# PX4FMUv2_4_3.net
KiCad netlist of a schematic drawn in EAGLE
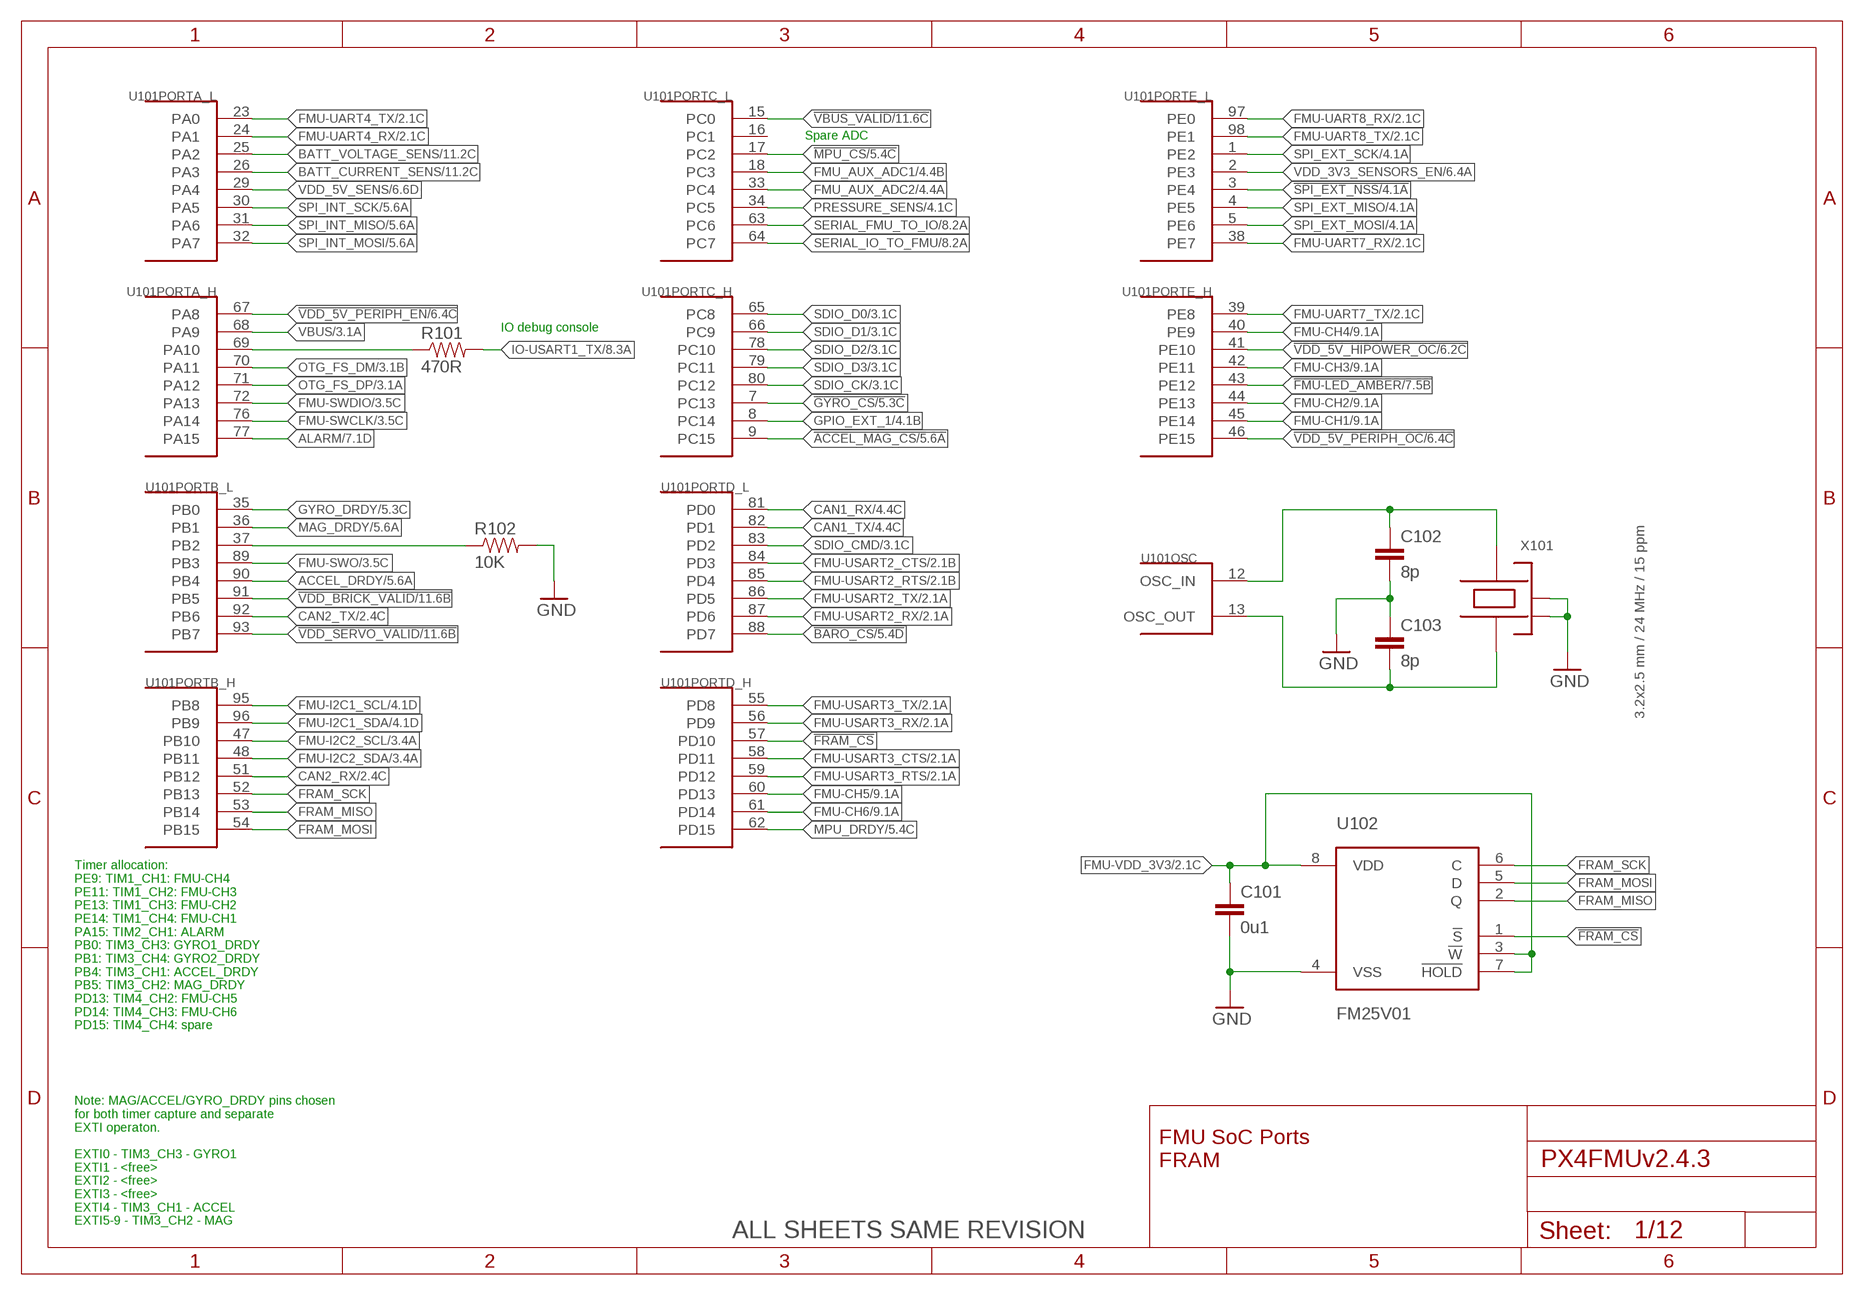
[diagram p0: schematic, sheet 1]
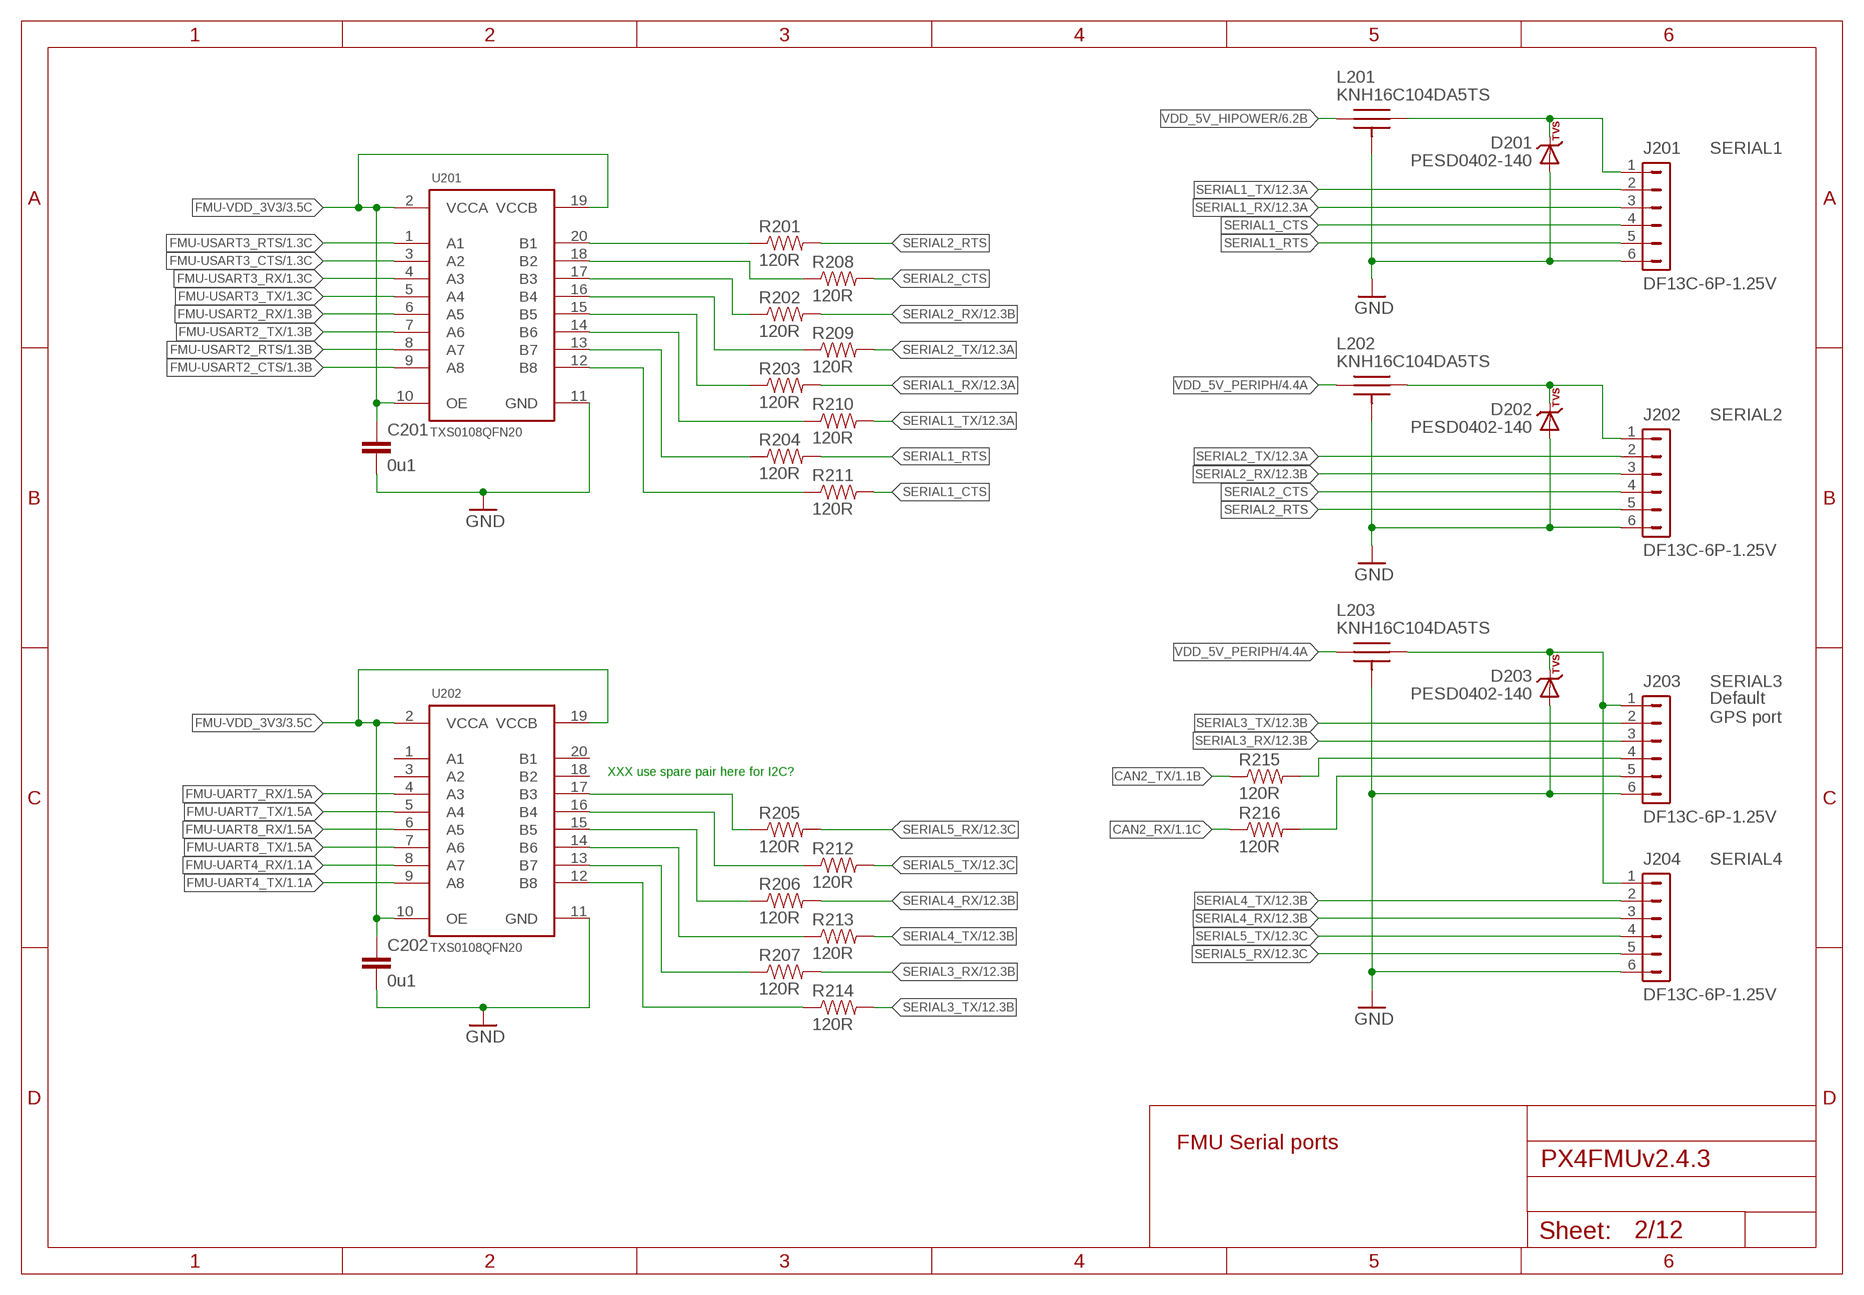
[diagram p1: schematic, sheet 2]
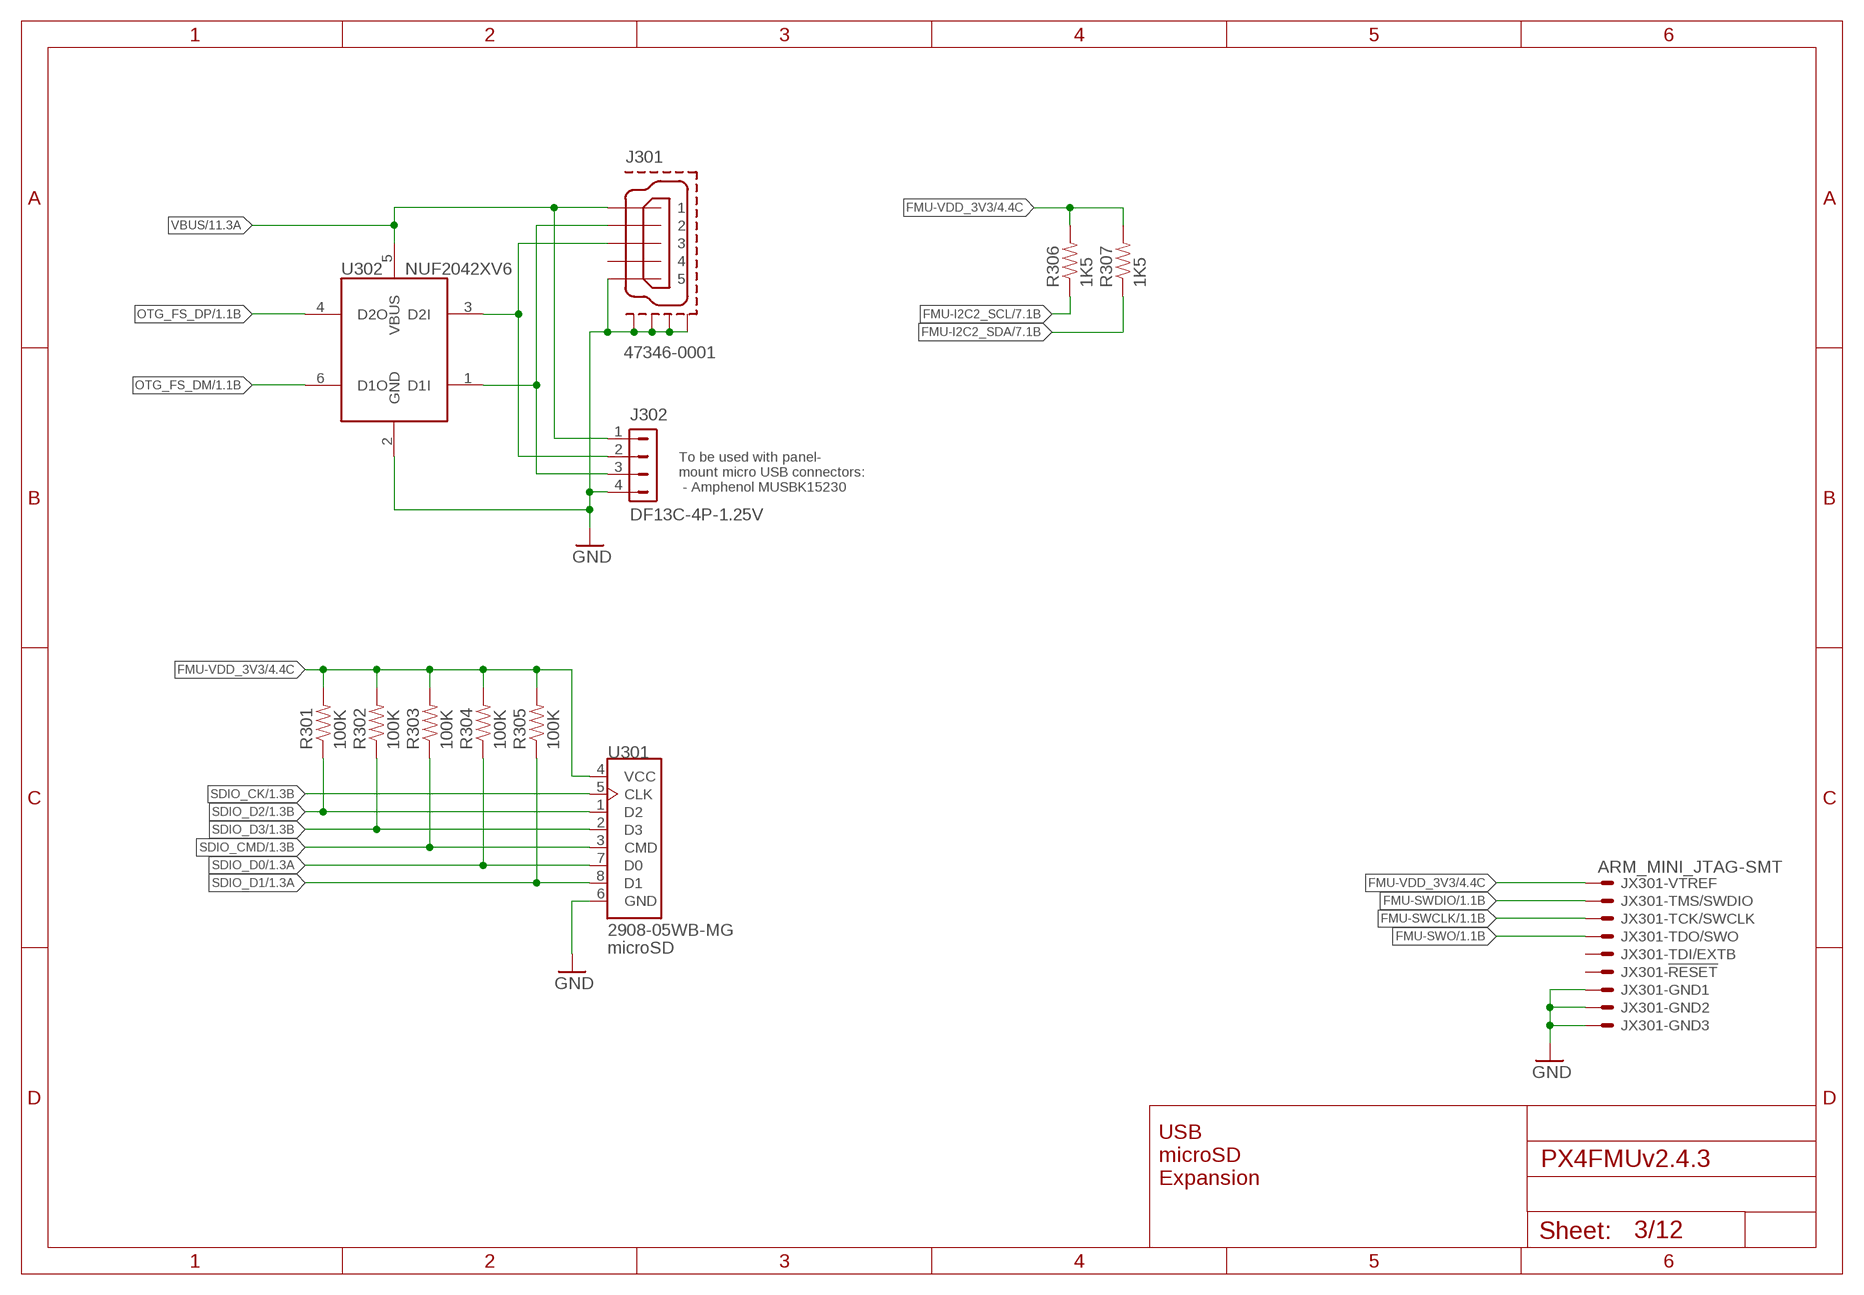
[diagram p2: schematic, sheet 3]
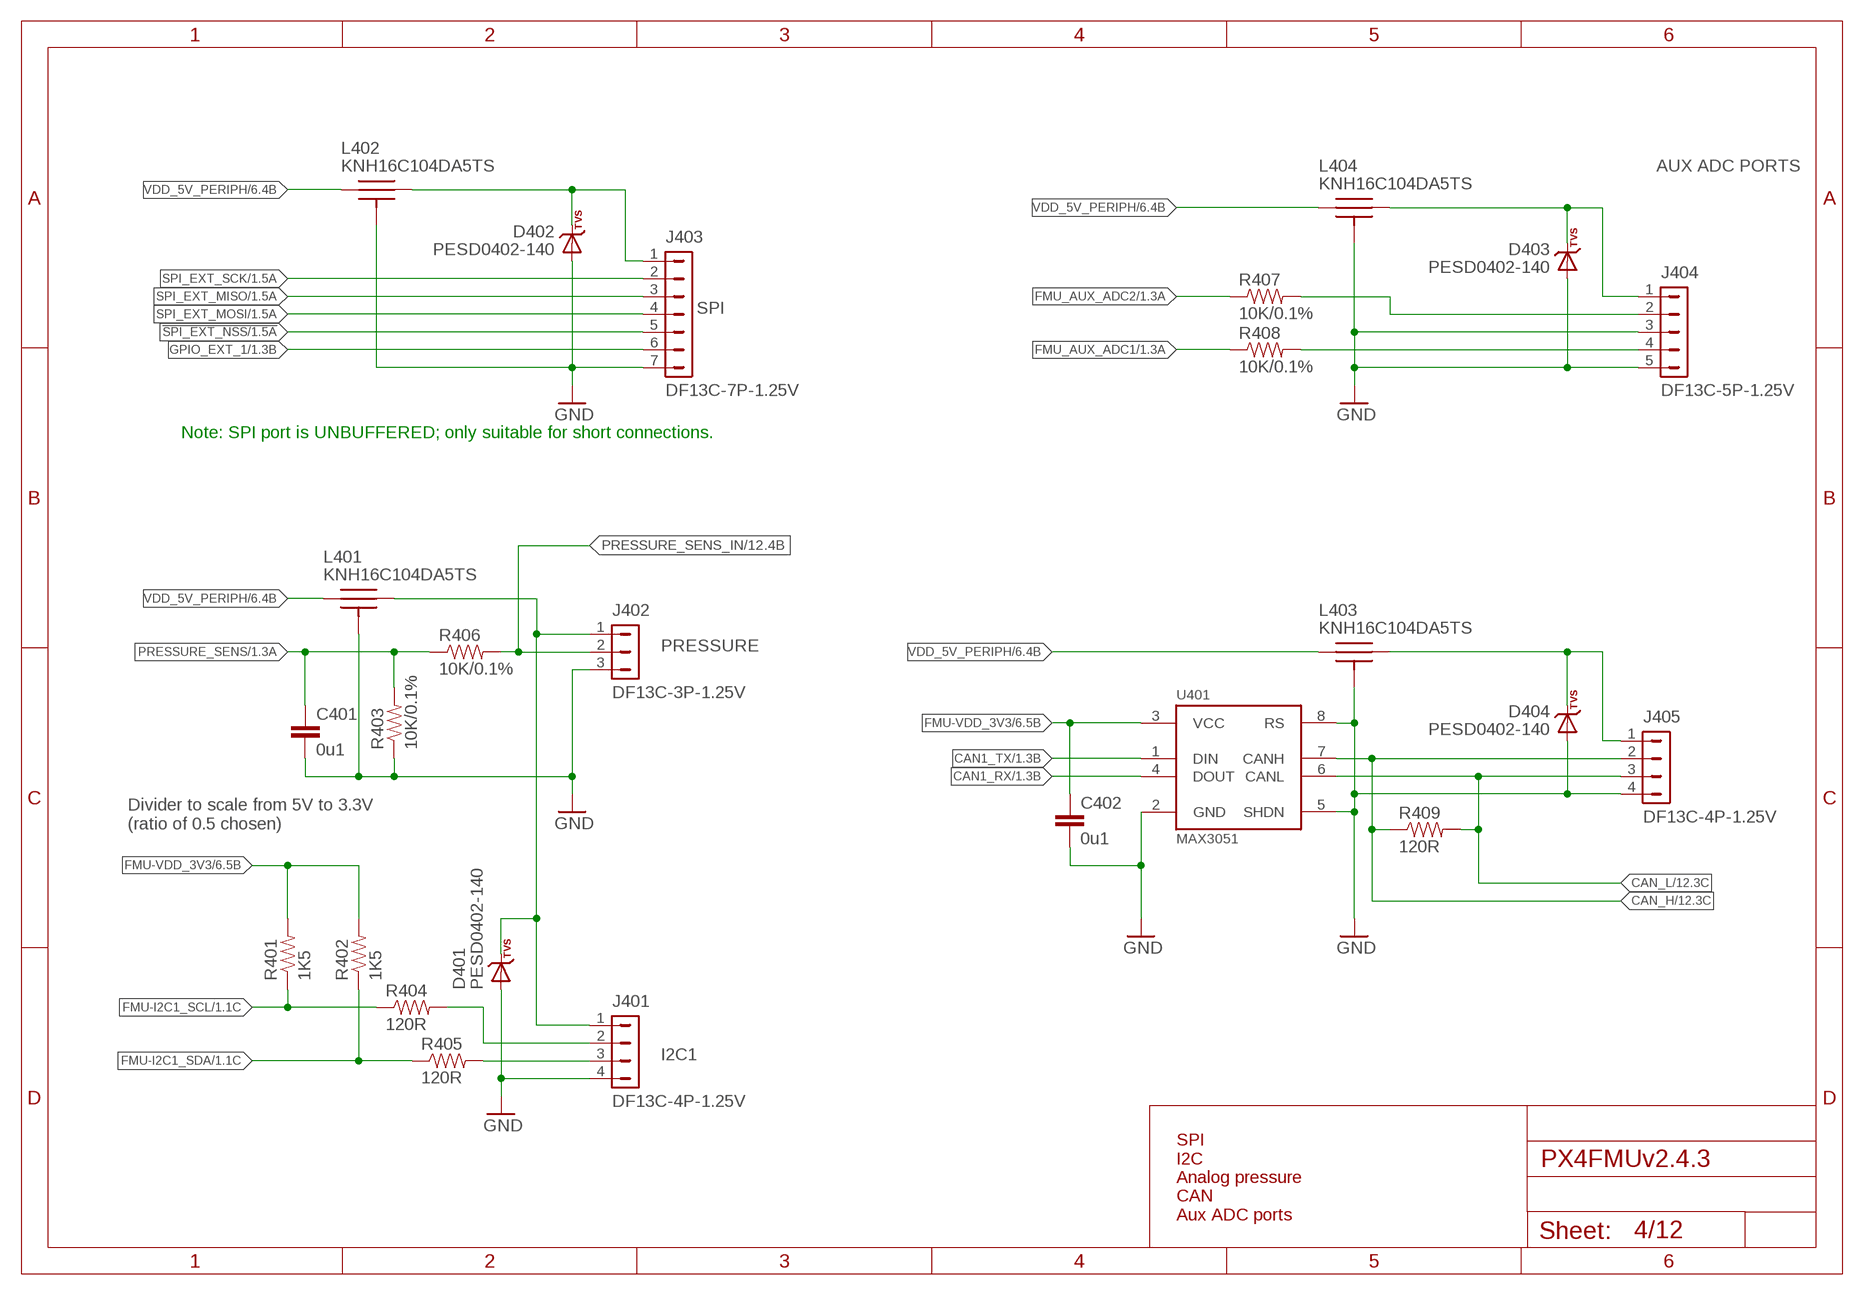
[diagram p3: schematic, sheet 4]
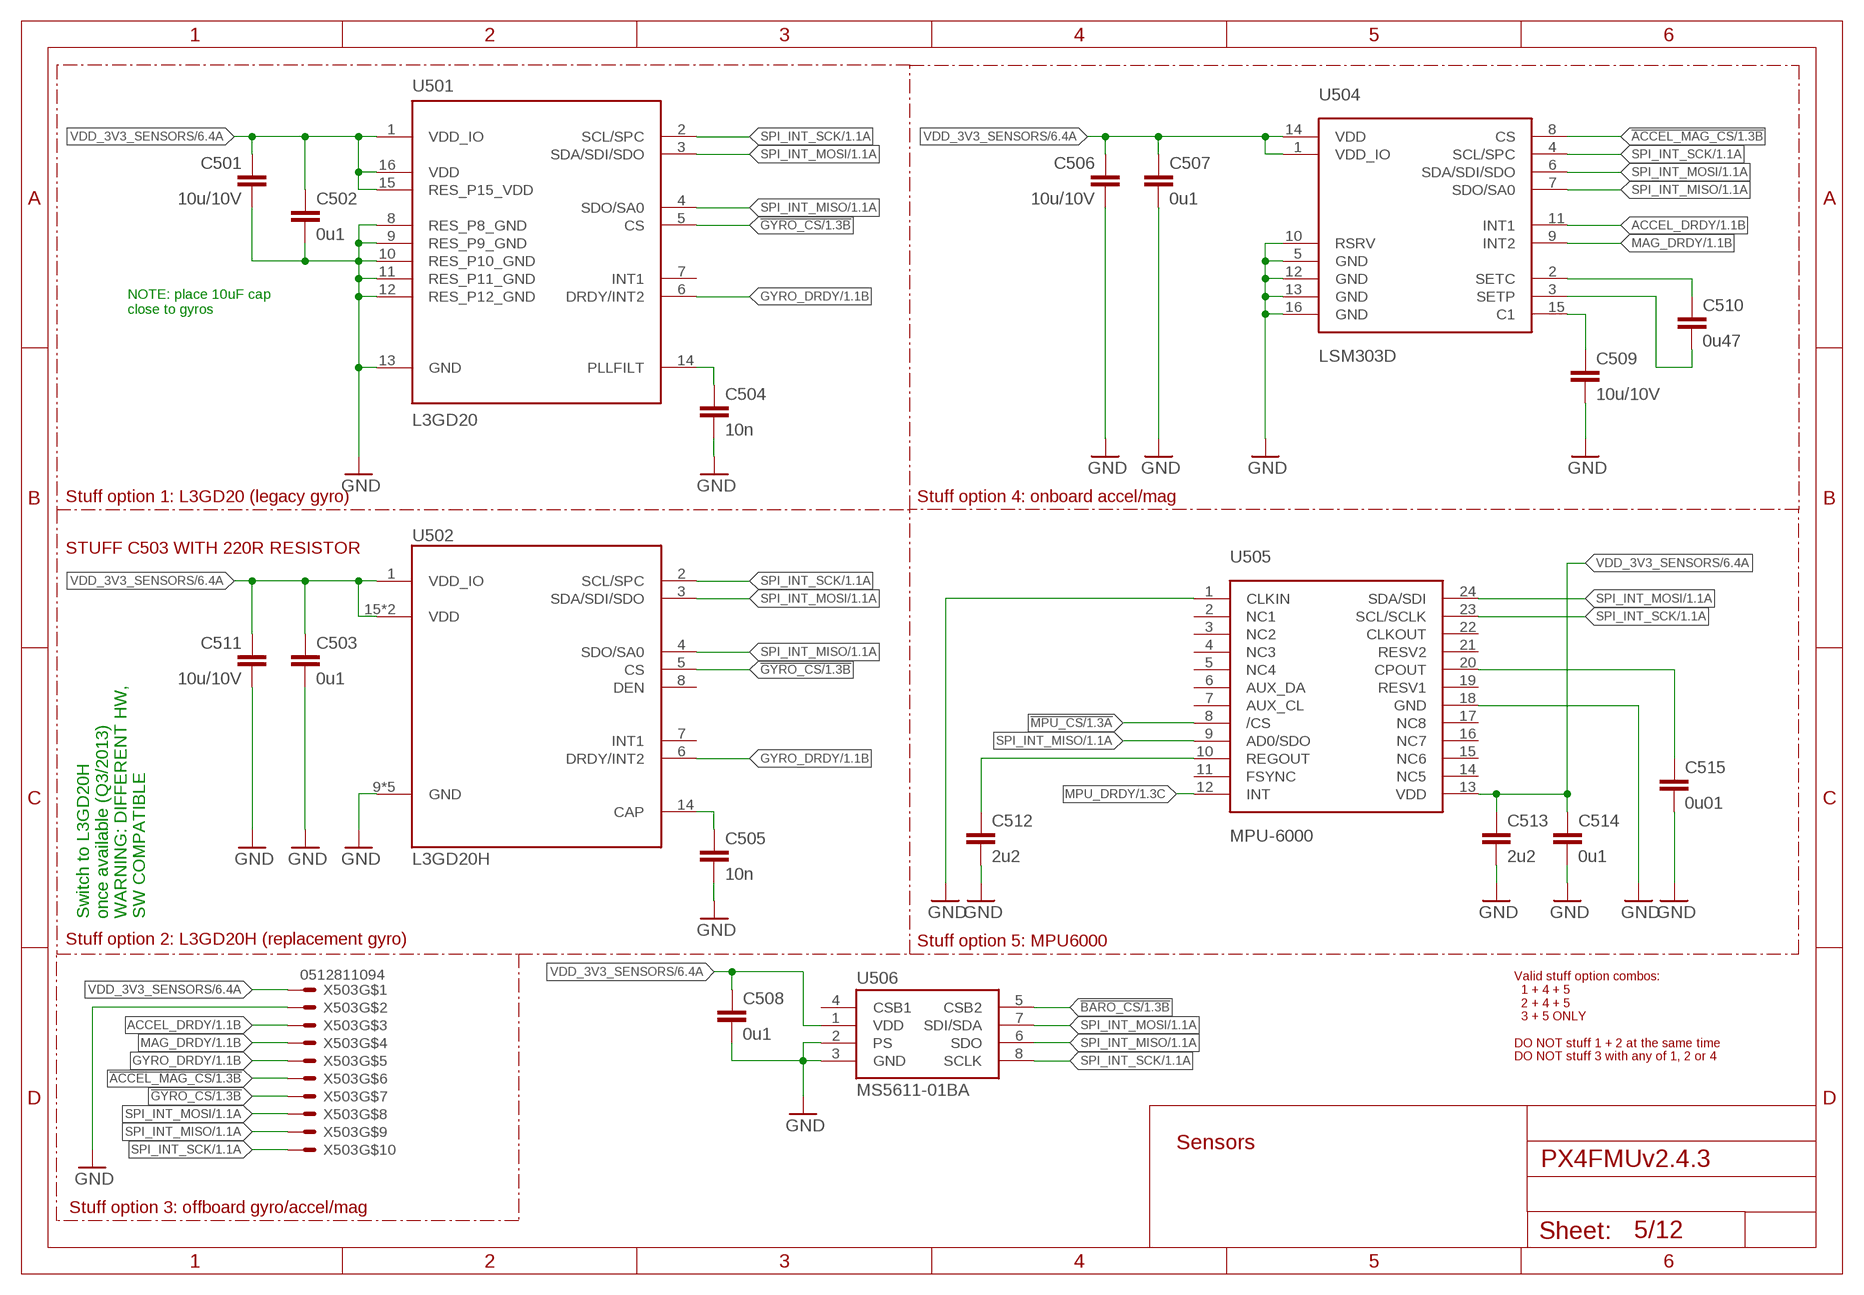
[diagram p4: schematic, sheet 5]
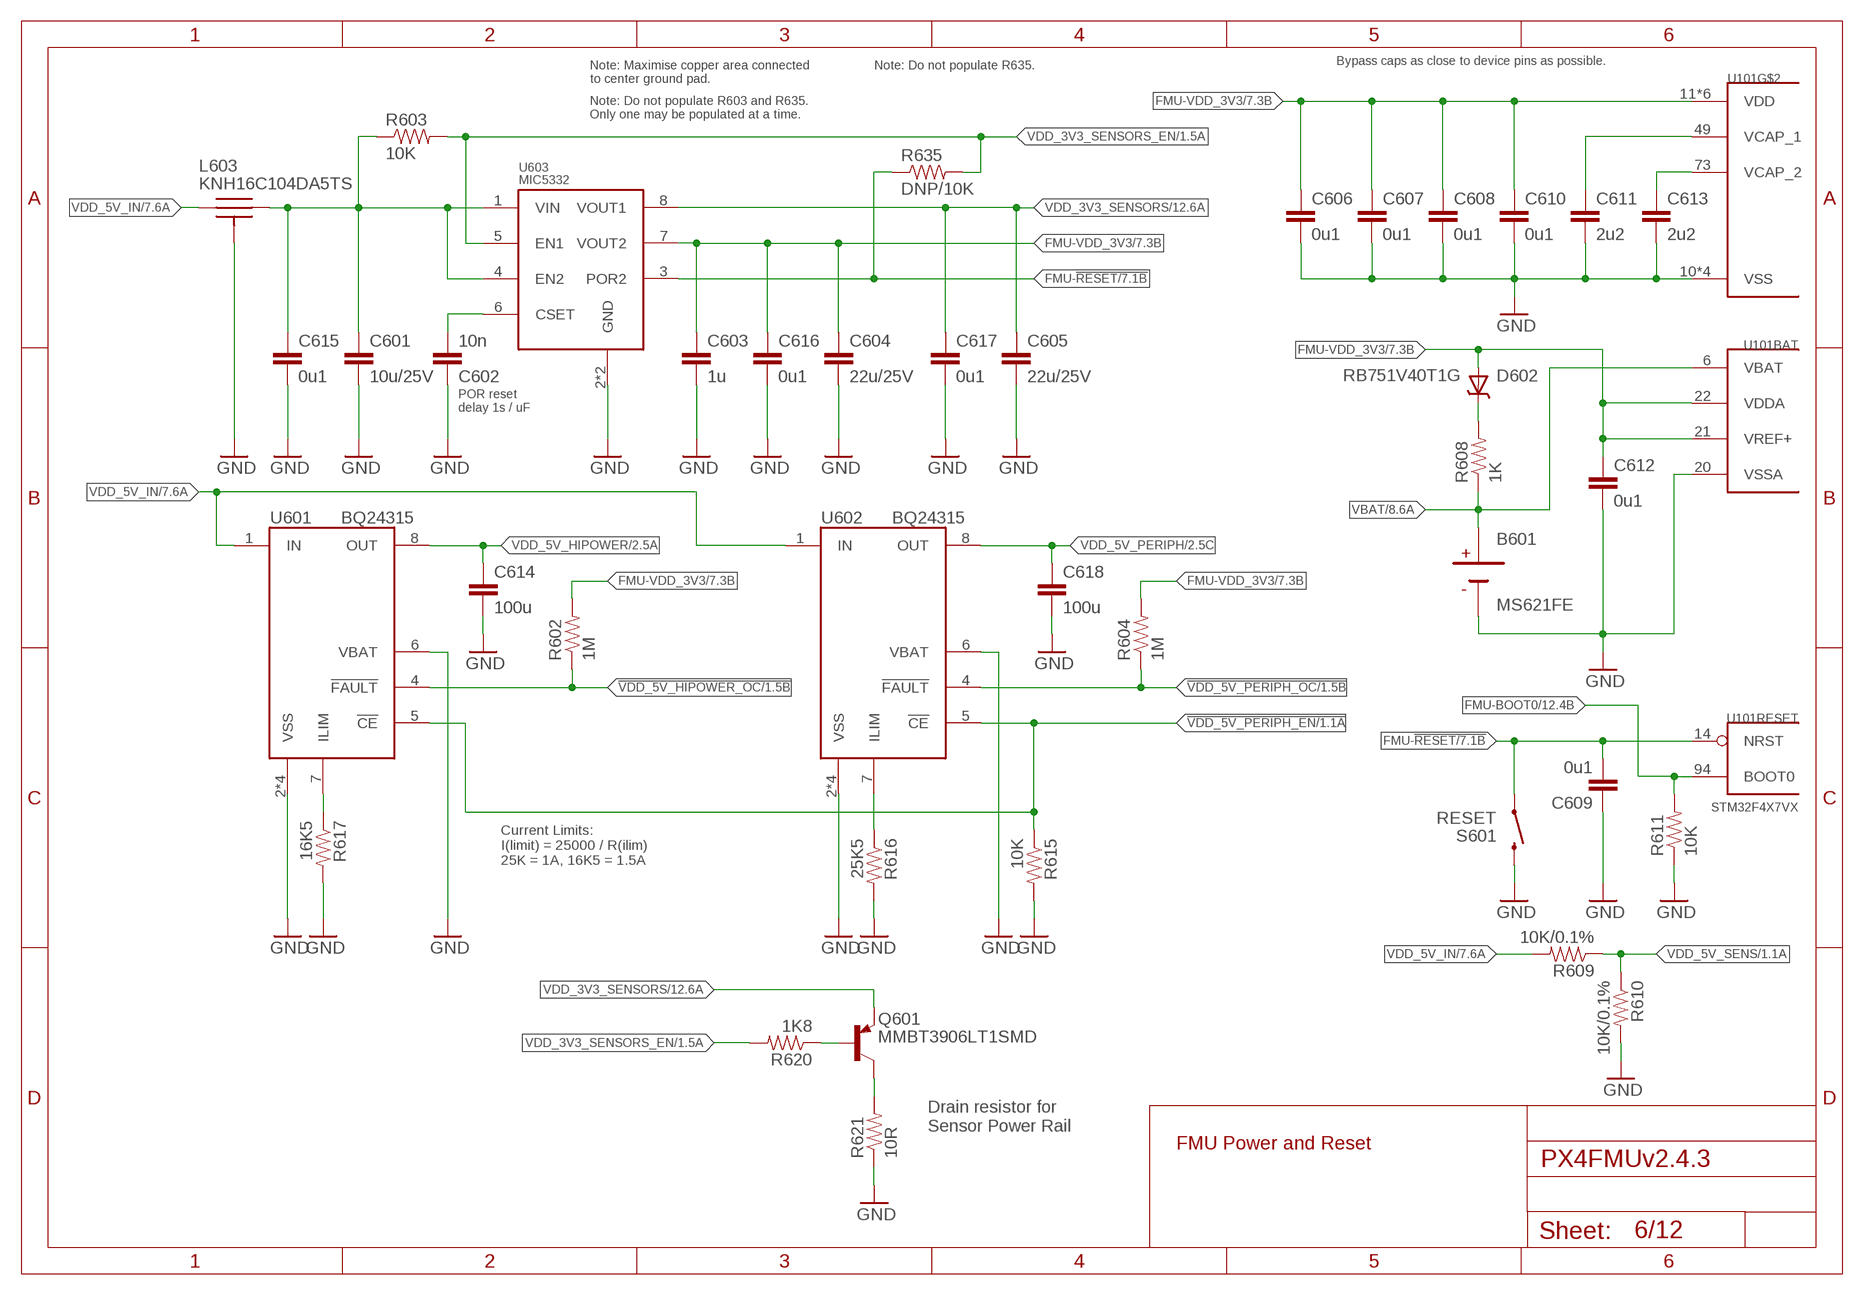
[diagram p5: schematic, sheet 6]
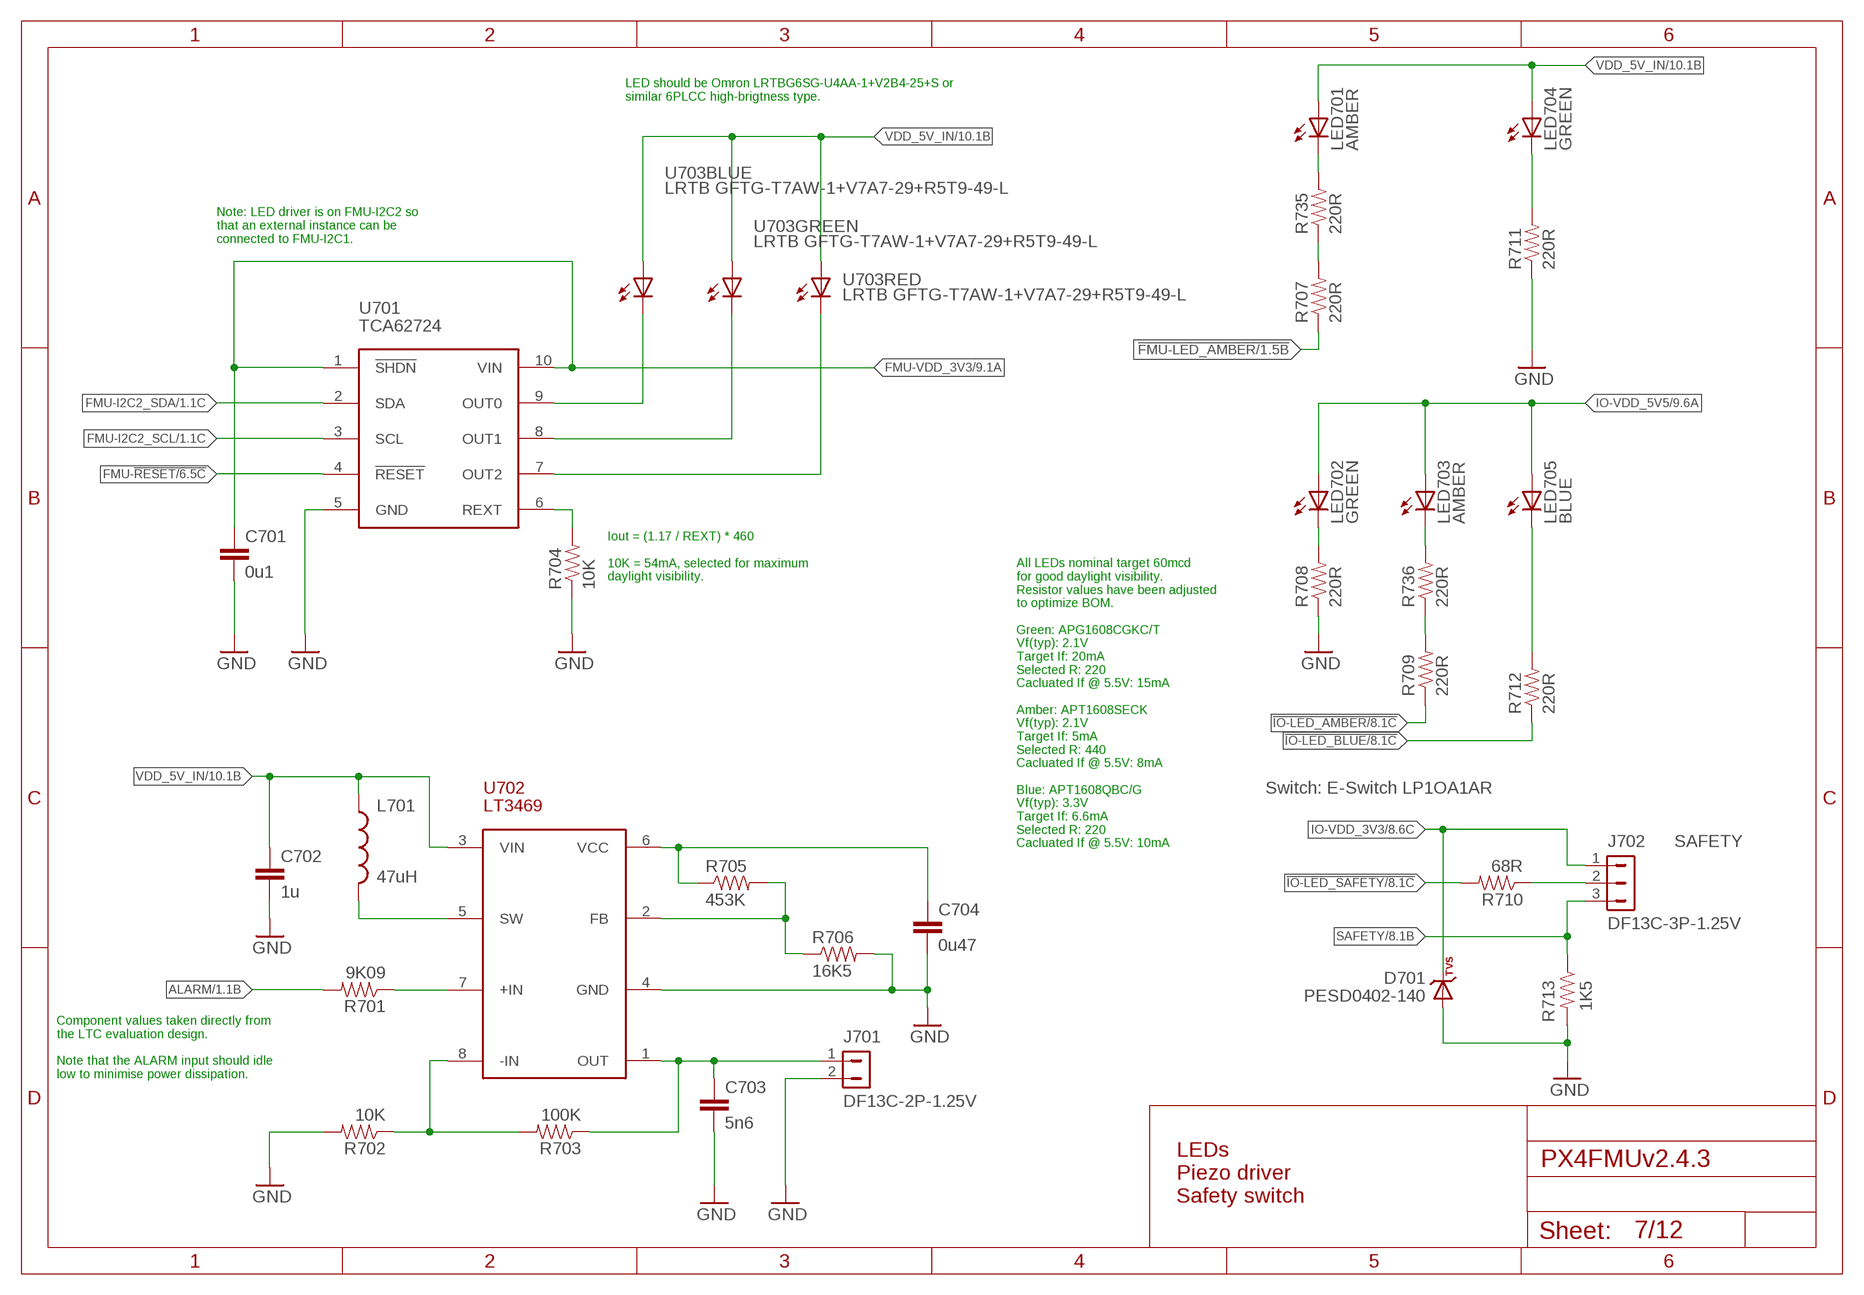
[diagram p6: schematic, sheet 7]
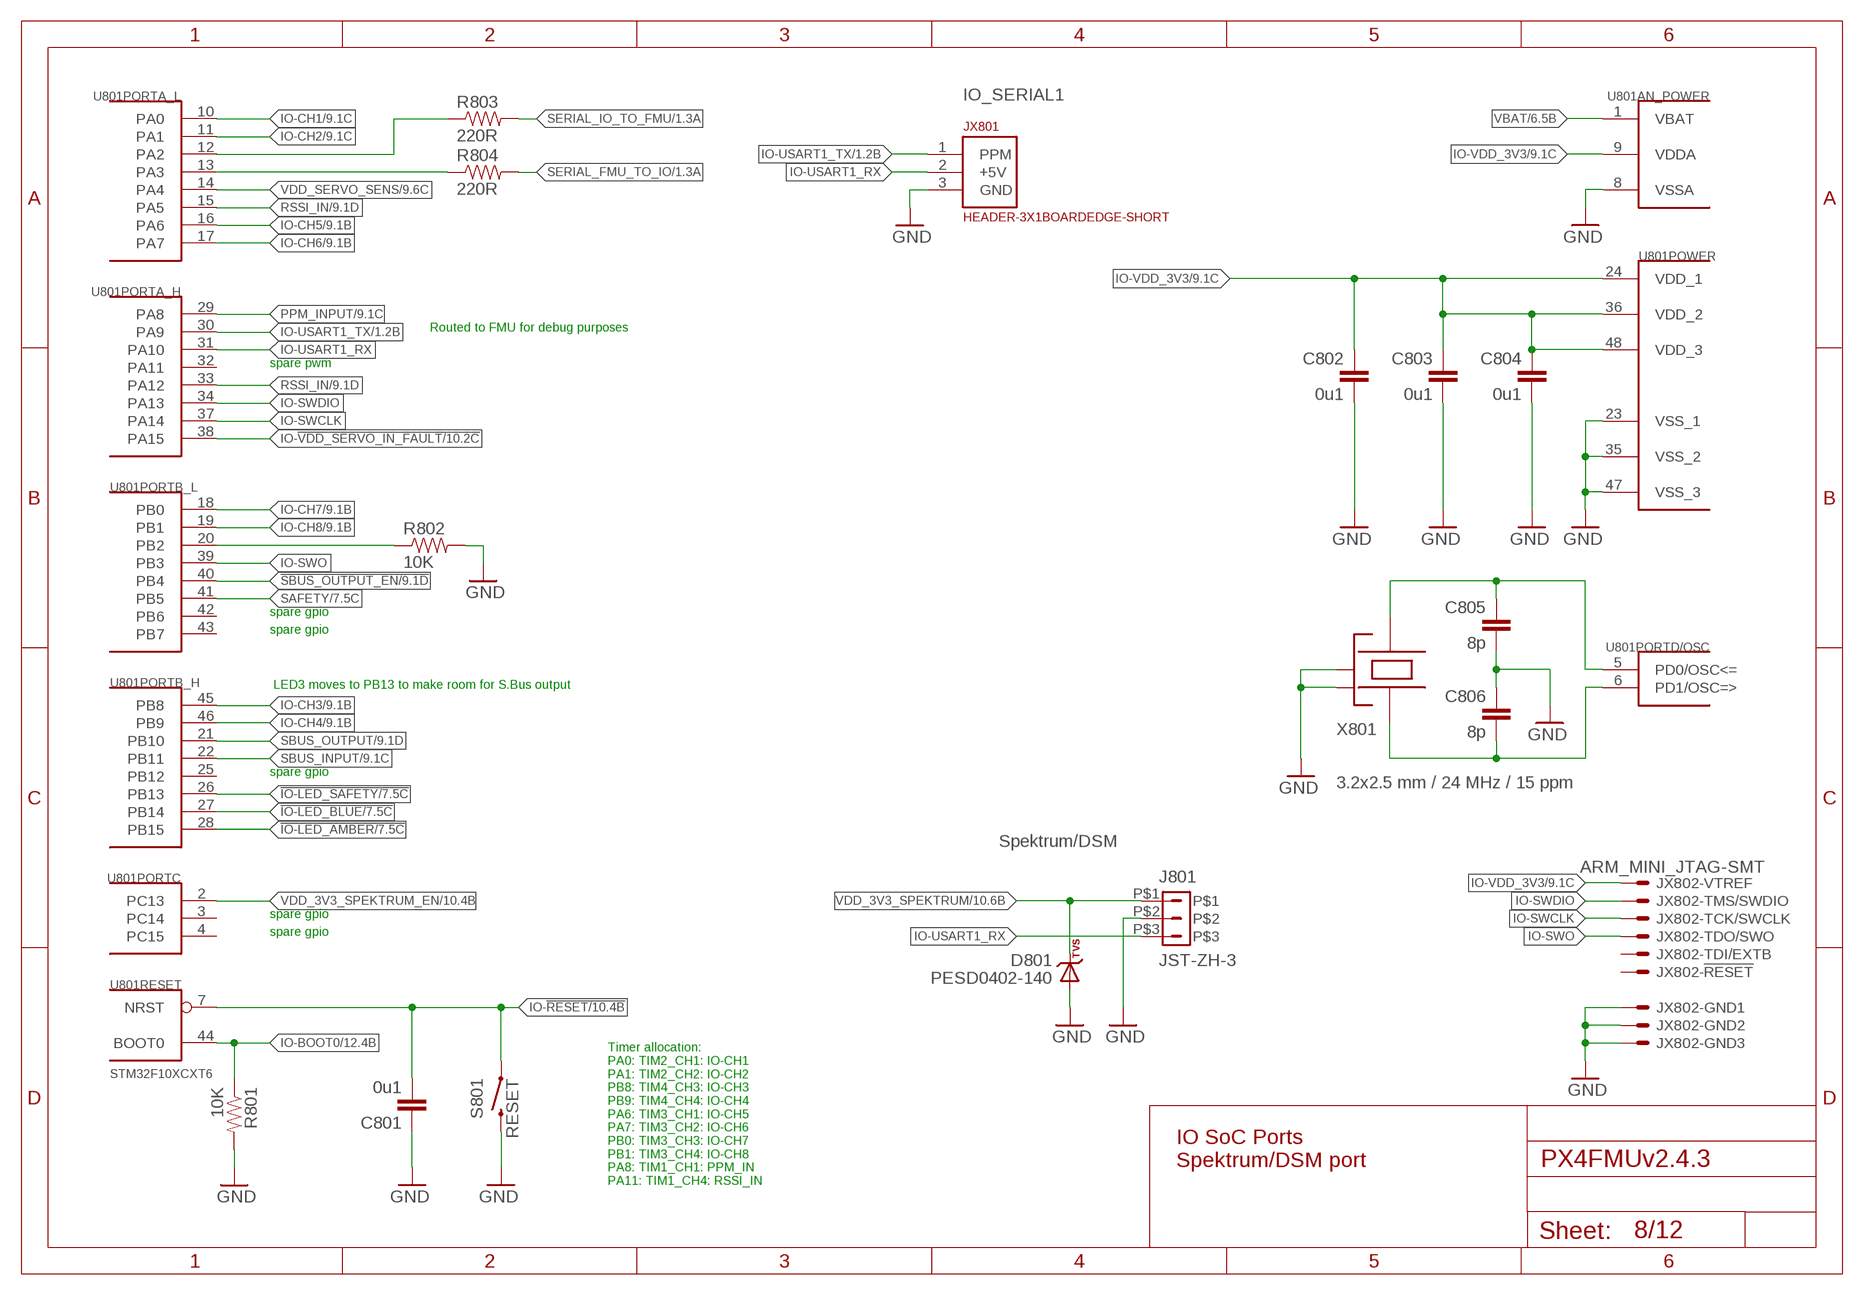
[diagram p7: schematic, sheet 8]
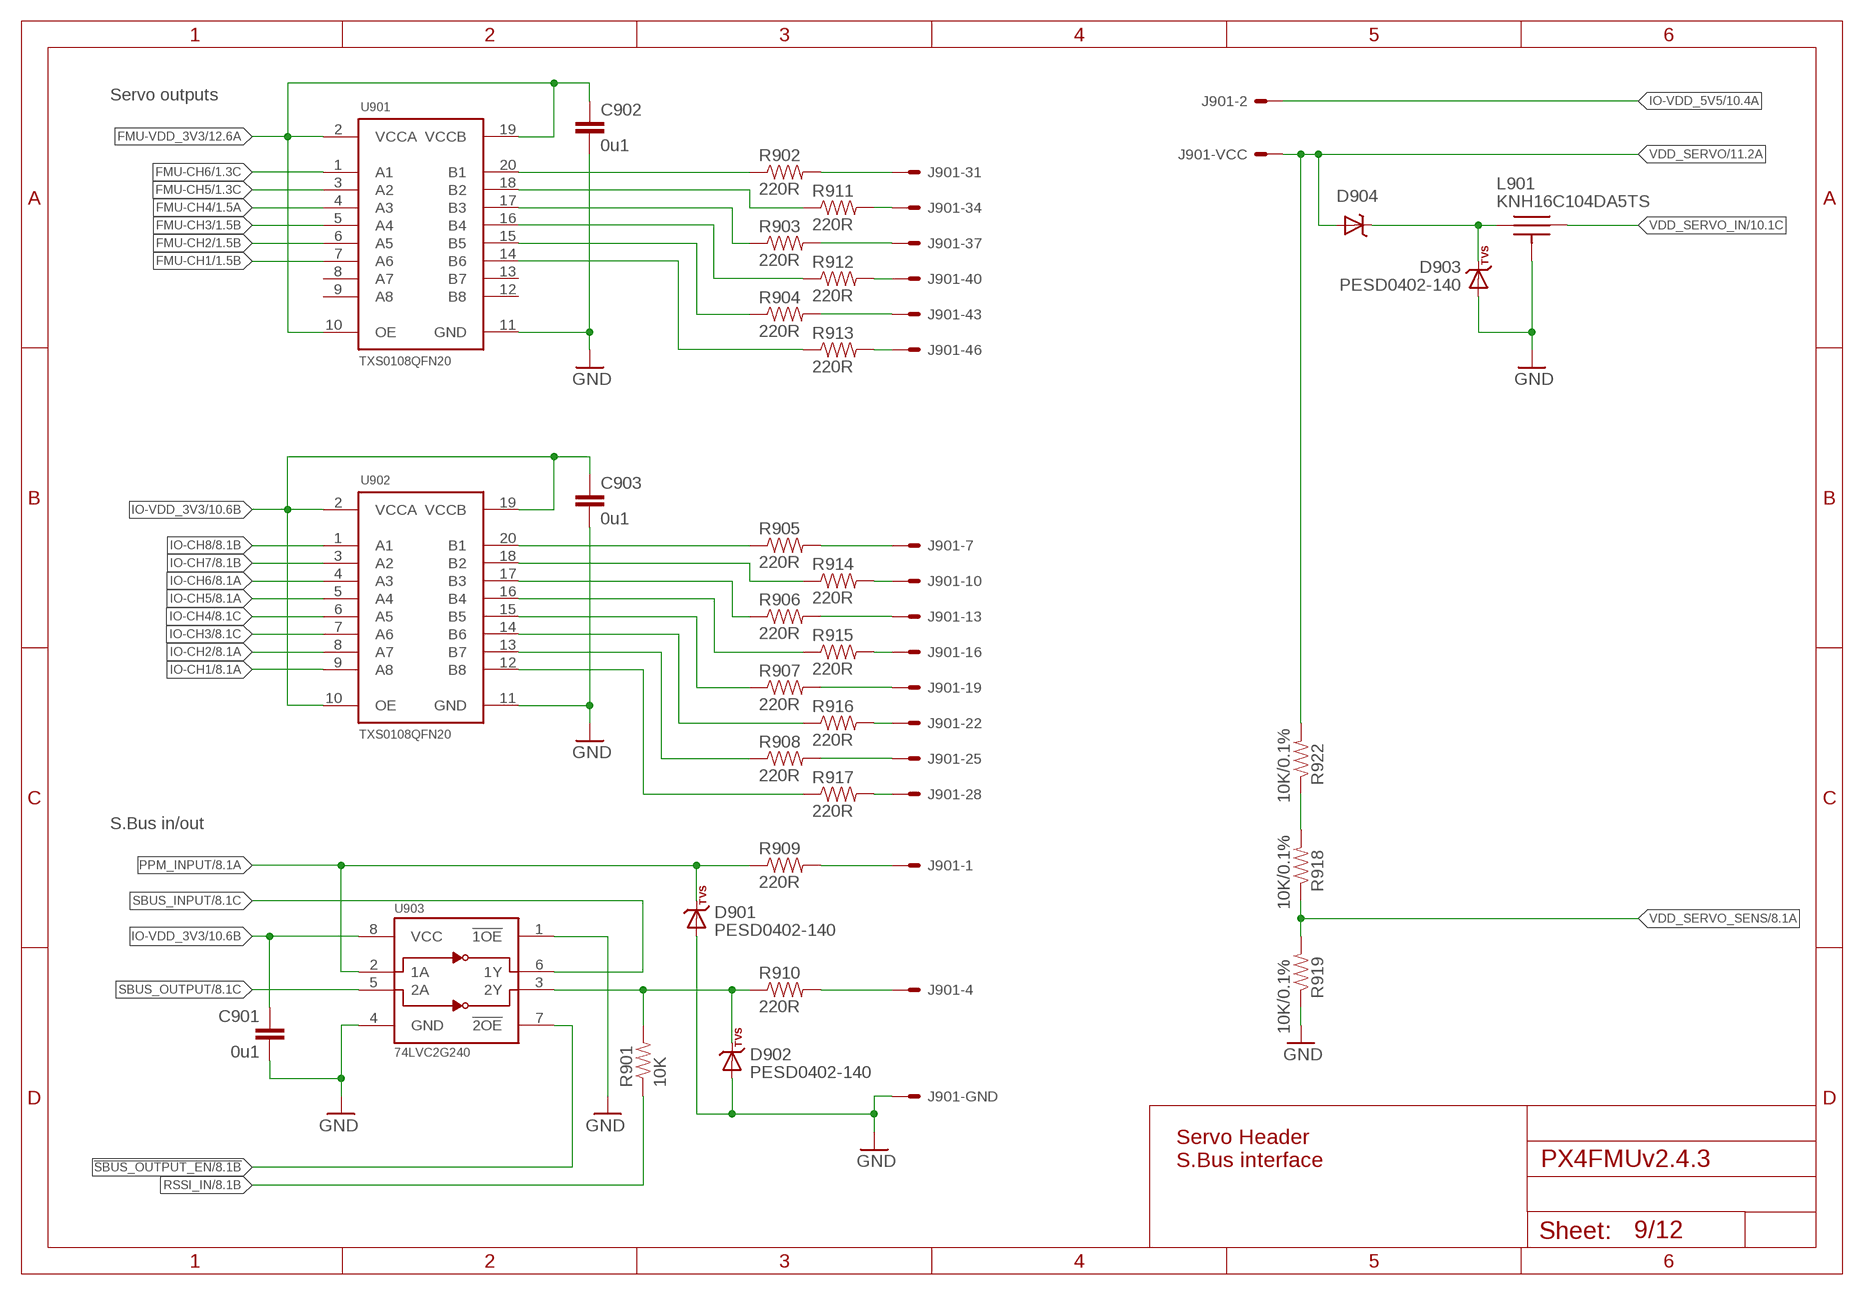
[diagram p8: schematic, sheet 9]
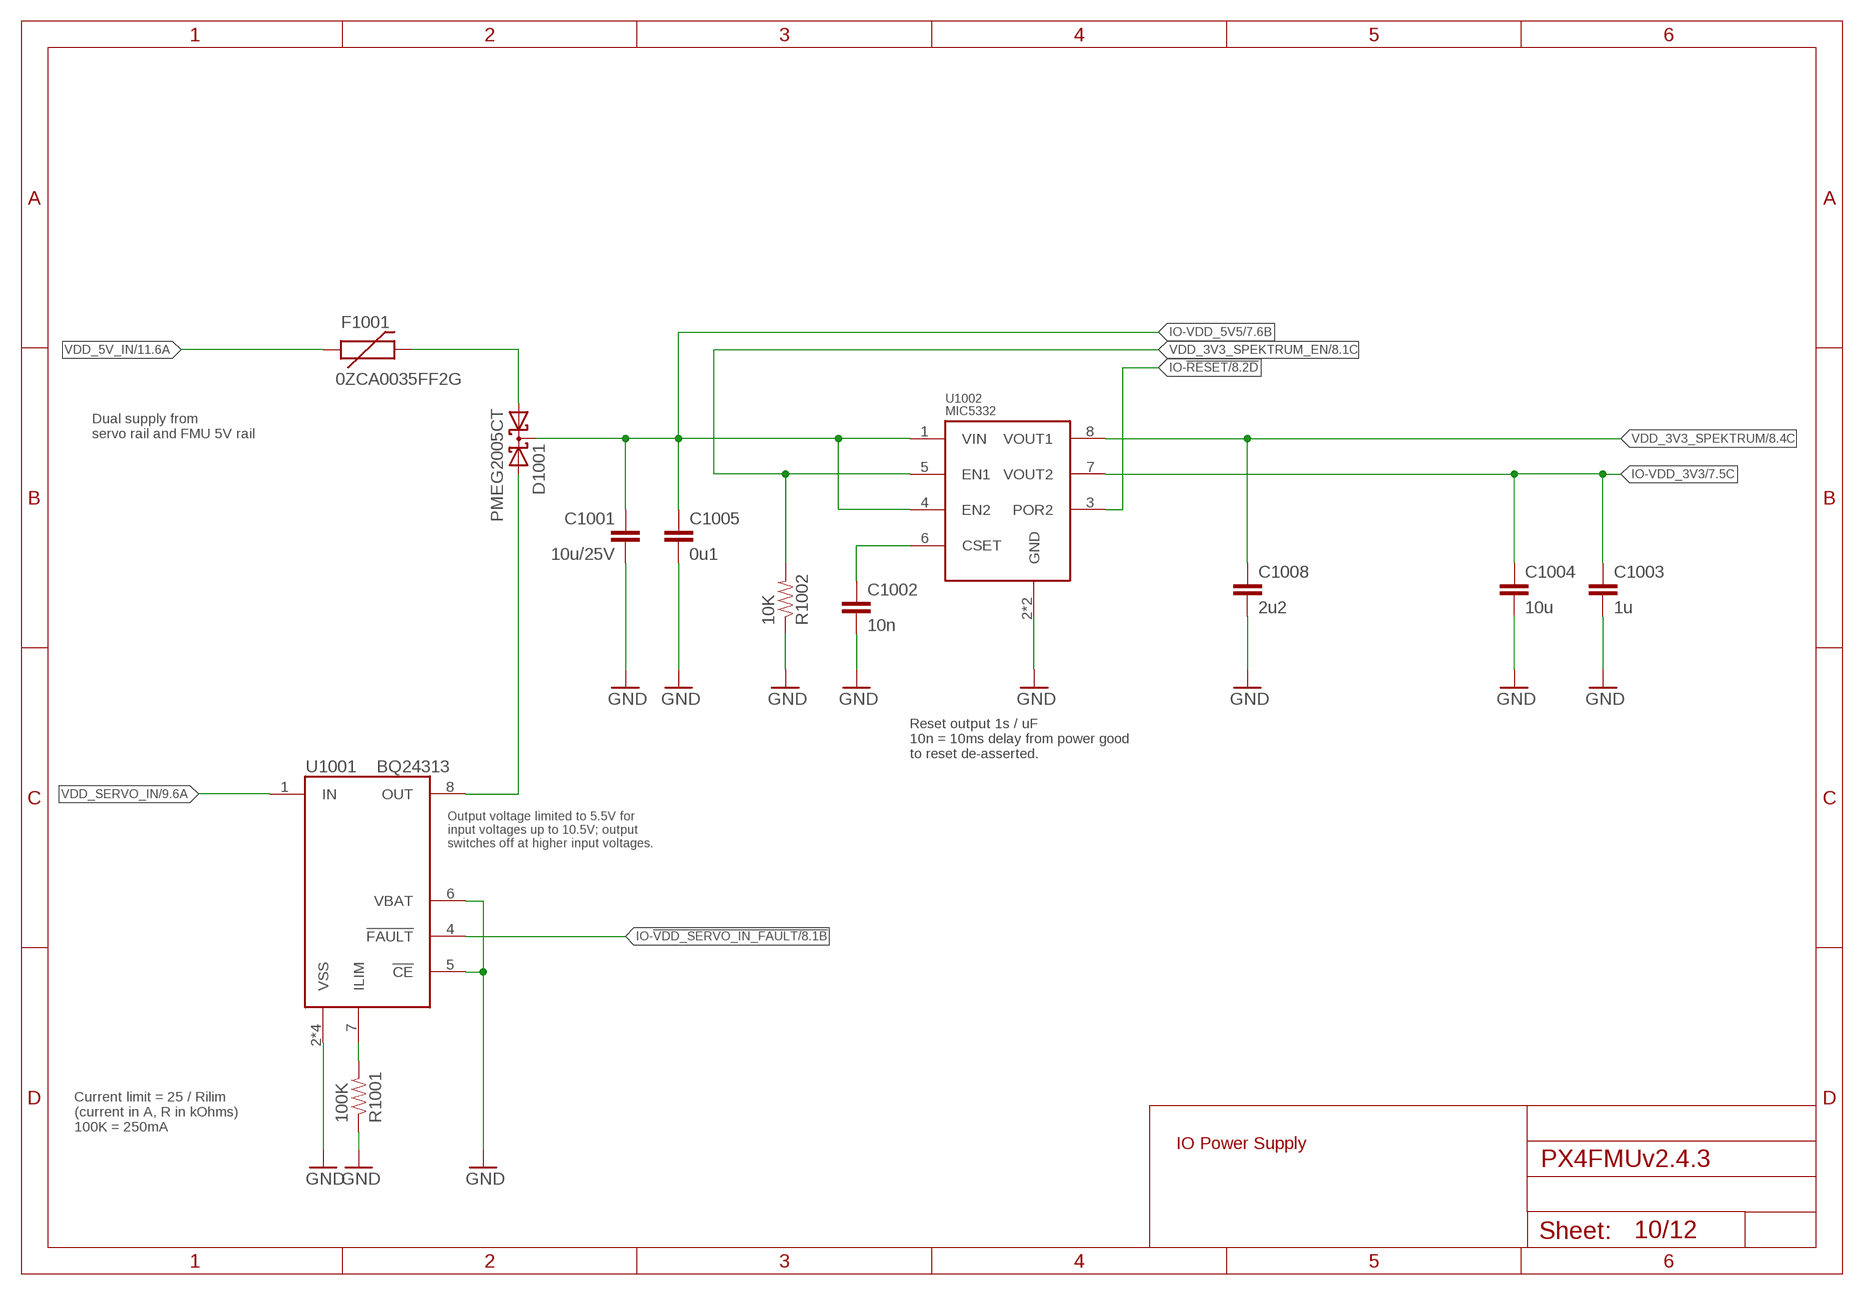
[diagram p9: schematic, sheet 10]
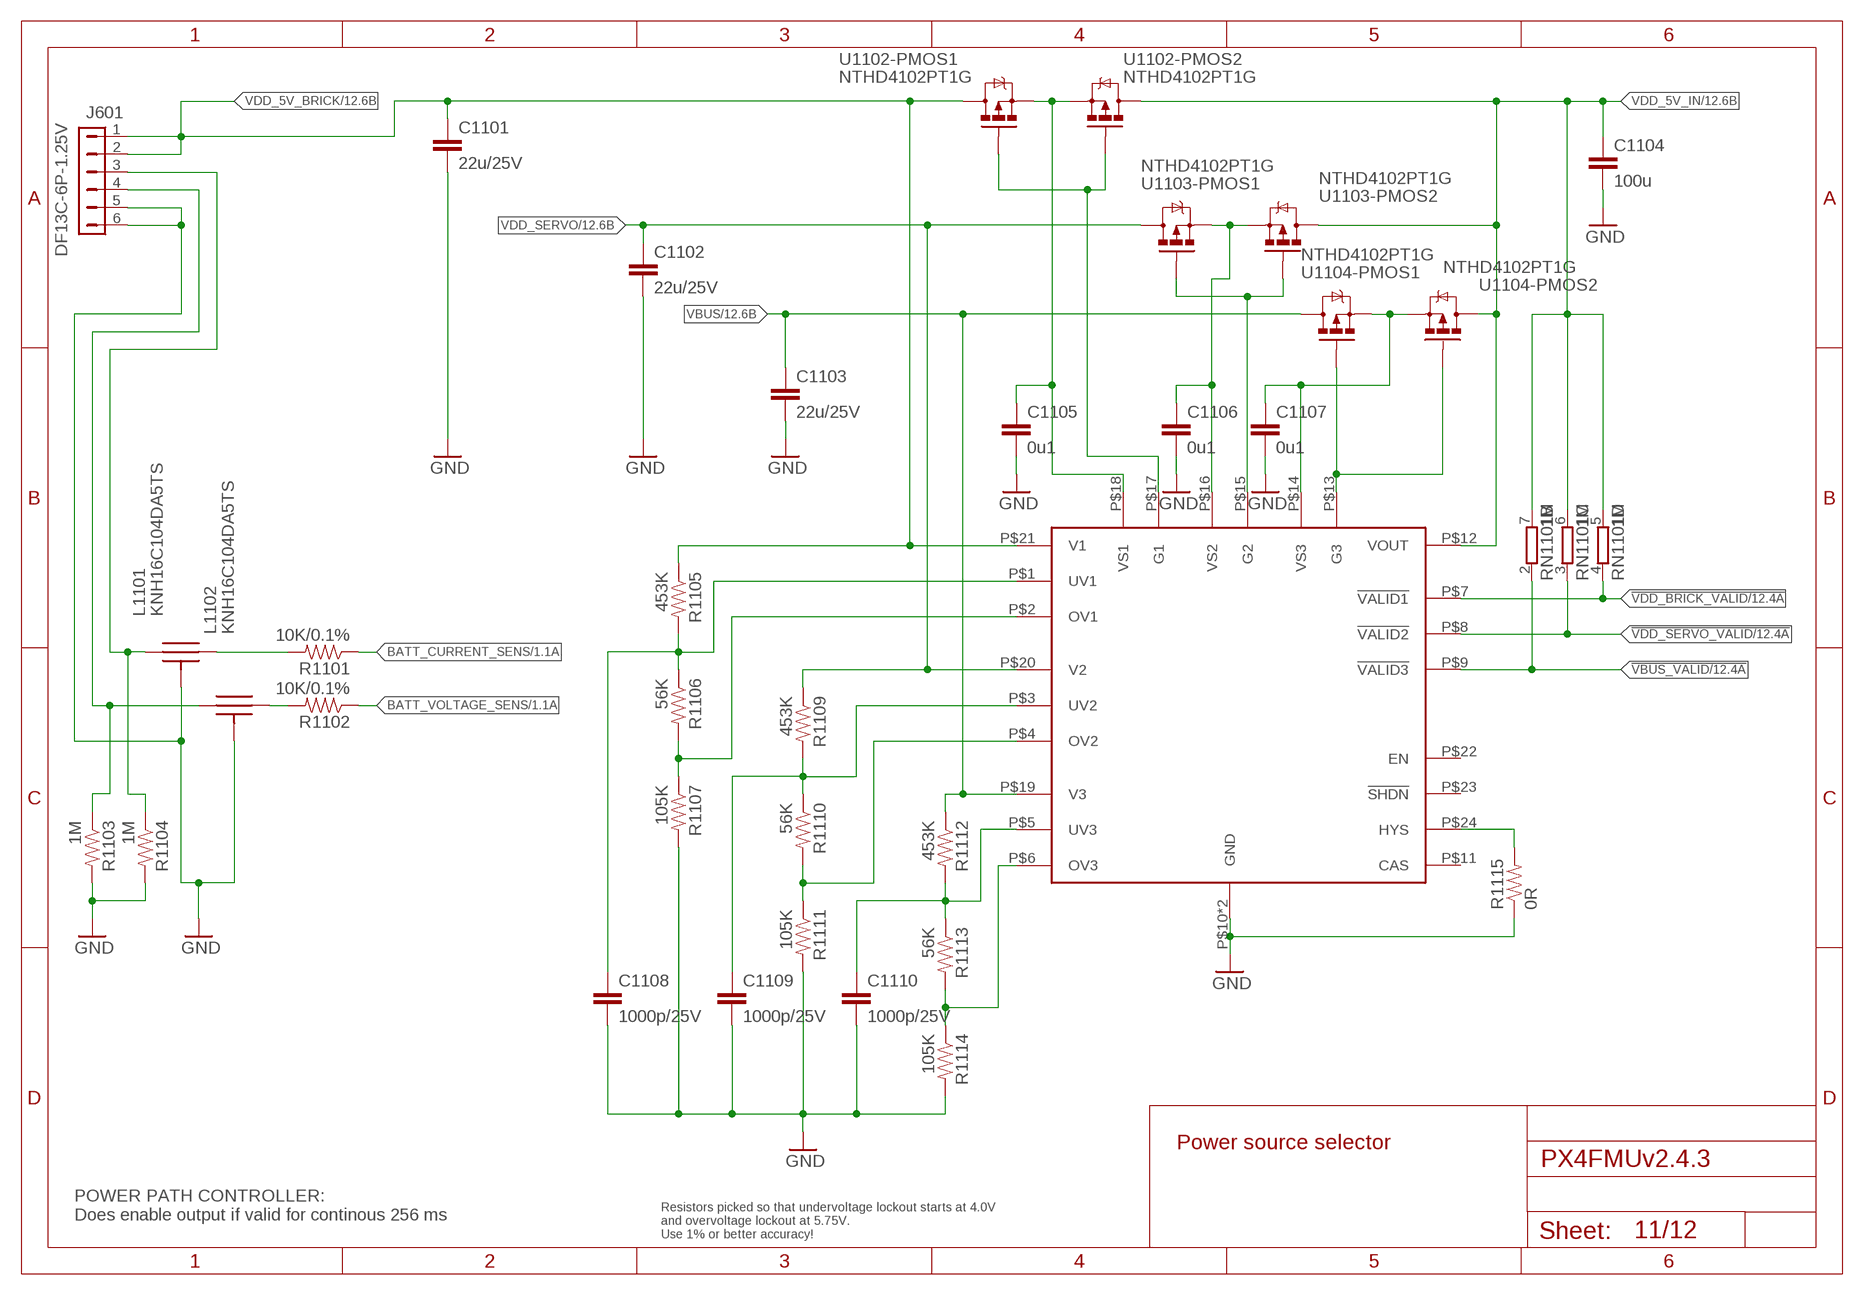
[diagram p10: schematic, sheet 11]
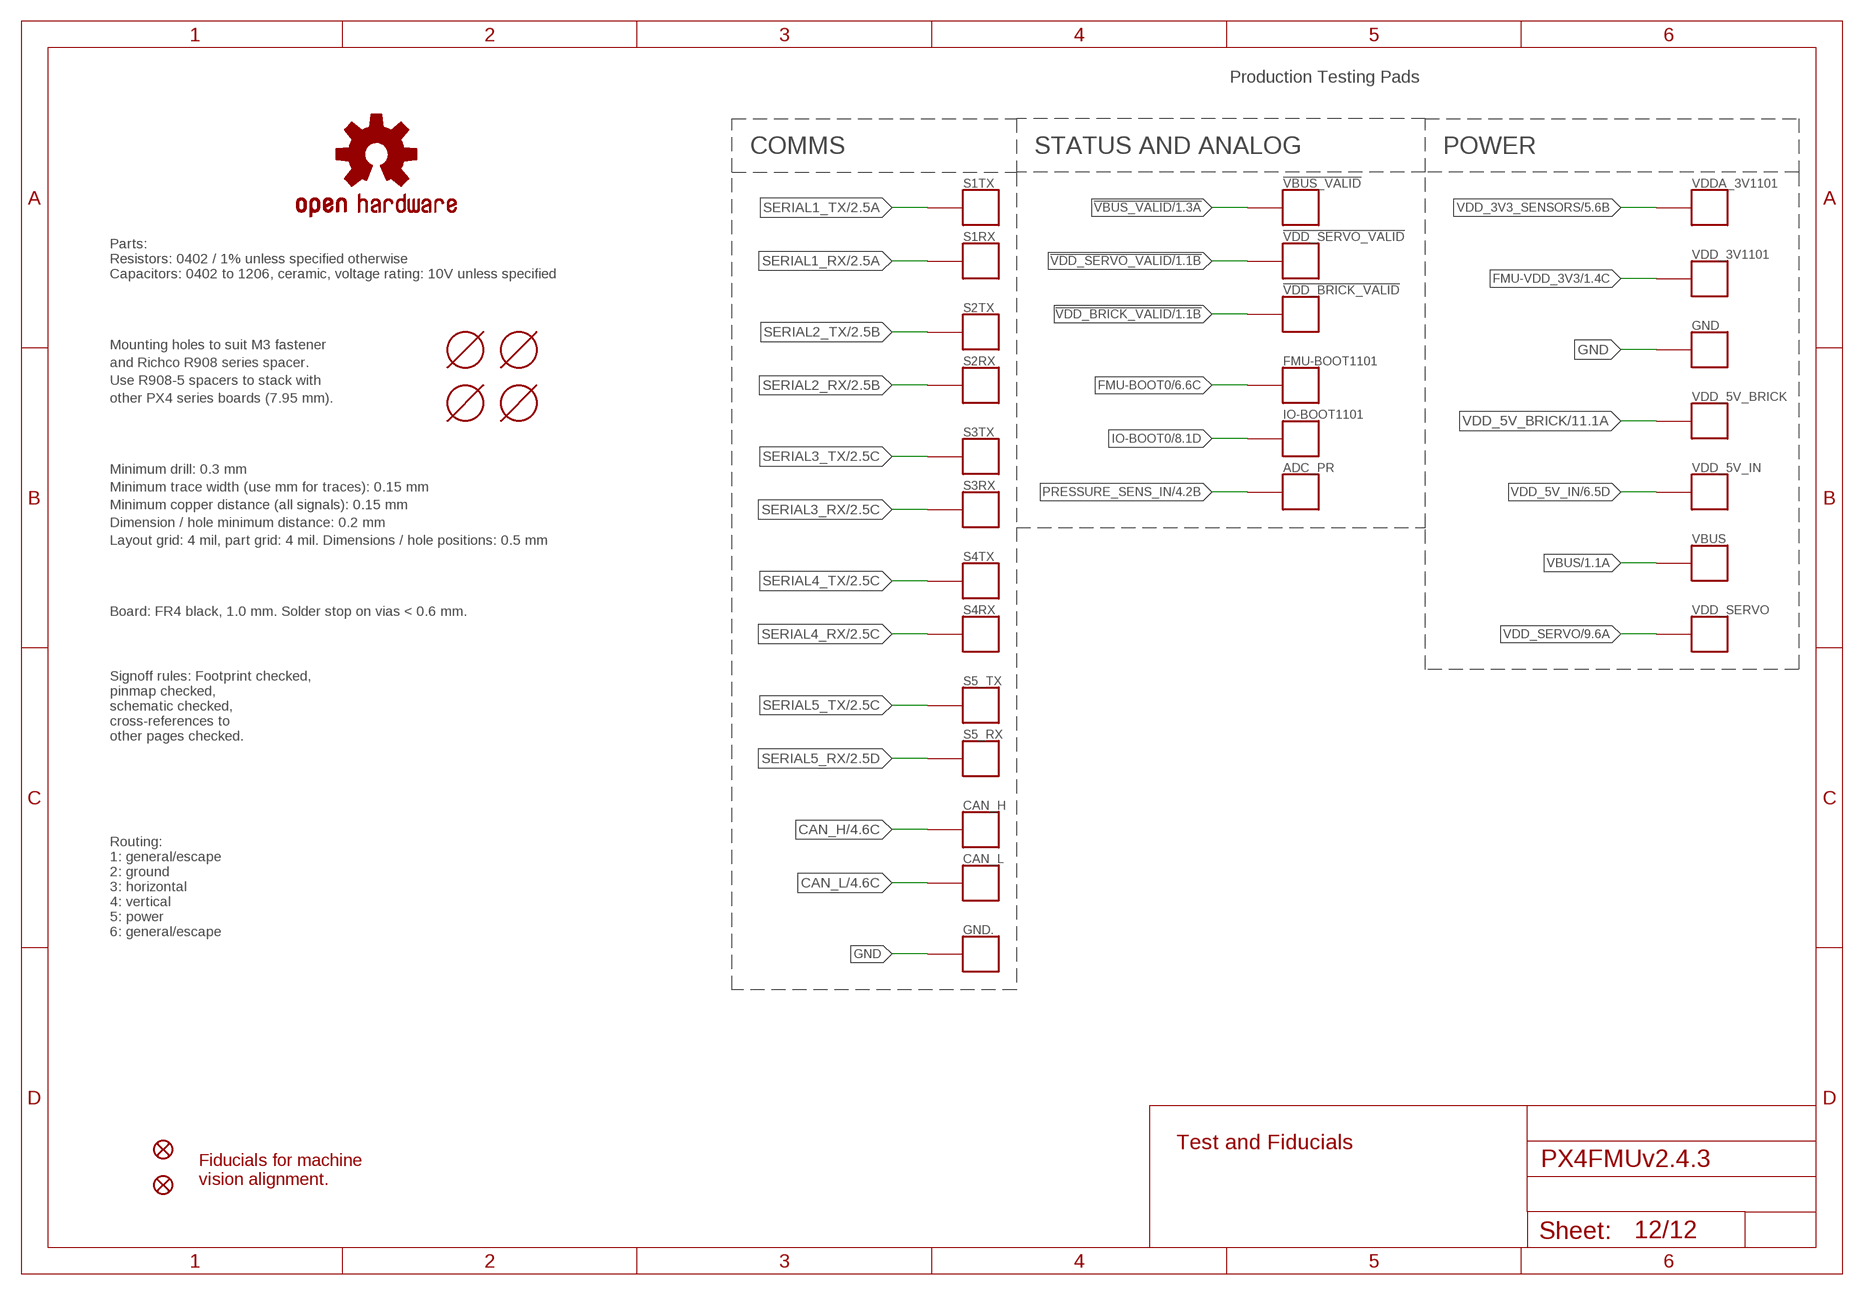
[diagram p11: schematic, sheet 12]

(export (version "E")
  (design (tool "Eeschema 10.0.6"))
  (components
    (comp (ref "C101")
      (value "0u1")
      (footprint "eagle-import:0402-CAP")
      (fields (field (name "PARTNO") "CC0402ZRY5V7BB104"))
      (libsource (lib "eagle-import") (part "CAP0402"))
    )
    (comp (ref "C102")
      (value "8p")
      (footprint "eagle-import:0402-CAP")
      (fields (field (name "PARTNO") "C1005C0G1H080C"))
      (libsource (lib "eagle-import") (part "CAP0402"))
    )
    (comp (ref "C103")
      (value "8p")
      (footprint "eagle-import:0402-CAP")
      (fields (field (name "PARTNO") "C1005C0G1H080C"))
      (libsource (lib "eagle-import") (part "CAP0402"))
    )
    (comp (ref "R101")
      (value "470R")
      (footprint "eagle-import:0402-RES")
      (fields (field (name "PARTNO") "RC0402FR-07470RL"))
      (libsource (lib "eagle-import") (part "RESISTOR0402-RES"))
    )
    (comp (ref "R102")
      (value "10K")
      (footprint "eagle-import:0402-RES")
      (fields (field (name "PARTNO") "RC0402FR-0710KL"))
      (libsource (lib "eagle-import") (part "RESISTOR0402-RES"))
    )
    (comp (ref "U101")
      (value "STM32F4X7VX")
      (footprint "eagle-import:TQFP100")
      (fields (field (name "PARTNO") "STM32F427VI"))
      (libsource (lib "eagle-import") (part "STM32F4X7VX"))
    )
    (comp (ref "U102")
      (value "FM25V01")
      (footprint "eagle-import:SO08")
      (fields (field (name "PARTNO") "FM25V01-G"))
      (libsource (lib "eagle-import") (part "FM25V01"))
    )
    (comp (ref "X101")
      (value "3.2x2.5 mm / 24 MHz / 15 ppm")
      (footprint "eagle-import:OSCILLATOR-3.2X2.5")
      (fields (field (name "PARTNO") "NX3225SA-24.000000MHZ"))
      (libsource (lib "eagle-import") (part "OSCILLATOR-3.2X2.5"))
    )
    (comp (ref "C1001")
      (value "10u/25V")
      (footprint "eagle-import:0805-CAP")
      (fields (field (name "PARTNO") "CL21A106KAYNNNE"))
      (libsource (lib "eagle-import") (part "CAP0805"))
    )
    (comp (ref "C1002")
      (value "10n")
      (footprint "eagle-import:0402-CAP")
      (fields (field (name "PARTNO") "CC0402KRX7R7BB103"))
      (libsource (lib "eagle-import") (part "CAP0402"))
    )
    (comp (ref "C1003")
      (value "1u")
      (footprint "eagle-import:0603-CAP")
      (fields (field (name "PARTNO") "CC0603ZRY5V7BB105"))
      (libsource (lib "eagle-import") (part "CAP0603"))
    )
    (comp (ref "C1004")
      (value "10u")
      (footprint "eagle-import:0603-CAP")
      (fields (field (name "PARTNO") "C1608X5R1A106K080AC"))
      (libsource (lib "eagle-import") (part "CAP0603"))
    )
    (comp (ref "C1005")
      (value "0u1")
      (footprint "eagle-import:0402-CAP")
      (fields (field (name "PARTNO") "CC0402ZRY5V7BB104"))
      (libsource (lib "eagle-import") (part "CAP0402"))
    )
    (comp (ref "C1008")
      (value "2u2")
      (footprint "eagle-import:0402-CAP")
      (fields (field (name "PARTNO") "C1005X6S1C225K050BC"))
      (libsource (lib "eagle-import") (part "CAP0402"))
    )
    (comp (ref "D1001")
      (value "PMEG2005CT")
      (footprint "eagle-import:SOT23-3")
      (libsource (lib "eagle-import") (part "PMEG2005CT"))
    )
    (comp (ref "F1001")
      (value "0ZCA0035FF2G")
      (footprint "eagle-import:PTC-1206")
      (libsource (lib "eagle-import") (part "PTCSMD"))
    )
    (comp (ref "R1001")
      (value "100K")
      (footprint "eagle-import:0402-RES")
      (fields (field (name "PARTNO") "RC0402FR-07100KL"))
      (libsource (lib "eagle-import") (part "RESISTOR0402-RES"))
    )
    (comp (ref "R1002")
      (value "10K")
      (footprint "eagle-import:0402-RES")
      (fields (field (name "PARTNO") "RC0402FR-0710KL"))
      (libsource (lib "eagle-import") (part "RESISTOR0402-RES"))
    )
    (comp (ref "U1001")
      (value "BQ24313")
      (footprint "eagle-import:QFN8-DSG")
      (fields (field (name "PARTNO") "BQ24313DSGT"))
      (libsource (lib "eagle-import") (part "BQ24313"))
    )
    (comp (ref "U1002")
      (value "MIC5332")
      (footprint "eagle-import:MLF-8-EPAD")
      (fields (field (name "PARTNO") "MIC5332-SSYMT"))
      (libsource (lib "eagle-import") (part "MIC5332"))
    )
    (comp (ref "C501")
      (value "10u/10V")
      (footprint "eagle-import:0805-CAP")
      (fields (field (name "PARTNO") "CC0805ZKY5V6BB106"))
      (libsource (lib "eagle-import") (part "CAP0805"))
    )
    (comp (ref "C502")
      (value "0u1")
      (footprint "eagle-import:0402-CAP")
      (fields (field (name "PARTNO") "CC0402ZRY5V7BB104"))
      (libsource (lib "eagle-import") (part "CAP0402"))
    )
    (comp (ref "C503")
      (value "0u1")
      (footprint "eagle-import:0402-CAP")
      (fields (field (name "PARTNO") "CC0402ZRY5V7BB104"))
      (libsource (lib "eagle-import") (part "CAP0402"))
    )
    (comp (ref "C504")
      (value "10n")
      (footprint "eagle-import:0402-CAP")
      (fields (field (name "PARTNO") "CC0402KRX7R7BB103"))
      (libsource (lib "eagle-import") (part "CAP0402"))
    )
    (comp (ref "C505")
      (value "10n")
      (footprint "eagle-import:0402-CAP")
      (fields (field (name "PARTNO") "CC0402KRX7R7BB103"))
      (libsource (lib "eagle-import") (part "CAP0402"))
    )
    (comp (ref "C506")
      (value "10u/10V")
      (footprint "eagle-import:0805-CAP")
      (fields (field (name "PARTNO") "CC0805ZKY5V6BB106"))
      (libsource (lib "eagle-import") (part "CAP0805"))
    )
    (comp (ref "C507")
      (value "0u1")
      (footprint "eagle-import:0402-CAP")
      (fields (field (name "PARTNO") "CC0402ZRY5V7BB104"))
      (libsource (lib "eagle-import") (part "CAP0402"))
    )
    (comp (ref "C508")
      (value "0u1")
      (footprint "eagle-import:0402-CAP")
      (fields (field (name "PARTNO") "CC0402ZRY5V7BB104"))
      (libsource (lib "eagle-import") (part "CAP0402"))
    )
    (comp (ref "C509")
      (value "10u/10V")
      (footprint "eagle-import:0805-CAP")
      (fields (field (name "PARTNO") "CC0805ZKY5V6BB106"))
      (libsource (lib "eagle-import") (part "CAP0805"))
    )
    (comp (ref "C510")
      (value "0u47")
      (footprint "eagle-import:0402-CAP")
      (fields (field (name "PARTNO") "C1005X5R1C474K050BC"))
      (libsource (lib "eagle-import") (part "CAP0402"))
    )
    (comp (ref "C511")
      (value "10u/10V")
      (footprint "eagle-import:0805-CAP")
      (fields (field (name "PARTNO") "CC0805ZKY5V6BB106"))
      (libsource (lib "eagle-import") (part "CAP0805"))
    )
    (comp (ref "C512")
      (value "2u2")
      (footprint "eagle-import:0603-CAP")
      (fields (field (name "PARTNO") "C1608X6S1C225K080AC"))
      (libsource (lib "eagle-import") (part "CAP0603"))
    )
    (comp (ref "C513")
      (value "2u2")
      (footprint "eagle-import:0603-CAP")
      (fields (field (name "PARTNO") "C1608X6S1C225K080AC"))
      (libsource (lib "eagle-import") (part "CAP0603"))
    )
    (comp (ref "C514")
      (value "0u1")
      (footprint "eagle-import:0402-CAP")
      (fields (field (name "PARTNO") "CC0402ZRY5V7BB104"))
      (libsource (lib "eagle-import") (part "CAP0402"))
    )
    (comp (ref "C515")
      (value "0u01")
      (footprint "eagle-import:0603-CAP")
      (fields (field (name "PARTNO") "06033C103JAT2A"))
      (libsource (lib "eagle-import") (part "CAP0603"))
    )
    (comp (ref "U501")
      (value "L3GD20")
      (footprint "eagle-import:L3G4200DH-MAN")
      (libsource (lib "eagle-import") (part "L3G4200DH-LL"))
    )
    (comp (ref "U502")
      (value "L3GD20H")
      (footprint "eagle-import:LGA-16L")
      (libsource (lib "eagle-import") (part "L3GD20H"))
    )
    (comp (ref "U504")
      (value "LSM303D")
      (footprint "eagle-import:LGA-16L")
      (libsource (lib "eagle-import") (part "LSM303D"))
    )
    (comp (ref "U505")
      (value "MPU-6000")
      (footprint "eagle-import:QFN-24")
      (libsource (lib "eagle-import") (part "MPU-6000"))
    )
    (comp (ref "U506")
      (value "MS5611-01BA")
      (footprint "eagle-import:MS5611-01BA")
      (libsource (lib "eagle-import") (part "MS5611-01BA"))
    )
    (comp (ref "X503")
      (value "0512811094")
      (footprint "eagle-import:51281-1094")
      (fields (field (name "PARTNO") "0781191109"))
      (libsource (lib "eagle-import") (part "CONN_FPC_10RA"))
    )
    (comp (ref "!VBUS_VALID")
      (value "PAD.04")
      (footprint "eagle-import:PAD.04X.04")
      (libsource (lib "eagle-import") (part "PAD.04"))
    )
    (comp (ref "!VDD_BRICK_VALID")
      (value "PAD.04")
      (footprint "eagle-import:PAD.04X.04")
      (libsource (lib "eagle-import") (part "PAD.04"))
    )
    (comp (ref "!VDD_SERVO_VALID")
      (value "PAD.04")
      (footprint "eagle-import:PAD.04X.04")
      (libsource (lib "eagle-import") (part "PAD.04"))
    )
    (comp (ref "ADC_PR")
      (value "PAD.04")
      (footprint "eagle-import:PAD.04X.04")
      (libsource (lib "eagle-import") (part "PAD.04"))
    )
    (comp (ref "CAN_H")
      (value "PAD.04")
      (footprint "eagle-import:PAD.04X.04")
      (libsource (lib "eagle-import") (part "PAD.04"))
    )
    (comp (ref "CAN_L")
      (value "PAD.04")
      (footprint "eagle-import:PAD.04X.04")
      (libsource (lib "eagle-import") (part "PAD.04"))
    )
    (comp (ref "FMU-BOOT1101")
      (value "PAD.04")
      (footprint "eagle-import:PAD.04X.04")
      (libsource (lib "eagle-import") (part "PAD.04"))
    )
    (comp (ref "GND")
      (value "PAD.04")
      (footprint "eagle-import:PAD.04X.04")
      (libsource (lib "eagle-import") (part "PAD.04"))
    )
    (comp (ref "GND.")
      (value "PAD.04")
      (footprint "eagle-import:PAD.04X.04")
      (libsource (lib "eagle-import") (part "PAD.04"))
    )
    (comp (ref "IO-BOOT1101")
      (value "PAD.04")
      (footprint "eagle-import:PAD.04X.04")
      (libsource (lib "eagle-import") (part "PAD.04"))
    )
    (comp (ref "JP1")
      (value "FIDUCIAL1.5X3")
      (footprint "eagle-import:FIDUCIAL-1.5X3")
      (libsource (lib "eagle-import") (part "FIDUCIAL1.5X3"))
    )
    (comp (ref "JP2")
      (value "FIDUCIAL1.5X3")
      (footprint "eagle-import:FIDUCIAL-1.5X3")
      (libsource (lib "eagle-import") (part "FIDUCIAL1.5X3"))
    )
    (comp (ref "M3_MOUNT1101")
      (value "MOUNT-HOLE3.1MM")
      (footprint "eagle-import:MOUNT-HOLE3.1")
      (libsource (lib "eagle-import") (part "MOUNT-HOLE3.1MM"))
    )
    (comp (ref "M3_MOUNT1102")
      (value "MOUNT-HOLE3.1MM")
      (footprint "eagle-import:MOUNT-HOLE3.1")
      (libsource (lib "eagle-import") (part "MOUNT-HOLE3.1MM"))
    )
    (comp (ref "M3_MOUNT1103")
      (value "MOUNT-HOLE3.1MM")
      (footprint "eagle-import:MOUNT-HOLE3.1")
      (libsource (lib "eagle-import") (part "MOUNT-HOLE3.1MM"))
    )
    (comp (ref "M3_MOUNT1104")
      (value "MOUNT-HOLE3.1MM")
      (footprint "eagle-import:MOUNT-HOLE3.1")
      (libsource (lib "eagle-import") (part "MOUNT-HOLE3.1MM"))
    )
    (comp (ref "OSHW_LOGO")
      (value "OSHW-LOGOS")
      (footprint "eagle-import:OSHW-LOGO-S")
      (libsource (lib "eagle-import") (part "OSHW-LOGOS"))
    )
    (comp (ref "S1RX")
      (value "PAD.04")
      (footprint "eagle-import:PAD.04X.04")
      (libsource (lib "eagle-import") (part "PAD.04"))
    )
    (comp (ref "S1TX")
      (value "PAD.04")
      (footprint "eagle-import:PAD.04X.04")
      (libsource (lib "eagle-import") (part "PAD.04"))
    )
    (comp (ref "S2RX")
      (value "PAD.04")
      (footprint "eagle-import:PAD.04X.04")
      (libsource (lib "eagle-import") (part "PAD.04"))
    )
    (comp (ref "S2TX")
      (value "PAD.04")
      (footprint "eagle-import:PAD.04X.04")
      (libsource (lib "eagle-import") (part "PAD.04"))
    )
    (comp (ref "S3RX")
      (value "PAD.04")
      (footprint "eagle-import:PAD.04X.04")
      (libsource (lib "eagle-import") (part "PAD.04"))
    )
    (comp (ref "S3TX")
      (value "PAD.04")
      (footprint "eagle-import:PAD.04X.04")
      (libsource (lib "eagle-import") (part "PAD.04"))
    )
    (comp (ref "S4RX")
      (value "PAD.04")
      (footprint "eagle-import:PAD.04X.04")
      (libsource (lib "eagle-import") (part "PAD.04"))
    )
    (comp (ref "S4TX")
      (value "PAD.04")
      (footprint "eagle-import:PAD.04X.04")
      (libsource (lib "eagle-import") (part "PAD.04"))
    )
    (comp (ref "S5_RX")
      (value "PAD.04")
      (footprint "eagle-import:PAD.04X.04")
      (libsource (lib "eagle-import") (part "PAD.04"))
    )
    (comp (ref "S5_TX")
      (value "PAD.04")
      (footprint "eagle-import:PAD.04X.04")
      (libsource (lib "eagle-import") (part "PAD.04"))
    )
    (comp (ref "VBUS")
      (value "PAD.04")
      (footprint "eagle-import:PAD.04X.04")
      (libsource (lib "eagle-import") (part "PAD.04"))
    )
    (comp (ref "VDDA_3V1101")
      (value "PAD.04")
      (footprint "eagle-import:PAD.04X.04")
      (libsource (lib "eagle-import") (part "PAD.04"))
    )
    (comp (ref "VDD_3V1101")
      (value "PAD.04")
      (footprint "eagle-import:PAD.04X.04")
      (libsource (lib "eagle-import") (part "PAD.04"))
    )
    (comp (ref "VDD_5V_BRICK")
      (value "PAD.04")
      (footprint "eagle-import:PAD.04X.04")
      (libsource (lib "eagle-import") (part "PAD.04"))
    )
    (comp (ref "VDD_5V_IN")
      (value "PAD.04")
      (footprint "eagle-import:PAD.04X.04")
      (libsource (lib "eagle-import") (part "PAD.04"))
    )
    (comp (ref "VDD_SERVO")
      (value "PAD.04")
      (footprint "eagle-import:PAD.04X.04")
      (libsource (lib "eagle-import") (part "PAD.04"))
    )
    (comp (ref "C901")
      (value "0u1")
      (footprint "eagle-import:0402-CAP")
      (fields (field (name "PARTNO") "CC0402ZRY5V7BB104"))
      (libsource (lib "eagle-import") (part "CAP0402"))
    )
    (comp (ref "C902")
      (value "0u1")
      (footprint "eagle-import:0402-CAP")
      (fields (field (name "PARTNO") "CC0402ZRY5V7BB104"))
      (libsource (lib "eagle-import") (part "CAP0402"))
    )
    (comp (ref "C903")
      (value "0u1")
      (footprint "eagle-import:0402-CAP")
      (fields (field (name "PARTNO") "CC0402ZRY5V7BB104"))
      (libsource (lib "eagle-import") (part "CAP0402"))
    )
    (comp (ref "D901")
      (value "PESD0402-140")
      (footprint "eagle-import:0402-TVS")
      (libsource (lib "eagle-import") (part "DIODE-TVS"))
    )
    (comp (ref "D902")
      (value "PESD0402-140")
      (footprint "eagle-import:0402-TVS")
      (libsource (lib "eagle-import") (part "DIODE-TVS"))
    )
    (comp (ref "D903")
      (value "PESD0402-140")
      (footprint "eagle-import:0402-TVS")
      (libsource (lib "eagle-import") (part "DIODE-TVS"))
    )
    (comp (ref "D904")
      (value "MSS1P4-M3")
      (footprint "eagle-import:MICROSMP")
      (fields (field (name "PARTNO") "MSS1P4-M3/89A"))
      (libsource (lib "eagle-import") (part "DIODE-SCHOTTKY_MSMP"))
    )
    (comp (ref "J901")
      (value "HEADER-3X163X16RA")
      (footprint "eagle-import:3X16RA")
      (fields (field (name "BOM") "EXCLUDE"))
      (libsource (lib "eagle-import") (part "HEADER-3X163X16RA"))
    )
    (comp (ref "L901")
      (value "KNH16C104DA5TS")
      (footprint "eagle-import:KYOCERA-KNH16-DA")
      (libsource (lib "eagle-import") (part "KNH16C104DA5TS"))
    )
    (comp (ref "R901")
      (value "10K")
      (footprint "eagle-import:0402-RES")
      (fields (field (name "PARTNO") "RC0402FR-0710KL"))
      (libsource (lib "eagle-import") (part "RESISTOR0402-RES"))
    )
    (comp (ref "R902")
      (value "220R")
      (footprint "eagle-import:0402-RES")
      (fields (field (name "PARTNO") "RC0402FR-07220RL"))
      (libsource (lib "eagle-import") (part "RESISTOR0402-RES"))
    )
    (comp (ref "R903")
      (value "220R")
      (footprint "eagle-import:0402-RES")
      (fields (field (name "PARTNO") "RC0402FR-07220RL"))
      (libsource (lib "eagle-import") (part "RESISTOR0402-RES"))
    )
    (comp (ref "R904")
      (value "220R")
      (footprint "eagle-import:0402-RES")
      (fields (field (name "PARTNO") "RC0402FR-07220RL"))
      (libsource (lib "eagle-import") (part "RESISTOR0402-RES"))
    )
    (comp (ref "R905")
      (value "220R")
      (footprint "eagle-import:0402-RES")
      (fields (field (name "PARTNO") "RC0402FR-07220RL"))
      (libsource (lib "eagle-import") (part "RESISTOR0402-RES"))
    )
    (comp (ref "R906")
      (value "220R")
      (footprint "eagle-import:0402-RES")
      (fields (field (name "PARTNO") "RC0402FR-07220RL"))
      (libsource (lib "eagle-import") (part "RESISTOR0402-RES"))
    )
    (comp (ref "R907")
      (value "220R")
      (footprint "eagle-import:0402-RES")
      (fields (field (name "PARTNO") "RC0402FR-07220RL"))
      (libsource (lib "eagle-import") (part "RESISTOR0402-RES"))
    )
    (comp (ref "R908")
      (value "220R")
      (footprint "eagle-import:0402-RES")
      (fields (field (name "PARTNO") "RC0402FR-07220RL"))
      (libsource (lib "eagle-import") (part "RESISTOR0402-RES"))
    )
    (comp (ref "R909")
      (value "220R")
      (footprint "eagle-import:0402-RES")
      (fields (field (name "PARTNO") "RC0402FR-07220RL"))
      (libsource (lib "eagle-import") (part "RESISTOR0402-RES"))
    )
    (comp (ref "R910")
      (value "220R")
      (footprint "eagle-import:0402-RES")
      (fields (field (name "PARTNO") "RC0402FR-07220RL"))
      (libsource (lib "eagle-import") (part "RESISTOR0402-RES"))
    )
    (comp (ref "R911")
      (value "220R")
      (footprint "eagle-import:0402-RES")
      (fields (field (name "PARTNO") "RC0402FR-07220RL"))
      (libsource (lib "eagle-import") (part "RESISTOR0402-RES"))
    )
    (comp (ref "R912")
      (value "220R")
      (footprint "eagle-import:0402-RES")
      (fields (field (name "PARTNO") "RC0402FR-07220RL"))
      (libsource (lib "eagle-import") (part "RESISTOR0402-RES"))
    )
    (comp (ref "R913")
      (value "220R")
      (footprint "eagle-import:0402-RES")
      (fields (field (name "PARTNO") "RC0402FR-07220RL"))
      (libsource (lib "eagle-import") (part "RESISTOR0402-RES"))
    )
    (comp (ref "R914")
      (value "220R")
      (footprint "eagle-import:0402-RES")
      (fields (field (name "PARTNO") "RC0402FR-07220RL"))
      (libsource (lib "eagle-import") (part "RESISTOR0402-RES"))
    )
    (comp (ref "R915")
      (value "220R")
      (footprint "eagle-import:0402-RES")
      (fields (field (name "PARTNO") "RC0402FR-07220RL"))
      (libsource (lib "eagle-import") (part "RESISTOR0402-RES"))
    )
    (comp (ref "R916")
      (value "220R")
      (footprint "eagle-import:0402-RES")
      (fields (field (name "PARTNO") "RC0402FR-07220RL"))
      (libsource (lib "eagle-import") (part "RESISTOR0402-RES"))
    )
    (comp (ref "R917")
      (value "220R")
      (footprint "eagle-import:0402-RES")
      (fields (field (name "PARTNO") "RC0402FR-07220RL"))
      (libsource (lib "eagle-import") (part "RESISTOR0402-RES"))
    )
    (comp (ref "R918")
      (value "10K/0.1%")
      (footprint "eagle-import:0402-RES")
      (fields (field (name "PARTNO") "ERA-2AEB103X"))
      (libsource (lib "eagle-import") (part "RESISTOR0402-RES"))
    )
    (comp (ref "R919")
      (value "10K/0.1%")
      (footprint "eagle-import:0402-RES")
      (fields (field (name "PARTNO") "ERA-2AEB103X"))
      (libsource (lib "eagle-import") (part "RESISTOR0402-RES"))
    )
    (comp (ref "R922")
      (value "10K/0.1%")
      (footprint "eagle-import:0402-RES")
      (fields (field (name "PARTNO") "ERA-2AEB103X"))
      (libsource (lib "eagle-import") (part "RESISTOR0402-RES"))
    )
    (comp (ref "U901")
      (value "TXS0108QFN20")
      (footprint "eagle-import:QFN20-RGY")
      (fields (field (name "PARTNO") "TXS0108ERGYR"))
      (libsource (lib "eagle-import") (part "TXS0108QFN20"))
    )
    (comp (ref "U902")
      (value "TXS0108QFN20")
      (footprint "eagle-import:QFN20-RGY")
      (fields (field (name "PARTNO") "TXS0108ERGYR"))
      (libsource (lib "eagle-import") (part "TXS0108QFN20"))
    )
    (comp (ref "U903")
      (value "74LVC2G240")
      (footprint "eagle-import:TSSOP8_SOT505-2")
      (fields (field (name "PARTNO") "74LVC2G240DP,125"))
      (libsource (lib "eagle-import") (part "74LVC2G240-TSSOP-8"))
    )
    (comp (ref "C1101")
      (value "22u/25V")
      (footprint "eagle-import:0805-CAP")
      (fields (field (name "PARTNO") "CL21A226MAQNNNE"))
      (libsource (lib "eagle-import") (part "CAP0805"))
    )
    (comp (ref "C1102")
      (value "22u/25V")
      (footprint "eagle-import:0805-CAP")
      (fields (field (name "PARTNO") "CL21A226MAQNNNE"))
      (libsource (lib "eagle-import") (part "CAP0805"))
    )
    (comp (ref "C1103")
      (value "22u/25V")
      (footprint "eagle-import:0805-CAP")
      (fields (field (name "PARTNO") "CL21A226MAQNNNE"))
      (libsource (lib "eagle-import") (part "CAP0805"))
    )
    (comp (ref "C1104")
      (value "100u")
      (footprint "eagle-import:1206-CAP")
      (fields (field (name "PARTNO") "C3216X5R1A107M160AC"))
      (libsource (lib "eagle-import") (part "CAP1206"))
    )
    (comp (ref "C1105")
      (value "0u1")
      (footprint "eagle-import:0402-CAP")
      (fields (field (name "PARTNO") "C1005X7R1E104K050BB"))
      (libsource (lib "eagle-import") (part "CAP0402"))
    )
    (comp (ref "C1106")
      (value "0u1")
      (footprint "eagle-import:0402-CAP")
      (fields (field (name "PARTNO") "C1005X7R1E104K050BB"))
      (libsource (lib "eagle-import") (part "CAP0402"))
    )
    (comp (ref "C1107")
      (value "0u1")
      (footprint "eagle-import:0402-CAP")
      (fields (field (name "PARTNO") "C1005X7R1E104K050BB"))
      (libsource (lib "eagle-import") (part "CAP0402"))
    )
    (comp (ref "C1108")
      (value "1000p/25V")
      (footprint "eagle-import:0402-CAP")
      (fields (field (name "PARTNO") "GRM1555C1E102JA01D"))
      (libsource (lib "eagle-import") (part "CAP0402"))
    )
    (comp (ref "C1109")
      (value "1000p/25V")
      (footprint "eagle-import:0402-CAP")
      (fields (field (name "PARTNO") "GRM1555C1E102JA01D"))
      (libsource (lib "eagle-import") (part "CAP0402"))
    )
    (comp (ref "C1110")
      (value "1000p/25V")
      (footprint "eagle-import:0402-CAP")
      (fields (field (name "PARTNO") "GRM1555C1E102JA01D"))
      (libsource (lib "eagle-import") (part "CAP0402"))
    )
    (comp (ref "J601")
      (value "DF13C-6P-1.25V")
      (footprint "eagle-import:DF13C-6P-1.25V")
      (fields (field (name "PARTNO") "DF13C-6P-1.25V(20)"))
      (libsource (lib "eagle-import") (part "DF13-6P-1.25V"))
    )
    (comp (ref "L1101")
      (value "KNH16C104DA5TS")
      (footprint "eagle-import:KYOCERA-KNH16-DA")
      (libsource (lib "eagle-import") (part "KNH16C104DA5TS"))
    )
    (comp (ref "L1102")
      (value "KNH16C104DA5TS")
      (footprint "eagle-import:KYOCERA-KNH16-DA")
      (libsource (lib "eagle-import") (part "KNH16C104DA5TS"))
    )
    (comp (ref "R1101")
      (value "10K/0.1%")
      (footprint "eagle-import:0402-RES")
      (fields (field (name "PARTNO") "ERA-2AEB103X"))
      (libsource (lib "eagle-import") (part "RESISTOR0402-RES"))
    )
    (comp (ref "R1102")
      (value "10K/0.1%")
      (footprint "eagle-import:0402-RES")
      (fields (field (name "PARTNO") "ERA-2AEB103X"))
      (libsource (lib "eagle-import") (part "RESISTOR0402-RES"))
    )
    (comp (ref "R1103")
      (value "1M")
      (footprint "eagle-import:0402-RES")
      (fields (field (name "PARTNO") "RC0402FR-071ML"))
      (libsource (lib "eagle-import") (part "RESISTOR0402-RES"))
    )
    (comp (ref "R1104")
      (value "1M")
      (footprint "eagle-import:0402-RES")
      (fields (field (name "PARTNO") "RC0402FR-071ML"))
      (libsource (lib "eagle-import") (part "RESISTOR0402-RES"))
    )
    (comp (ref "R1105")
      (value "453K")
      (footprint "eagle-import:0402-RES")
      (fields (field (name "PARTNO") "RMCF0402FT453K"))
      (libsource (lib "eagle-import") (part "RESISTOR0402-RES"))
    )
    (comp (ref "R1106")
      (value "56K")
      (footprint "eagle-import:0402-RES")
      (fields (field (name "PARTNO") "ERA-2AEB563X"))
      (libsource (lib "eagle-import") (part "RESISTOR0402-RES"))
    )
    (comp (ref "R1107")
      (value "105K")
      (footprint "eagle-import:0402-RES")
      (fields (field (name "PARTNO") "ERJ-2RKF1053X"))
      (libsource (lib "eagle-import") (part "RESISTOR0402-RES"))
    )
    (comp (ref "R1109")
      (value "453K")
      (footprint "eagle-import:0402-RES")
      (fields (field (name "PARTNO") "RMCF0402FT453K"))
      (libsource (lib "eagle-import") (part "RESISTOR0402-RES"))
    )
    (comp (ref "R1110")
      (value "56K")
      (footprint "eagle-import:0402-RES")
      (fields (field (name "PARTNO") "ERA-2AEB563X"))
      (libsource (lib "eagle-import") (part "RESISTOR0402-RES"))
    )
    (comp (ref "R1111")
      (value "105K")
      (footprint "eagle-import:0402-RES")
      (fields (field (name "PARTNO") "ERJ-2RKF1053X"))
      (libsource (lib "eagle-import") (part "RESISTOR0402-RES"))
    )
    (comp (ref "R1112")
      (value "453K")
      (footprint "eagle-import:0402-RES")
      (fields (field (name "PARTNO") "RMCF0402FT453K"))
      (libsource (lib "eagle-import") (part "RESISTOR0402-RES"))
    )
    (comp (ref "R1113")
      (value "56K")
      (footprint "eagle-import:0402-RES")
      (fields (field (name "PARTNO") "ERA-2AEB563X"))
      (libsource (lib "eagle-import") (part "RESISTOR0402-RES"))
    )
    (comp (ref "R1114")
      (value "105K")
      (footprint "eagle-import:0402-RES")
      (fields (field (name "PARTNO") "ERJ-2RKF1053X"))
      (libsource (lib "eagle-import") (part "RESISTOR0402-RES"))
    )
    (comp (ref "R1115")
      (value "0R")
      (footprint "eagle-import:0402-RES")
      (fields (field (name "PARTNO") "ERJ-2GE0R00X"))
      (libsource (lib "eagle-import") (part "RESISTOR0402-RES"))
    )
    (comp (ref "RN1101")
      (value "1M")
      (footprint "eagle-import:EXB28V")
      (fields (field (name "PARTNO") "EXB-28V105JX"))
      (libsource (lib "eagle-import") (part "4R-NEXB28V"))
    )
    (comp (ref "U1101")
      (value "LTC4417")
      (footprint "eagle-import:MO-220")
      (fields (field (name "PARTNO") "LTC4417IUF#PBF"))
      (libsource (lib "eagle-import") (part "LTC4117"))
    )
    (comp (ref "U1102")
      (value "NTHD4102PT1G")
      (footprint "eagle-import:1206-8")
      (fields (field (name "PARTNO") "NTHD4102PT1G"))
      (libsource (lib "eagle-import") (part "MOSFET-DUAL-PCHANNEL-CHIPFET"))
    )
    (comp (ref "U1103")
      (value "NTHD4102PT1G")
      (footprint "eagle-import:1206-8")
      (fields (field (name "PARTNO") "NTHD4102PT1G"))
      (libsource (lib "eagle-import") (part "MOSFET-DUAL-PCHANNEL-CHIPFET"))
    )
    (comp (ref "U1104")
      (value "NTHD4102PT1G")
      (footprint "eagle-import:1206-8")
      (fields (field (name "PARTNO") "NTHD4102PT1G"))
      (libsource (lib "eagle-import") (part "MOSFET-DUAL-PCHANNEL-CHIPFET"))
    )
    (comp (ref "C801")
      (value "0u1")
      (footprint "eagle-import:0402-CAP")
      (fields (field (name "PARTNO") "CC0402ZRY5V7BB104"))
      (libsource (lib "eagle-import") (part "CAP0402"))
    )
    (comp (ref "C802")
      (value "0u1")
      (footprint "eagle-import:0402-CAP")
      (fields (field (name "PARTNO") "CC0402ZRY5V7BB104"))
      (libsource (lib "eagle-import") (part "CAP0402"))
    )
    (comp (ref "C803")
      (value "0u1")
      (footprint "eagle-import:0402-CAP")
      (fields (field (name "PARTNO") "CC0402ZRY5V7BB104"))
      (libsource (lib "eagle-import") (part "CAP0402"))
    )
    (comp (ref "C804")
      (value "0u1")
      (footprint "eagle-import:0402-CAP")
      (fields (field (name "PARTNO") "CC0402ZRY5V7BB104"))
      (libsource (lib "eagle-import") (part "CAP0402"))
    )
    (comp (ref "C805")
      (value "8p")
      (footprint "eagle-import:0402-CAP")
      (fields (field (name "PARTNO") "C1005C0G1H080C"))
      (libsource (lib "eagle-import") (part "CAP0402"))
    )
    (comp (ref "C806")
      (value "8p")
      (footprint "eagle-import:0402-CAP")
      (fields (field (name "PARTNO") "C1005C0G1H080C"))
      (libsource (lib "eagle-import") (part "CAP0402"))
    )
    (comp (ref "D801")
      (value "PESD0402-140")
      (footprint "eagle-import:0402-TVS")
      (libsource (lib "eagle-import") (part "DIODE-TVS"))
    )
    (comp (ref "J801")
      (value "JST-ZH-3")
      (footprint "eagle-import:JST-ZH-SMT-VERTICAL")
      (fields (field (name "PARTNO") "B3B-ZR-SM4-TF (LF)(SN)(P)"))
      (libsource (lib "eagle-import") (part "JST-ZH-3"))
    )
    (comp (ref "JX801")
      (value "HEADER-3X1BOARDEDGE-SHORT")
      (footprint "eagle-import:HEADER_3X01_SMD_H_BOARD_EDGE_SHORT")
      (libsource (lib "eagle-import") (part "HEADER-3X1BOARDEDGE-SHORT"))
    )
    (comp (ref "JX802")
      (value "ARM_MINI_JTAG-SMT")
      (footprint "eagle-import:FTSH-105-01-XXX-DV-K")
      (fields (field (name "BOM") "EXCLUDE") (field (name "PARTNO") "M50-3900542"))
      (libsource (lib "eagle-import") (part "ARM_MINI_JTAG-SMT"))
    )
    (comp (ref "R801")
      (value "10K")
      (footprint "eagle-import:0402-RES")
      (fields (field (name "PARTNO") "RC0402FR-0710KL"))
      (libsource (lib "eagle-import") (part "RESISTOR0402-RES"))
    )
    (comp (ref "R802")
      (value "10K")
      (footprint "eagle-import:0402-RES")
      (fields (field (name "PARTNO") "RC0402FR-0710KL"))
      (libsource (lib "eagle-import") (part "RESISTOR0402-RES"))
    )
    (comp (ref "R803")
      (value "220R")
      (footprint "eagle-import:0402-RES")
      (fields (field (name "PARTNO") "RC0402FR-07220RL"))
      (libsource (lib "eagle-import") (part "RESISTOR0402-RES"))
    )
    (comp (ref "R804")
      (value "220R")
      (footprint "eagle-import:0402-RES")
      (fields (field (name "PARTNO") "RC0402FR-07220RL"))
      (libsource (lib "eagle-import") (part "RESISTOR0402-RES"))
    )
    (comp (ref "S801")
      (value "RESET")
      (footprint "eagle-import:EVQP7J01K")
      (fields (field (name "PARTNO") "EVQ-P7J01P"))
      (libsource (lib "eagle-import") (part "SWITCH-MOMENTARY-2"))
    )
    (comp (ref "U801")
      (value "STM32F10XCXT6")
      (footprint "eagle-import:TQFP48")
      (fields (field (name "PARTNO") "STM32F100C8T6B"))
      (libsource (lib "eagle-import") (part "STM32F10XCXT6"))
    )
    (comp (ref "X801")
      (value "3.2x2.5 mm / 24 MHz / 15 ppm")
      (footprint "eagle-import:OSCILLATOR-3.2X2.5")
      (fields (field (name "PARTNO") "NX3225SA-24.000000MHZ"))
      (libsource (lib "eagle-import") (part "OSCILLATOR-3.2X2.5"))
    )
    (comp (ref "C401")
      (value "0u1")
      (footprint "eagle-import:0402-CAP")
      (fields (field (name "PARTNO") "CC0402ZRY5V7BB104"))
      (libsource (lib "eagle-import") (part "CAP0402"))
    )
    (comp (ref "C402")
      (value "0u1")
      (footprint "eagle-import:0402-CAP")
      (fields (field (name "PARTNO") "CC0402ZRY5V7BB104"))
      (libsource (lib "eagle-import") (part "CAP0402"))
    )
    (comp (ref "D401")
      (value "PESD0402-140")
      (footprint "eagle-import:0402-TVS")
      (libsource (lib "eagle-import") (part "DIODE-TVS"))
    )
    (comp (ref "D402")
      (value "PESD0402-140")
      (footprint "eagle-import:0402-TVS")
      (libsource (lib "eagle-import") (part "DIODE-TVS"))
    )
    (comp (ref "D403")
      (value "PESD0402-140")
      (footprint "eagle-import:0402-TVS")
      (libsource (lib "eagle-import") (part "DIODE-TVS"))
    )
    (comp (ref "D404")
      (value "PESD0402-140")
      (footprint "eagle-import:0402-TVS")
      (libsource (lib "eagle-import") (part "DIODE-TVS"))
    )
    (comp (ref "J401")
      (value "DF13C-4P-1.25V")
      (footprint "eagle-import:DF13C-4P-1.25V")
      (fields (field (name "PARTNO") "DF13C-4P-1.25V(20)"))
      (libsource (lib "eagle-import") (part "DF13-4P-1.25V"))
    )
    (comp (ref "J402")
      (value "DF13C-3P-1.25V")
      (footprint "eagle-import:DF13C-3P-1.25V")
      (fields (field (name "PARTNO") "DF13C-3P-1.25V(20)"))
      (libsource (lib "eagle-import") (part "DF13-3P-1.25V"))
    )
    (comp (ref "J403")
      (value "DF13C-7P-1.25V")
      (footprint "eagle-import:DF13C-7P-1.25V")
      (fields (field (name "PARTNO") "DF13C-7P-1.25V(20)"))
      (libsource (lib "eagle-import") (part "DF13-7P-1.25V"))
    )
    (comp (ref "J404")
      (value "DF13C-5P-1.25V")
      (footprint "eagle-import:DF13C-5P-1.25V")
      (fields (field (name "PARTNO") "DF13C-5P-1.25V(20)"))
      (libsource (lib "eagle-import") (part "DF13-5P-1.25V"))
    )
    (comp (ref "J405")
      (value "DF13C-4P-1.25V")
      (footprint "eagle-import:DF13C-4P-1.25V")
      (fields (field (name "PARTNO") "DF13C-4P-1.25V(20)"))
      (libsource (lib "eagle-import") (part "DF13-4P-1.25V"))
    )
    (comp (ref "L401")
      (value "KNH16C104DA5TS")
      (footprint "eagle-import:KYOCERA-KNH16-DA")
      (libsource (lib "eagle-import") (part "KNH16C104DA5TS"))
    )
    (comp (ref "L402")
      (value "KNH16C104DA5TS")
      (footprint "eagle-import:KYOCERA-KNH16-DA")
      (libsource (lib "eagle-import") (part "KNH16C104DA5TS"))
    )
    (comp (ref "L403")
      (value "KNH16C104DA5TS")
      (footprint "eagle-import:KYOCERA-KNH16-DA")
      (libsource (lib "eagle-import") (part "KNH16C104DA5TS"))
    )
    (comp (ref "L404")
      (value "KNH16C104DA5TS")
      (footprint "eagle-import:KYOCERA-KNH16-DA")
      (libsource (lib "eagle-import") (part "KNH16C104DA5TS"))
    )
    (comp (ref "R401")
      (value "1K5")
      (footprint "eagle-import:0402-RES")
      (fields (field (name "PARTNO") "RC0402FR-071K5L"))
      (libsource (lib "eagle-import") (part "RESISTOR0402-RES"))
    )
    (comp (ref "R402")
      (value "1K5")
      (footprint "eagle-import:0402-RES")
      (fields (field (name "PARTNO") "RC0402FR-071K5L"))
      (libsource (lib "eagle-import") (part "RESISTOR0402-RES"))
    )
    (comp (ref "R403")
      (value "10K/0.1%")
      (footprint "eagle-import:0402-RES")
      (fields (field (name "PARTNO") "ERA-2AEB103X"))
      (libsource (lib "eagle-import") (part "RESISTOR0402-RES"))
    )
    (comp (ref "R404")
      (value "120R")
      (footprint "eagle-import:0402-RES")
      (fields (field (name "PARTNO") "RC0402FR-07120RL"))
      (libsource (lib "eagle-import") (part "RESISTOR0402-RES"))
    )
    (comp (ref "R405")
      (value "120R")
      (footprint "eagle-import:0402-RES")
      (fields (field (name "PARTNO") "RC0402FR-07120RL"))
      (libsource (lib "eagle-import") (part "RESISTOR0402-RES"))
    )
    (comp (ref "R406")
      (value "10K/0.1%")
      (footprint "eagle-import:0402-RES")
      (fields (field (name "PARTNO") "ERA-2AEB103X"))
      (libsource (lib "eagle-import") (part "RESISTOR0402-RES"))
    )
    (comp (ref "R407")
      (value "10K/0.1%")
      (footprint "eagle-import:0402-RES")
      (fields (field (name "PARTNO") "ERA-2AEB103X"))
      (libsource (lib "eagle-import") (part "RESISTOR0402-RES"))
    )
    (comp (ref "R408")
      (value "10K/0.1%")
      (footprint "eagle-import:0402-RES")
      (fields (field (name "PARTNO") "ERA-2AEB103X"))
      (libsource (lib "eagle-import") (part "RESISTOR0402-RES"))
    )
    (comp (ref "R409")
      (value "120R")
      (footprint "eagle-import:0402-RES")
      (fields (field (name "PARTNO") "RC0402FR-07120RL"))
      (libsource (lib "eagle-import") (part "RESISTOR0402-RES"))
    )
    (comp (ref "U401")
      (value "MAX3051")
      (footprint "eagle-import:SOT23-8")
      (fields (field (name "PARTNO") "MAX3051EKA"))
      (libsource (lib "eagle-import") (part "MAX3051MAX3051EKA"))
    )
    (comp (ref "C701")
      (value "0u1")
      (footprint "eagle-import:0402-CAP")
      (fields (field (name "PARTNO") "CC0402ZRY5V7BB104"))
      (libsource (lib "eagle-import") (part "CAP0402"))
    )
    (comp (ref "C702")
      (value "1u")
      (footprint "eagle-import:0603-CAP")
      (fields (field (name "PARTNO") "CC0603ZRY5V7BB105"))
      (libsource (lib "eagle-import") (part "CAP0603"))
    )
    (comp (ref "C703")
      (value "5n6")
      (footprint "eagle-import:0402-CAP")
      (fields (field (name "PARTNO") "C0402C562K5RACTU"))
      (libsource (lib "eagle-import") (part "CAP0402"))
    )
    (comp (ref "C704")
      (value "0u47")
      (footprint "eagle-import:0402-CAP")
      (fields (field (name "PARTNO") "C1005X5R1C474K050BC"))
      (libsource (lib "eagle-import") (part "CAP0402"))
    )
    (comp (ref "D701")
      (value "PESD0402-140")
      (footprint "eagle-import:0402-TVS")
      (libsource (lib "eagle-import") (part "DIODE-TVS"))
    )
    (comp (ref "J701")
      (value "DF13C-2P-1.25V")
      (footprint "eagle-import:DF13C-2P-1.25V")
      (fields (field (name "PARTNO") "DF13C-2P-1.25V(20)"))
      (libsource (lib "eagle-import") (part "DF13-2P-1.25V"))
    )
    (comp (ref "J702")
      (value "DF13C-3P-1.25V")
      (footprint "eagle-import:DF13C-3P-1.25V")
      (fields (field (name "PARTNO") "DF13C-3P-1.25V(20)"))
      (libsource (lib "eagle-import") (part "DF13-3P-1.25V"))
    )
    (comp (ref "L701")
      (value "47uH")
      (footprint "eagle-import:0805-IND")
      (fields (field (name "PARTNO") "MLZ2012M470W"))
      (libsource (lib "eagle-import") (part "INDUCTOR0805"))
    )
    (comp (ref "LED701")
      (value "AMBER")
      (footprint "eagle-import:0603-LED")
      (fields (field (name "PARTNO") "APTD1608SECK"))
      (libsource (lib "eagle-import") (part "LED0603"))
    )
    (comp (ref "LED702")
      (value "GREEN")
      (footprint "eagle-import:0603-LED")
      (fields (field (name "PARTNO") "APTD1608CGCK"))
      (libsource (lib "eagle-import") (part "LED0603"))
    )
    (comp (ref "LED703")
      (value "AMBER")
      (footprint "eagle-import:0603-LED")
      (fields (field (name "PARTNO") "APTD1608SECK"))
      (libsource (lib "eagle-import") (part "LED0603"))
    )
    (comp (ref "LED704")
      (value "GREEN")
      (footprint "eagle-import:0603-LED")
      (fields (field (name "PARTNO") "APTD1608CGCK"))
      (libsource (lib "eagle-import") (part "LED0603"))
    )
    (comp (ref "LED705")
      (value "BLUE")
      (footprint "eagle-import:0603-LED")
      (fields (field (name "PARTNO") "APTD1608QBC/D"))
      (libsource (lib "eagle-import") (part "LED0603"))
    )
    (comp (ref "R701")
      (value "9K09")
      (footprint "eagle-import:0402-RES")
      (fields (field (name "PARTNO") "RMCF0402FT9K09"))
      (libsource (lib "eagle-import") (part "RESISTOR0402-RES"))
    )
    (comp (ref "R702")
      (value "10K")
      (footprint "eagle-import:0402-RES")
      (fields (field (name "PARTNO") "RC0402FR-0710KL"))
      (libsource (lib "eagle-import") (part "RESISTOR0402-RES"))
    )
    (comp (ref "R703")
      (value "100K")
      (footprint "eagle-import:0402-RES")
      (fields (field (name "PARTNO") "RC0402FR-07100KL"))
      (libsource (lib "eagle-import") (part "RESISTOR0402-RES"))
    )
    (comp (ref "R704")
      (value "10K")
      (footprint "eagle-import:0402-RES")
      (fields (field (name "PARTNO") "RC0402FR-0710KL"))
      (libsource (lib "eagle-import") (part "RESISTOR0402-RES"))
    )
    (comp (ref "R705")
      (value "453K")
      (footprint "eagle-import:0402-RES")
      (fields (field (name "PARTNO") "RMCF0402FT453K"))
      (libsource (lib "eagle-import") (part "RESISTOR0402-RES"))
    )
    (comp (ref "R706")
      (value "16K5")
      (footprint "eagle-import:0402-RES")
      (fields (field (name "PARTNO") "RMCF0402FT16K5"))
      (libsource (lib "eagle-import") (part "RESISTOR0402-RES"))
    )
    (comp (ref "R707")
      (value "220R")
      (footprint "eagle-import:0402-RES")
      (fields (field (name "PARTNO") "RC0402FR-07220RL"))
      (libsource (lib "eagle-import") (part "RESISTOR0402-RES"))
    )
    (comp (ref "R708")
      (value "220R")
      (footprint "eagle-import:0402-RES")
      (fields (field (name "PARTNO") "RC0402FR-07220RL"))
      (libsource (lib "eagle-import") (part "RESISTOR0402-RES"))
    )
    (comp (ref "R709")
      (value "220R")
      (footprint "eagle-import:0402-RES")
      (fields (field (name "PARTNO") "RC0402FR-07220RL"))
      (libsource (lib "eagle-import") (part "RESISTOR0402-RES"))
    )
    (comp (ref "R710")
      (value "68R")
      (footprint "eagle-import:0402-RES")
      (fields (field (name "PARTNO") "ERJ-2GEJ680X"))
      (libsource (lib "eagle-import") (part "RESISTOR0402-RES"))
    )
    (comp (ref "R711")
      (value "220R")
      (footprint "eagle-import:0402-RES")
      (fields (field (name "PARTNO") "RC0402FR-07220RL"))
      (libsource (lib "eagle-import") (part "RESISTOR0402-RES"))
    )
    (comp (ref "R712")
      (value "220R")
      (footprint "eagle-import:0402-RES")
      (fields (field (name "PARTNO") "RC0402FR-07220RL"))
      (libsource (lib "eagle-import") (part "RESISTOR0402-RES"))
    )
    (comp (ref "R713")
      (value "1K5")
      (footprint "eagle-import:0402-RES")
      (fields (field (name "PARTNO") "RC0402FR-071K5L"))
      (libsource (lib "eagle-import") (part "RESISTOR0402-RES"))
    )
    (comp (ref "R735")
      (value "220R")
      (footprint "eagle-import:0402-RES")
      (fields (field (name "PARTNO") "RC0402FR-07220RL"))
      (libsource (lib "eagle-import") (part "RESISTOR0402-RES"))
    )
    (comp (ref "R736")
      (value "220R")
      (footprint "eagle-import:0402-RES")
      (fields (field (name "PARTNO") "RC0402FR-07220RL"))
      (libsource (lib "eagle-import") (part "RESISTOR0402-RES"))
    )
    (comp (ref "U701")
      (value "TCA62724FMG")
      (footprint "eagle-import:SON10")
      (libsource (lib "eagle-import") (part "TCA62724FMG"))
    )
    (comp (ref "U702")
      (value "LT3469")
      (footprint "eagle-import:SOT23-8")
      (fields (field (name "PARTNO") "LT3469ETS8"))
      (libsource (lib "eagle-import") (part "LT3469"))
    )
    (comp (ref "U703")
      (value "LRTB GFTG-T7AW-1+V7A7-29+R5T9-49-L")
      (footprint "eagle-import:6-PLCC")
      (fields (field (name "PARTNO") "LRTB GFTG-T7AW-1+V7A7-29+R5T9-49-L"))
      (libsource (lib "eagle-import") (part "RGB-LED6-PLCC"))
    )
    (comp (ref "J301")
      (value "47346-0001")
      (footprint "eagle-import:MOLEX-47346-0001")
      (libsource (lib "eagle-import") (part "MOLEX-47346-0001"))
    )
    (comp (ref "J302")
      (value "DF13C-4P-1.25V")
      (footprint "eagle-import:DF13C-4P-1.25V")
      (fields (field (name "PARTNO") "DF13C-4P-1.25V(20)"))
      (libsource (lib "eagle-import") (part "DF13-4P-1.25V"))
    )
    (comp (ref "JX301")
      (value "ARM_MINI_JTAG-SMT")
      (footprint "eagle-import:FTSH-105-01-XXX-DV-K")
      (fields (field (name "BOM") "EXCLUDE") (field (name "PARTNO") "M50-3900542"))
      (libsource (lib "eagle-import") (part "ARM_MINI_JTAG-SMT"))
    )
    (comp (ref "R301")
      (value "100K")
      (footprint "eagle-import:0402-RES")
      (fields (field (name "PARTNO") "RC0402FR-07100KL"))
      (libsource (lib "eagle-import") (part "RESISTOR0402-RES"))
    )
    (comp (ref "R302")
      (value "100K")
      (footprint "eagle-import:0402-RES")
      (fields (field (name "PARTNO") "RC0402FR-07100KL"))
      (libsource (lib "eagle-import") (part "RESISTOR0402-RES"))
    )
    (comp (ref "R303")
      (value "100K")
      (footprint "eagle-import:0402-RES")
      (fields (field (name "PARTNO") "RC0402FR-07100KL"))
      (libsource (lib "eagle-import") (part "RESISTOR0402-RES"))
    )
    (comp (ref "R304")
      (value "100K")
      (footprint "eagle-import:0402-RES")
      (fields (field (name "PARTNO") "RC0402FR-07100KL"))
      (libsource (lib "eagle-import") (part "RESISTOR0402-RES"))
    )
    (comp (ref "R305")
      (value "100K")
      (footprint "eagle-import:0402-RES")
      (fields (field (name "PARTNO") "RC0402FR-07100KL"))
      (libsource (lib "eagle-import") (part "RESISTOR0402-RES"))
    )
    (comp (ref "R306")
      (value "1K5")
      (footprint "eagle-import:0402-RES")
      (fields (field (name "PARTNO") "RC0402FR-071K5L"))
      (libsource (lib "eagle-import") (part "RESISTOR0402-RES"))
    )
    (comp (ref "R307")
      (value "1K5")
      (footprint "eagle-import:0402-RES")
      (fields (field (name "PARTNO") "RC0402FR-071K5L"))
      (libsource (lib "eagle-import") (part "RESISTOR0402-RES"))
    )
    (comp (ref "U301")
      (value "2908-05WB-MG")
      (footprint "eagle-import:MICROSD")
      (libsource (lib "eagle-import") (part "MICROSDSDI"))
    )
    (comp (ref "U302")
      (value "NUF2042XV6")
      (footprint "eagle-import:SOT563-6")
      (fields (field (name "PARTNO") "NUF2042XV6T1G"))
      (libsource (lib "eagle-import") (part "NUF2042XV6"))
    )
    (comp (ref "B601")
      (value "MS621FE")
      (footprint "eagle-import:MS621FE")
      (fields (field (name "PARTNO") "MS621FE-FL11E"))
      (libsource (lib "eagle-import") (part "MS621FE"))
    )
    (comp (ref "C601")
      (value "10u/25V")
      (footprint "eagle-import:0805-CAP")
      (fields (field (name "PARTNO") "CL21A106KAYNNNE"))
      (libsource (lib "eagle-import") (part "CAP0805"))
    )
    (comp (ref "C602")
      (value "10n")
      (footprint "eagle-import:0402-CAP")
      (fields (field (name "PARTNO") "CC0402KRX7R7BB103"))
      (libsource (lib "eagle-import") (part "CAP0402"))
    )
    (comp (ref "C603")
      (value "1u")
      (footprint "eagle-import:0603-CAP")
      (fields (field (name "PARTNO") "CC0603ZRY5V7BB105"))
      (libsource (lib "eagle-import") (part "CAP0603"))
    )
    (comp (ref "C604")
      (value "22u/25V")
      (footprint "eagle-import:0805-CAP")
      (fields (field (name "PARTNO") "CL21A226MAQNNNE"))
      (libsource (lib "eagle-import") (part "CAP0805"))
    )
    (comp (ref "C605")
      (value "22u/25V")
      (footprint "eagle-import:0805-CAP")
      (fields (field (name "PARTNO") "CL21A226MAQNNNE"))
      (libsource (lib "eagle-import") (part "CAP0805"))
    )
    (comp (ref "C606")
      (value "0u1")
      (footprint "eagle-import:0402-CAP")
      (fields (field (name "PARTNO") "CC0402ZRY5V7BB104"))
      (libsource (lib "eagle-import") (part "CAP0402"))
    )
    (comp (ref "C607")
      (value "0u1")
      (footprint "eagle-import:0402-CAP")
      (fields (field (name "PARTNO") "CC0402ZRY5V7BB104"))
      (libsource (lib "eagle-import") (part "CAP0402"))
    )
    (comp (ref "C608")
      (value "0u1")
      (footprint "eagle-import:0402-CAP")
      (fields (field (name "PARTNO") "CC0402ZRY5V7BB104"))
      (libsource (lib "eagle-import") (part "CAP0402"))
    )
    (comp (ref "C609")
      (value "0u1")
      (footprint "eagle-import:0402-CAP")
      (fields (field (name "PARTNO") "CC0402ZRY5V7BB104"))
      (libsource (lib "eagle-import") (part "CAP0402"))
    )
    (comp (ref "C610")
      (value "0u1")
      (footprint "eagle-import:0402-CAP")
      (fields (field (name "PARTNO") "CC0402ZRY5V7BB104"))
      (libsource (lib "eagle-import") (part "CAP0402"))
    )
    (comp (ref "C611")
      (value "2u2")
      (footprint "eagle-import:0603-CAP")
      (fields (field (name "PARTNO") "C1608X6S1C225K080AC"))
      (libsource (lib "eagle-import") (part "CAP0603"))
    )
    (comp (ref "C612")
      (value "0u1")
      (footprint "eagle-import:0402-CAP")
      (fields (field (name "PARTNO") "CC0402ZRY5V7BB104"))
      (libsource (lib "eagle-import") (part "CAP0402"))
    )
    (comp (ref "C613")
      (value "2u2")
      (footprint "eagle-import:0603-CAP")
      (fields (field (name "PARTNO") "C1608X6S1C225K080AC"))
      (libsource (lib "eagle-import") (part "CAP0603"))
    )
    (comp (ref "C614")
      (value "100u")
      (footprint "eagle-import:1206-CAP")
      (fields (field (name "PARTNO") "C3216X5R1A107M160AC"))
      (libsource (lib "eagle-import") (part "CAP1206"))
    )
    (comp (ref "C615")
      (value "0u1")
      (footprint "eagle-import:0402-CAP")
      (fields (field (name "PARTNO") "CC0402ZRY5V7BB104"))
      (libsource (lib "eagle-import") (part "CAP0402"))
    )
    (comp (ref "C616")
      (value "0u1")
      (footprint "eagle-import:0402-CAP")
      (fields (field (name "PARTNO") "CC0402ZRY5V7BB104"))
      (libsource (lib "eagle-import") (part "CAP0402"))
    )
    (comp (ref "C617")
      (value "0u1")
      (footprint "eagle-import:0402-CAP")
      (fields (field (name "PARTNO") "CC0402ZRY5V7BB104"))
      (libsource (lib "eagle-import") (part "CAP0402"))
    )
    (comp (ref "C618")
      (value "100u")
      (footprint "eagle-import:1206-CAP")
      (fields (field (name "PARTNO") "C3216X5R1A107M160AC"))
      (libsource (lib "eagle-import") (part "CAP1206"))
    )
    (comp (ref "D602")
      (value "RB751V40T1G")
      (footprint "eagle-import:SOD323")
      (libsource (lib "eagle-import") (part "DIODE-SCHOTTKY_SOD323"))
    )
    (comp (ref "L603")
      (value "KNH16C104DA5TS")
      (footprint "eagle-import:KYOCERA-KNH16-DA")
      (libsource (lib "eagle-import") (part "KNH16C104DA5TS"))
    )
    (comp (ref "Q601")
      (value "MMBT3906LT1SMD")
      (footprint "eagle-import:SOT23-BEC")
      (fields (field (name "PARTNO") "MMBT 3906 LT1"))
      (libsource (lib "eagle-import") (part "MMBT3906SMDLT1"))
    )
    (comp (ref "R602")
      (value "1M")
      (footprint "eagle-import:0402-RES")
      (fields (field (name "PARTNO") "RC0402FR-071ML"))
      (libsource (lib "eagle-import") (part "RESISTOR0402-RES"))
    )
    (comp (ref "R603")
      (value "10K")
      (footprint "eagle-import:0402-RES")
      (fields (field (name "PARTNO") "RC0402FR-0710KL"))
      (libsource (lib "eagle-import") (part "RESISTOR0402-RES"))
    )
    (comp (ref "R604")
      (value "1M")
      (footprint "eagle-import:0402-RES")
      (fields (field (name "PARTNO") "RC0402FR-071ML"))
      (libsource (lib "eagle-import") (part "RESISTOR0402-RES"))
    )
    (comp (ref "R608")
      (value "1K")
      (footprint "eagle-import:0402-RES")
      (fields (field (name "PARTNO") "RC0402FR-071KL"))
      (libsource (lib "eagle-import") (part "RESISTOR0402-RES"))
    )
    (comp (ref "R609")
      (value "10K/0.1%")
      (footprint "eagle-import:0402-RES")
      (fields (field (name "PARTNO") "ERA-2AEB103X"))
      (libsource (lib "eagle-import") (part "RESISTOR0402-RES"))
    )
    (comp (ref "R610")
      (value "10K/0.1%")
      (footprint "eagle-import:0402-RES")
      (fields (field (name "PARTNO") "ERA-2AEB103X"))
      (libsource (lib "eagle-import") (part "RESISTOR0402-RES"))
    )
    (comp (ref "R611")
      (value "10K")
      (footprint "eagle-import:0402-RES")
      (fields (field (name "PARTNO") "RC0402FR-0710KL"))
      (libsource (lib "eagle-import") (part "RESISTOR0402-RES"))
    )
    (comp (ref "R615")
      (value "10K")
      (footprint "eagle-import:0402-RES")
      (fields (field (name "PARTNO") "RC0402FR-0710KL"))
      (libsource (lib "eagle-import") (part "RESISTOR0402-RES"))
    )
    (comp (ref "R616")
      (value "25K5")
      (footprint "eagle-import:0402-RES")
      (fields (field (name "PARTNO") "RMCF0402FT25K5"))
      (libsource (lib "eagle-import") (part "RESISTOR0402-RES"))
    )
    (comp (ref "R617")
      (value "16K5")
      (footprint "eagle-import:0402-RES")
      (fields (field (name "PARTNO") "RMCF0402FT16K5"))
      (libsource (lib "eagle-import") (part "RESISTOR0402-RES"))
    )
    (comp (ref "R620")
      (value "1K8")
      (footprint "eagle-import:0402-RES")
      (fields (field (name "PARTNO") "RC1005F182CS"))
      (libsource (lib "eagle-import") (part "RESISTOR0402-RES"))
    )
    (comp (ref "R621")
      (value "10R")
      (footprint "eagle-import:0603-RES")
      (fields (field (name "PARTNO") "RC1608J100CS"))
      (libsource (lib "eagle-import") (part "RESISTOR0603-RES"))
    )
    (comp (ref "R635")
      (value "DNP/10K")
      (footprint "eagle-import:0402-RES")
      (fields (field (name "PARTNO") "RC0402FR-0710KL"))
      (libsource (lib "eagle-import") (part "RESISTOR0402-RES"))
    )
    (comp (ref "S601")
      (value "RESET")
      (footprint "eagle-import:EVQP7J01K")
      (fields (field (name "PARTNO") "EVQ-P7J01P"))
      (libsource (lib "eagle-import") (part "SWITCH-MOMENTARY-2"))
    )
    (comp (ref "U601")
      (value "BQ24315")
      (footprint "eagle-import:QFN8-DSG")
      (fields (field (name "PARTNO") "BQ24315DSGR"))
      (libsource (lib "eagle-import") (part "BQ24315"))
    )
    (comp (ref "U602")
      (value "BQ24315")
      (footprint "eagle-import:QFN8-DSG")
      (fields (field (name "PARTNO") "BQ24315DSGR"))
      (libsource (lib "eagle-import") (part "BQ24315"))
    )
    (comp (ref "U603")
      (value "MIC5332")
      (footprint "eagle-import:MLF-8-EPAD")
      (fields (field (name "PARTNO") "MIC5332-SSYMT"))
      (libsource (lib "eagle-import") (part "MIC5332"))
    )
    (comp (ref "C201")
      (value "0u1")
      (footprint "eagle-import:0402-CAP")
      (fields (field (name "PARTNO") "CC0402ZRY5V7BB104"))
      (libsource (lib "eagle-import") (part "CAP0402"))
    )
    (comp (ref "C202")
      (value "0u1")
      (footprint "eagle-import:0402-CAP")
      (fields (field (name "PARTNO") "CC0402ZRY5V7BB104"))
      (libsource (lib "eagle-import") (part "CAP0402"))
    )
    (comp (ref "D201")
      (value "PESD0402-140")
      (footprint "eagle-import:0402-TVS")
      (libsource (lib "eagle-import") (part "DIODE-TVS"))
    )
    (comp (ref "D202")
      (value "PESD0402-140")
      (footprint "eagle-import:0402-TVS")
      (libsource (lib "eagle-import") (part "DIODE-TVS"))
    )
    (comp (ref "D203")
      (value "PESD0402-140")
      (footprint "eagle-import:0402-TVS")
      (libsource (lib "eagle-import") (part "DIODE-TVS"))
    )
    (comp (ref "J201")
      (value "DF13C-6P-1.25V")
      (footprint "eagle-import:DF13C-6P-1.25V")
      (fields (field (name "PARTNO") "DF13C-6P-1.25V(20)"))
      (libsource (lib "eagle-import") (part "DF13-6P-1.25V"))
    )
    (comp (ref "J202")
      (value "DF13C-6P-1.25V")
      (footprint "eagle-import:DF13C-6P-1.25V")
      (fields (field (name "PARTNO") "DF13C-6P-1.25V(20)"))
      (libsource (lib "eagle-import") (part "DF13-6P-1.25V"))
    )
    (comp (ref "J203")
      (value "DF13C-6P-1.25V")
      (footprint "eagle-import:DF13C-6P-1.25V")
      (fields (field (name "PARTNO") "DF13C-6P-1.25V(20)"))
      (libsource (lib "eagle-import") (part "DF13-6P-1.25V"))
    )
    (comp (ref "J204")
      (value "DF13C-6P-1.25V")
      (footprint "eagle-import:DF13C-6P-1.25V")
      (fields (field (name "PARTNO") "DF13C-6P-1.25V(20)"))
      (libsource (lib "eagle-import") (part "DF13-6P-1.25V"))
    )
    (comp (ref "L201")
      (value "KNH16C104DA5TS")
      (footprint "eagle-import:KYOCERA-KNH16-DA")
      (libsource (lib "eagle-import") (part "KNH16C104DA5TS"))
    )
    (comp (ref "L202")
      (value "KNH16C104DA5TS")
      (footprint "eagle-import:KYOCERA-KNH16-DA")
      (libsource (lib "eagle-import") (part "KNH16C104DA5TS"))
    )
    (comp (ref "L203")
      (value "KNH16C104DA5TS")
      (footprint "eagle-import:KYOCERA-KNH16-DA")
      (libsource (lib "eagle-import") (part "KNH16C104DA5TS"))
    )
    (comp (ref "R201")
      (value "120R")
      (footprint "eagle-import:0402-RES")
      (fields (field (name "PARTNO") "RC0402FR-07120RL"))
      (libsource (lib "eagle-import") (part "RESISTOR0402-RES"))
    )
    (comp (ref "R202")
      (value "120R")
      (footprint "eagle-import:0402-RES")
      (fields (field (name "PARTNO") "RC0402FR-07120RL"))
      (libsource (lib "eagle-import") (part "RESISTOR0402-RES"))
    )
    (comp (ref "R203")
      (value "120R")
      (footprint "eagle-import:0402-RES")
      (fields (field (name "PARTNO") "RC0402FR-07120RL"))
      (libsource (lib "eagle-import") (part "RESISTOR0402-RES"))
    )
    (comp (ref "R204")
      (value "120R")
      (footprint "eagle-import:0402-RES")
      (fields (field (name "PARTNO") "RC0402FR-07120RL"))
      (libsource (lib "eagle-import") (part "RESISTOR0402-RES"))
    )
    (comp (ref "R205")
      (value "120R")
      (footprint "eagle-import:0402-RES")
      (fields (field (name "PARTNO") "RC0402FR-07120RL"))
      (libsource (lib "eagle-import") (part "RESISTOR0402-RES"))
    )
    (comp (ref "R206")
      (value "120R")
      (footprint "eagle-import:0402-RES")
      (fields (field (name "PARTNO") "RC0402FR-07120RL"))
      (libsource (lib "eagle-import") (part "RESISTOR0402-RES"))
    )
    (comp (ref "R207")
      (value "120R")
      (footprint "eagle-import:0402-RES")
      (fields (field (name "PARTNO") "RC0402FR-07120RL"))
      (libsource (lib "eagle-import") (part "RESISTOR0402-RES"))
    )
    (comp (ref "R208")
      (value "120R")
      (footprint "eagle-import:0402-RES")
      (fields (field (name "PARTNO") "RC0402FR-07120RL"))
      (libsource (lib "eagle-import") (part "RESISTOR0402-RES"))
    )
    (comp (ref "R209")
      (value "120R")
      (footprint "eagle-import:0402-RES")
      (fields (field (name "PARTNO") "RC0402FR-07120RL"))
      (libsource (lib "eagle-import") (part "RESISTOR0402-RES"))
    )
    (comp (ref "R210")
      (value "120R")
      (footprint "eagle-import:0402-RES")
      (fields (field (name "PARTNO") "RC0402FR-07120RL"))
      (libsource (lib "eagle-import") (part "RESISTOR0402-RES"))
    )
    (comp (ref "R211")
      (value "120R")
      (footprint "eagle-import:0402-RES")
      (fields (field (name "PARTNO") "RC0402FR-07120RL"))
      (libsource (lib "eagle-import") (part "RESISTOR0402-RES"))
    )
    (comp (ref "R212")
      (value "120R")
      (footprint "eagle-import:0402-RES")
      (fields (field (name "PARTNO") "RC0402FR-07120RL"))
      (libsource (lib "eagle-import") (part "RESISTOR0402-RES"))
    )
    (comp (ref "R213")
      (value "120R")
      (footprint "eagle-import:0402-RES")
      (fields (field (name "PARTNO") "RC0402FR-07120RL"))
      (libsource (lib "eagle-import") (part "RESISTOR0402-RES"))
    )
    (comp (ref "R214")
      (value "120R")
      (footprint "eagle-import:0402-RES")
      (fields (field (name "PARTNO") "RC0402FR-07120RL"))
      (libsource (lib "eagle-import") (part "RESISTOR0402-RES"))
    )
    (comp (ref "R215")
      (value "120R")
      (footprint "eagle-import:0402-RES")
      (fields (field (name "PARTNO") "RC0402FR-07120RL"))
      (libsource (lib "eagle-import") (part "RESISTOR0402-RES"))
    )
    (comp (ref "R216")
      (value "120R")
      (footprint "eagle-import:0402-RES")
      (fields (field (name "PARTNO") "RC0402FR-07120RL"))
      (libsource (lib "eagle-import") (part "RESISTOR0402-RES"))
    )
    (comp (ref "U201")
      (value "TXS0108QFN20")
      (footprint "eagle-import:QFN20-RGY")
      (fields (field (name "PARTNO") "TXS0108ERGYR"))
      (libsource (lib "eagle-import") (part "TXS0108QFN20"))
    )
    (comp (ref "U202")
      (value "TXS0108QFN20")
      (footprint "eagle-import:QFN20-RGY")
      (fields (field (name "PARTNO") "TXS0108ERGYR"))
      (libsource (lib "eagle-import") (part "TXS0108QFN20"))
    )
  )
  (nets
    (net (code "1") (name "ACCEL_DRDY") (class "Default")
      (node (ref "U101") (pin "90") (pinfunction "PB4_90") (pintype "bidirectional"))
      (node (ref "U504") (pin "11") (pinfunction "INT1_11") (pintype "bidirectional"))
      (node (ref "X503") (pin "3") (pinfunction "S_3") (pintype "passive"))
    )
    (net (code "2") (name "ALARM") (class "Default")
      (node (ref "R701") (pin "P$2") (pinfunction "2_P$2") (pintype "passive"))
      (node (ref "U101") (pin "77") (pinfunction "PA15_77") (pintype "bidirectional"))
    )
    (net (code "3") (name "BATT_CURRENT_SENS") (class "Default")
      (node (ref "R1101") (pin "P$1") (pinfunction "1_P$1") (pintype "passive"))
      (node (ref "U101") (pin "26") (pinfunction "PA3_26") (pintype "bidirectional"))
    )
    (net (code "4") (name "BATT_VOLTAGE_SENS") (class "Default")
      (node (ref "R1102") (pin "P$1") (pinfunction "1_P$1") (pintype "passive"))
      (node (ref "U101") (pin "25") (pinfunction "PA2_25") (pintype "bidirectional"))
    )
    (net (code "5") (name "CAN1_RX") (class "Default")
      (node (ref "U101") (pin "81") (pinfunction "PD0_81") (pintype "bidirectional"))
      (node (ref "U401") (pin "4") (pinfunction "DOUT_4") (pintype "output"))
    )
    (net (code "6") (name "CAN1_TX") (class "Default")
      (node (ref "U101") (pin "82") (pinfunction "PD1_82") (pintype "bidirectional"))
      (node (ref "U401") (pin "1") (pinfunction "DIN_1") (pintype "input"))
    )
    (net (code "7") (name "CAN2_RX") (class "Default")
      (node (ref "R216") (pin "P$1") (pinfunction "1_P$1") (pintype "passive"))
      (node (ref "U101") (pin "51") (pinfunction "PB12_51") (pintype "bidirectional"))
    )
    (net (code "8") (name "CAN2_TX") (class "Default")
      (node (ref "R215") (pin "P$1") (pinfunction "1_P$1") (pintype "passive"))
      (node (ref "U101") (pin "92") (pinfunction "PB6_92") (pintype "bidirectional"))
    )
    (net (code "9") (name "CAN_H") (class "Default")
      (node (ref "CAN_H") (pin "P$1") (pinfunction "P$1_P$1") (pintype "passive"))
      (node (ref "J405") (pin "2") (pinfunction "2_2") (pintype "passive"))
      (node (ref "R409") (pin "P$1") (pinfunction "1_P$1") (pintype "passive"))
      (node (ref "U401") (pin "7") (pinfunction "CANH_7") (pintype "bidirectional"))
    )
    (net (code "10") (name "CAN_L") (class "Default")
      (node (ref "CAN_L") (pin "P$1") (pinfunction "P$1_P$1") (pintype "passive"))
      (node (ref "J405") (pin "3") (pinfunction "3_3") (pintype "passive"))
      (node (ref "R409") (pin "P$2") (pinfunction "2_P$2") (pintype "passive"))
      (node (ref "U401") (pin "6") (pinfunction "CANL_6") (pintype "bidirectional"))
    )
    (net (code "11") (name "FMU-BOOT0") (class "Default")
      (node (ref "FMU-BOOT1101") (pin "P$1") (pinfunction "P$1_P$1") (pintype "passive"))
      (node (ref "R611") (pin "P$2") (pinfunction "2_P$2") (pintype "passive"))
      (node (ref "U101") (pin "94") (pinfunction "BOOT0_94") (pintype "input"))
    )
    (net (code "12") (name "FMU-CH1") (class "Default")
      (node (ref "U101") (pin "45") (pinfunction "PE14_45") (pintype "bidirectional"))
      (node (ref "U901") (pin "7") (pinfunction "A6_7") (pintype "bidirectional"))
    )
    (net (code "13") (name "FMU-CH2") (class "Default")
      (node (ref "U101") (pin "44") (pinfunction "PE13_44") (pintype "bidirectional"))
      (node (ref "U901") (pin "6") (pinfunction "A5_6") (pintype "bidirectional"))
    )
    (net (code "14") (name "FMU-CH3") (class "Default")
      (node (ref "U101") (pin "42") (pinfunction "PE11_42") (pintype "bidirectional"))
      (node (ref "U901") (pin "5") (pinfunction "A4_5") (pintype "bidirectional"))
    )
    (net (code "15") (name "FMU-CH4") (class "Default")
      (node (ref "U101") (pin "40") (pinfunction "PE9_40") (pintype "bidirectional"))
      (node (ref "U901") (pin "4") (pinfunction "A3_4") (pintype "bidirectional"))
    )
    (net (code "16") (name "FMU-CH5") (class "Default")
      (node (ref "U101") (pin "60") (pinfunction "PD13_60") (pintype "bidirectional"))
      (node (ref "U901") (pin "3") (pinfunction "A2_3") (pintype "bidirectional"))
    )
    (net (code "17") (name "FMU-CH6") (class "Default")
      (node (ref "U101") (pin "61") (pinfunction "PD14_61") (pintype "bidirectional"))
      (node (ref "U901") (pin "1") (pinfunction "A1_1") (pintype "bidirectional"))
    )
    (net (code "18") (name "FMU-I2C1_SCL") (class "Default")
      (node (ref "R401") (pin "P$1") (pinfunction "1_P$1") (pintype "passive"))
      (node (ref "R404") (pin "P$1") (pinfunction "1_P$1") (pintype "passive"))
      (node (ref "U101") (pin "95") (pinfunction "PB8_95") (pintype "bidirectional"))
    )
    (net (code "19") (name "FMU-I2C1_SDA") (class "Default")
      (node (ref "R402") (pin "P$1") (pinfunction "1_P$1") (pintype "passive"))
      (node (ref "R405") (pin "P$1") (pinfunction "1_P$1") (pintype "passive"))
      (node (ref "U101") (pin "96") (pinfunction "PB9_96") (pintype "bidirectional"))
    )
    (net (code "20") (name "FMU-I2C2_SCL") (class "Default")
      (node (ref "R306") (pin "P$1") (pinfunction "1_P$1") (pintype "passive"))
      (node (ref "U101") (pin "47") (pinfunction "PB10_47") (pintype "bidirectional"))
      (node (ref "U701") (pin "3") (pinfunction "SCL_3") (pintype "bidirectional"))
    )
    (net (code "21") (name "FMU-I2C2_SDA") (class "Default")
      (node (ref "R307") (pin "P$1") (pinfunction "1_P$1") (pintype "passive"))
      (node (ref "U101") (pin "48") (pinfunction "PB11_48") (pintype "bidirectional"))
      (node (ref "U701") (pin "2") (pinfunction "SDA_2") (pintype "bidirectional"))
    )
    (net (code "22") (name "FMU-SWCLK") (class "Default")
      (node (ref "JX301") (pin "4") (pinfunction "S_4") (pintype "passive"))
      (node (ref "U101") (pin "76") (pinfunction "PA14_76") (pintype "bidirectional"))
    )
    (net (code "23") (name "FMU-SWDIO") (class "Default")
      (node (ref "JX301") (pin "2") (pinfunction "S_2") (pintype "passive"))
      (node (ref "U101") (pin "72") (pinfunction "PA13_72") (pintype "bidirectional"))
    )
    (net (code "24") (name "FMU-SWO") (class "Default")
      (node (ref "JX301") (pin "6") (pinfunction "S_6") (pintype "passive"))
      (node (ref "U101") (pin "89") (pinfunction "PB3_89") (pintype "bidirectional"))
    )
    (net (code "25") (name "FMU-UART4_RX") (class "Default")
      (node (ref "U101") (pin "24") (pinfunction "PA1_24") (pintype "bidirectional"))
      (node (ref "U202") (pin "8") (pinfunction "A7_8") (pintype "bidirectional"))
    )
    (net (code "26") (name "FMU-UART4_TX") (class "Default")
      (node (ref "U101") (pin "23") (pinfunction "PA0_23") (pintype "bidirectional"))
      (node (ref "U202") (pin "9") (pinfunction "A8_9") (pintype "bidirectional"))
    )
    (net (code "27") (name "FMU-UART7_RX") (class "Default")
      (node (ref "U101") (pin "38") (pinfunction "PE7_38") (pintype "bidirectional"))
      (node (ref "U202") (pin "4") (pinfunction "A3_4") (pintype "bidirectional"))
    )
    (net (code "28") (name "FMU-UART7_TX") (class "Default")
      (node (ref "U101") (pin "39") (pinfunction "PE8_39") (pintype "bidirectional"))
      (node (ref "U202") (pin "5") (pinfunction "A4_5") (pintype "bidirectional"))
    )
    (net (code "29") (name "FMU-UART8_RX") (class "Default")
      (node (ref "U101") (pin "97") (pinfunction "PE0_97") (pintype "bidirectional"))
      (node (ref "U202") (pin "6") (pinfunction "A5_6") (pintype "bidirectional"))
    )
    (net (code "30") (name "FMU-UART8_TX") (class "Default")
      (node (ref "U101") (pin "98") (pinfunction "PE1_98") (pintype "bidirectional"))
      (node (ref "U202") (pin "7") (pinfunction "A6_7") (pintype "bidirectional"))
    )
    (net (code "31") (name "FMU-USART2_CTS") (class "Default")
      (node (ref "U101") (pin "84") (pinfunction "PD3_84") (pintype "bidirectional"))
      (node (ref "U201") (pin "9") (pinfunction "A8_9") (pintype "bidirectional"))
    )
    (net (code "32") (name "FMU-USART2_RTS") (class "Default")
      (node (ref "U101") (pin "85") (pinfunction "PD4_85") (pintype "bidirectional"))
      (node (ref "U201") (pin "8") (pinfunction "A7_8") (pintype "bidirectional"))
    )
    (net (code "33") (name "FMU-USART2_RX") (class "Default")
      (node (ref "U101") (pin "87") (pinfunction "PD6_87") (pintype "bidirectional"))
      (node (ref "U201") (pin "6") (pinfunction "A5_6") (pintype "bidirectional"))
    )
    (net (code "34") (name "FMU-USART2_TX") (class "Default")
      (node (ref "U101") (pin "86") (pinfunction "PD5_86") (pintype "bidirectional"))
      (node (ref "U201") (pin "7") (pinfunction "A6_7") (pintype "bidirectional"))
    )
    (net (code "35") (name "FMU-USART3_CTS") (class "Default")
      (node (ref "U101") (pin "58") (pinfunction "PD11_58") (pintype "bidirectional"))
      (node (ref "U201") (pin "3") (pinfunction "A2_3") (pintype "bidirectional"))
    )
    (net (code "36") (name "FMU-USART3_RTS") (class "Default")
      (node (ref "U101") (pin "59") (pinfunction "PD12_59") (pintype "bidirectional"))
      (node (ref "U201") (pin "1") (pinfunction "A1_1") (pintype "bidirectional"))
    )
    (net (code "37") (name "FMU-USART3_RX") (class "Default")
      (node (ref "U101") (pin "56") (pinfunction "PD9_56") (pintype "bidirectional"))
      (node (ref "U201") (pin "4") (pinfunction "A3_4") (pintype "bidirectional"))
    )
    (net (code "38") (name "FMU-USART3_TX") (class "Default")
      (node (ref "U101") (pin "55") (pinfunction "PD8_55") (pintype "bidirectional"))
      (node (ref "U201") (pin "5") (pinfunction "A4_5") (pintype "bidirectional"))
    )
    (net (code "39") (name "FMU-VDD_3V3") (class "Default")
      (node (ref "C101") (pin "P$1") (pinfunction "1_P$1") (pintype "passive"))
      (node (ref "C201") (pin "P$1") (pinfunction "1_P$1") (pintype "passive"))
      (node (ref "C202") (pin "P$1") (pinfunction "1_P$1") (pintype "passive"))
      (node (ref "C402") (pin "P$1") (pinfunction "1_P$1") (pintype "passive"))
      (node (ref "C603") (pin "P$1") (pinfunction "1_P$1") (pintype "passive"))
      (node (ref "C604") (pin "P$1") (pinfunction "1_P$1") (pintype "passive"))
      (node (ref "C606") (pin "P$1") (pinfunction "1_P$1") (pintype "passive"))
      (node (ref "C607") (pin "P$1") (pinfunction "1_P$1") (pintype "passive"))
      (node (ref "C608") (pin "P$1") (pinfunction "1_P$1") (pintype "passive"))
      (node (ref "C610") (pin "P$1") (pinfunction "1_P$1") (pintype "passive"))
      (node (ref "C612") (pin "P$1") (pinfunction "1_P$1") (pintype "passive"))
      (node (ref "C616") (pin "P$1") (pinfunction "1_P$1") (pintype "passive"))
      (node (ref "C701") (pin "P$1") (pinfunction "1_P$1") (pintype "passive"))
      (node (ref "C902") (pin "P$1") (pinfunction "1_P$1") (pintype "passive"))
      (node (ref "D602") (pin "A") (pinfunction "A_A") (pintype "passive"))
      (node (ref "JX301") (pin "1") (pinfunction "S_1") (pintype "passive"))
      (node (ref "R301") (pin "P$2") (pinfunction "2_P$2") (pintype "passive"))
      (node (ref "R302") (pin "P$2") (pinfunction "2_P$2") (pintype "passive"))
      (node (ref "R303") (pin "P$2") (pinfunction "2_P$2") (pintype "passive"))
      (node (ref "R304") (pin "P$2") (pinfunction "2_P$2") (pintype "passive"))
      (node (ref "R305") (pin "P$2") (pinfunction "2_P$2") (pintype "passive"))
      (node (ref "R306") (pin "P$2") (pinfunction "2_P$2") (pintype "passive"))
      (node (ref "R307") (pin "P$2") (pinfunction "2_P$2") (pintype "passive"))
      (node (ref "R401") (pin "P$2") (pinfunction "2_P$2") (pintype "passive"))
      (node (ref "R402") (pin "P$2") (pinfunction "2_P$2") (pintype "passive"))
      (node (ref "R602") (pin "P$2") (pinfunction "2_P$2") (pintype "passive"))
      (node (ref "R604") (pin "P$2") (pinfunction "2_P$2") (pintype "passive"))
      (node (ref "U101") (pin "100") (pinfunction "VDD_100") (pintype "power_in"))
      (node (ref "U101") (pin "11") (pinfunction "VDD_11") (pintype "power_in"))
      (node (ref "U101") (pin "19") (pinfunction "VDD_19") (pintype "power_in"))
      (node (ref "U101") (pin "21") (pinfunction "VREF+_21") (pintype "input"))
      (node (ref "U101") (pin "22") (pinfunction "VDDA_22") (pintype "power_in"))
      (node (ref "U101") (pin "28") (pinfunction "VDD_28") (pintype "power_in"))
      (node (ref "U101") (pin "50") (pinfunction "VDD_50") (pintype "power_in"))
      (node (ref "U101") (pin "75") (pinfunction "VDD_75") (pintype "power_in"))
      (node (ref "U102") (pin "3") (pinfunction "~{W}_3") (pintype "bidirectional"))
      (node (ref "U102") (pin "7") (pinfunction "~{HOLD}_7") (pintype "bidirectional"))
      (node (ref "U102") (pin "8") (pinfunction "VDD_8") (pintype "bidirectional"))
      (node (ref "U201") (pin "10") (pinfunction "OE_10") (pintype "input"))
      (node (ref "U201") (pin "19") (pinfunction "VCCB_19") (pintype "input"))
      (node (ref "U201") (pin "2") (pinfunction "VCCA_2") (pintype "input"))
      (node (ref "U202") (pin "10") (pinfunction "OE_10") (pintype "input"))
      (node (ref "U202") (pin "19") (pinfunction "VCCB_19") (pintype "input"))
      (node (ref "U202") (pin "2") (pinfunction "VCCA_2") (pintype "input"))
      (node (ref "U301") (pin "4") (pinfunction "VCC_4") (pintype "passive"))
      (node (ref "U401") (pin "3") (pinfunction "VCC_3") (pintype "input"))
      (node (ref "U603") (pin "7") (pinfunction "VOUT2_7") (pintype "bidirectional"))
      (node (ref "U701") (pin "1") (pinfunction "~{SHDN}_1") (pintype "input"))
      (node (ref "U701") (pin "10") (pinfunction "VIN_10") (pintype "power_in"))
      (node (ref "U901") (pin "10") (pinfunction "OE_10") (pintype "input"))
      (node (ref "U901") (pin "19") (pinfunction "VCCB_19") (pintype "input"))
      (node (ref "U901") (pin "2") (pinfunction "VCCA_2") (pintype "input"))
      (node (ref "VDD_3V1101") (pin "P$1") (pinfunction "P$1_P$1") (pintype "passive"))
    )
    (net (code "40") (name "FMU-~{RESET}") (class "Default")
      (node (ref "C609") (pin "P$2") (pinfunction "2_P$2") (pintype "passive"))
      (node (ref "R635") (pin "P$1") (pinfunction "1_P$1") (pintype "passive"))
      (node (ref "S601") (pin "A1") (pinfunction "1_A1") (pintype "passive"))
      (node (ref "U101") (pin "14") (pinfunction "NRST_14") (pintype "input"))
      (node (ref "U603") (pin "3") (pinfunction "POR2_3") (pintype "bidirectional"))
      (node (ref "U701") (pin "4") (pinfunction "~{RESET}_4") (pintype "input"))
    )
    (net (code "41") (name "FMU_AUX_ADC1") (class "Default")
      (node (ref "R408") (pin "P$1") (pinfunction "1_P$1") (pintype "passive"))
      (node (ref "U101") (pin "18") (pinfunction "PC3_18") (pintype "bidirectional"))
    )
    (net (code "42") (name "FMU_AUX_ADC2") (class "Default")
      (node (ref "R407") (pin "P$1") (pinfunction "1_P$1") (pintype "passive"))
      (node (ref "U101") (pin "33") (pinfunction "PC4_33") (pintype "bidirectional"))
    )
    (net (code "43") (name "FRAM_MISO") (class "Default")
      (node (ref "U101") (pin "53") (pinfunction "PB14_53") (pintype "bidirectional"))
      (node (ref "U102") (pin "2") (pinfunction "Q_2") (pintype "bidirectional"))
    )
    (net (code "44") (name "FRAM_MOSI") (class "Default")
      (node (ref "U101") (pin "54") (pinfunction "PB15_54") (pintype "bidirectional"))
      (node (ref "U102") (pin "5") (pinfunction "D_5") (pintype "bidirectional"))
    )
    (net (code "45") (name "FRAM_SCK") (class "Default")
      (node (ref "U101") (pin "52") (pinfunction "PB13_52") (pintype "bidirectional"))
      (node (ref "U102") (pin "6") (pinfunction "C_6") (pintype "bidirectional"))
    )
    (net (code "46") (name "GND") (class "Default")
      (node (ref "B601") (pin "2") (pinfunction "NEG_2") (pintype "bidirectional"))
      (node (ref "C1001") (pin "P$2") (pinfunction "2_P$2") (pintype "passive"))
      (node (ref "C1002") (pin "P$2") (pinfunction "2_P$2") (pintype "passive"))
      (node (ref "C1003") (pin "P$2") (pinfunction "2_P$2") (pintype "passive"))
      (node (ref "C1004") (pin "P$2") (pinfunction "2_P$2") (pintype "passive"))
      (node (ref "C1005") (pin "P$2") (pinfunction "2_P$2") (pintype "passive"))
      (node (ref "C1008") (pin "P$2") (pinfunction "2_P$2") (pintype "passive"))
      (node (ref "C101") (pin "P$2") (pinfunction "2_P$2") (pintype "passive"))
      (node (ref "C102") (pin "P$2") (pinfunction "2_P$2") (pintype "passive"))
      (node (ref "C103") (pin "P$1") (pinfunction "1_P$1") (pintype "passive"))
      (node (ref "C1101") (pin "P$2") (pinfunction "2_P$2") (pintype "passive"))
      (node (ref "C1102") (pin "P$2") (pinfunction "2_P$2") (pintype "passive"))
      (node (ref "C1103") (pin "P$2") (pinfunction "2_P$2") (pintype "passive"))
      (node (ref "C1104") (pin "P$2") (pinfunction "2_P$2") (pintype "passive"))
      (node (ref "C1105") (pin "P$2") (pinfunction "2_P$2") (pintype "passive"))
      (node (ref "C1106") (pin "P$2") (pinfunction "2_P$2") (pintype "passive"))
      (node (ref "C1107") (pin "P$2") (pinfunction "2_P$2") (pintype "passive"))
      (node (ref "C1108") (pin "P$2") (pinfunction "2_P$2") (pintype "passive"))
      (node (ref "C1109") (pin "P$2") (pinfunction "2_P$2") (pintype "passive"))
      (node (ref "C1110") (pin "P$2") (pinfunction "2_P$2") (pintype "passive"))
      (node (ref "C201") (pin "P$2") (pinfunction "2_P$2") (pintype "passive"))
      (node (ref "C202") (pin "P$2") (pinfunction "2_P$2") (pintype "passive"))
      (node (ref "C401") (pin "P$2") (pinfunction "2_P$2") (pintype "passive"))
      (node (ref "C402") (pin "P$2") (pinfunction "2_P$2") (pintype "passive"))
      (node (ref "C501") (pin "P$2") (pinfunction "2_P$2") (pintype "passive"))
      (node (ref "C502") (pin "P$2") (pinfunction "2_P$2") (pintype "passive"))
      (node (ref "C503") (pin "P$2") (pinfunction "2_P$2") (pintype "passive"))
      (node (ref "C504") (pin "P$2") (pinfunction "2_P$2") (pintype "passive"))
      (node (ref "C505") (pin "P$2") (pinfunction "2_P$2") (pintype "passive"))
      (node (ref "C506") (pin "P$2") (pinfunction "2_P$2") (pintype "passive"))
      (node (ref "C507") (pin "P$2") (pinfunction "2_P$2") (pintype "passive"))
      (node (ref "C508") (pin "P$2") (pinfunction "2_P$2") (pintype "passive"))
      (node (ref "C509") (pin "P$2") (pinfunction "2_P$2") (pintype "passive"))
      (node (ref "C511") (pin "P$2") (pinfunction "2_P$2") (pintype "passive"))
      (node (ref "C512") (pin "P$2") (pinfunction "2_P$2") (pintype "passive"))
      (node (ref "C513") (pin "P$2") (pinfunction "2_P$2") (pintype "passive"))
      (node (ref "C514") (pin "P$2") (pinfunction "2_P$2") (pintype "passive"))
      (node (ref "C515") (pin "P$2") (pinfunction "2_P$2") (pintype "passive"))
      (node (ref "C601") (pin "P$2") (pinfunction "2_P$2") (pintype "passive"))
      (node (ref "C602") (pin "P$1") (pinfunction "1_P$1") (pintype "passive"))
      (node (ref "C603") (pin "P$2") (pinfunction "2_P$2") (pintype "passive"))
      (node (ref "C604") (pin "P$2") (pinfunction "2_P$2") (pintype "passive"))
      (node (ref "C605") (pin "P$2") (pinfunction "2_P$2") (pintype "passive"))
      (node (ref "C606") (pin "P$2") (pinfunction "2_P$2") (pintype "passive"))
      (node (ref "C607") (pin "P$2") (pinfunction "2_P$2") (pintype "passive"))
      (node (ref "C608") (pin "P$2") (pinfunction "2_P$2") (pintype "passive"))
      (node (ref "C609") (pin "P$1") (pinfunction "1_P$1") (pintype "passive"))
      (node (ref "C610") (pin "P$2") (pinfunction "2_P$2") (pintype "passive"))
      (node (ref "C611") (pin "P$2") (pinfunction "2_P$2") (pintype "passive"))
      (node (ref "C612") (pin "P$2") (pinfunction "2_P$2") (pintype "passive"))
      (node (ref "C613") (pin "P$2") (pinfunction "2_P$2") (pintype "passive"))
      (node (ref "C614") (pin "P$2") (pinfunction "2_P$2") (pintype "passive"))
      (node (ref "C615") (pin "P$2") (pinfunction "2_P$2") (pintype "passive"))
      (node (ref "C616") (pin "P$2") (pinfunction "2_P$2") (pintype "passive"))
      (node (ref "C617") (pin "P$2") (pinfunction "2_P$2") (pintype "passive"))
      (node (ref "C618") (pin "P$2") (pinfunction "2_P$2") (pintype "passive"))
      (node (ref "C701") (pin "P$2") (pinfunction "2_P$2") (pintype "passive"))
      (node (ref "C702") (pin "P$2") (pinfunction "2_P$2") (pintype "passive"))
      (node (ref "C703") (pin "P$2") (pinfunction "2_P$2") (pintype "passive"))
      (node (ref "C704") (pin "P$2") (pinfunction "2_P$2") (pintype "passive"))
      (node (ref "C801") (pin "P$1") (pinfunction "1_P$1") (pintype "passive"))
      (node (ref "C802") (pin "P$2") (pinfunction "2_P$2") (pintype "passive"))
      (node (ref "C803") (pin "P$2") (pinfunction "2_P$2") (pintype "passive"))
      (node (ref "C804") (pin "P$2") (pinfunction "2_P$2") (pintype "passive"))
      (node (ref "C805") (pin "P$2") (pinfunction "2_P$2") (pintype "passive"))
      (node (ref "C806") (pin "P$1") (pinfunction "1_P$1") (pintype "passive"))
      (node (ref "C901") (pin "P$2") (pinfunction "2_P$2") (pintype "passive"))
      (node (ref "C902") (pin "P$2") (pinfunction "2_P$2") (pintype "passive"))
      (node (ref "C903") (pin "P$2") (pinfunction "2_P$2") (pintype "passive"))
      (node (ref "D201") (pin "A") (pinfunction "A_A") (pintype "passive"))
      (node (ref "D202") (pin "A") (pinfunction "A_A") (pintype "passive"))
      (node (ref "D203") (pin "A") (pinfunction "A_A") (pintype "passive"))
      (node (ref "D401") (pin "A") (pinfunction "A_A") (pintype "passive"))
      (node (ref "D402") (pin "A") (pinfunction "A_A") (pintype "passive"))
      (node (ref "D403") (pin "A") (pinfunction "A_A") (pintype "passive"))
      (node (ref "D404") (pin "A") (pinfunction "A_A") (pintype "passive"))
      (node (ref "D701") (pin "A") (pinfunction "A_A") (pintype "passive"))
      (node (ref "D801") (pin "A") (pinfunction "A_A") (pintype "passive"))
      (node (ref "D901") (pin "A") (pinfunction "A_A") (pintype "passive"))
      (node (ref "D902") (pin "A") (pinfunction "A_A") (pintype "passive"))
      (node (ref "D903") (pin "A") (pinfunction "A_A") (pintype "passive"))
      (node (ref "GND") (pin "P$1") (pinfunction "P$1_P$1") (pintype "passive"))
      (node (ref "GND.") (pin "P$1") (pinfunction "P$1_P$1") (pintype "passive"))
      (node (ref "J201") (pin "6") (pinfunction "6_6") (pintype "passive"))
      (node (ref "J202") (pin "6") (pinfunction "6_6") (pintype "passive"))
      (node (ref "J203") (pin "6") (pinfunction "6_6") (pintype "passive"))
      (node (ref "J204") (pin "6") (pinfunction "6_6") (pintype "passive"))
      (node (ref "J301") (pin "GND") (pinfunction "5_GND") (pintype "power_in"))
      (node (ref "J301") (pin "GND1") (pinfunction "GND1_GND1") (pintype "bidirectional"))
      (node (ref "J301") (pin "GND2") (pinfunction "GND2_GND2") (pintype "bidirectional"))
      (node (ref "J301") (pin "GND3") (pinfunction "GND3_GND3") (pintype "bidirectional"))
      (node (ref "J301") (pin "GND4") (pinfunction "GND4_GND4") (pintype "bidirectional"))
      (node (ref "J302") (pin "4") (pinfunction "4_4") (pintype "passive"))
      (node (ref "J401") (pin "4") (pinfunction "4_4") (pintype "passive"))
      (node (ref "J402") (pin "3") (pinfunction "3_3") (pintype "passive"))
      (node (ref "J403") (pin "7") (pinfunction "7_7") (pintype "passive"))
      (node (ref "J404") (pin "3") (pinfunction "3_3") (pintype "passive"))
      (node (ref "J404") (pin "5") (pinfunction "5_5") (pintype "passive"))
      (node (ref "J405") (pin "4") (pinfunction "4_4") (pintype "passive"))
      (node (ref "J601") (pin "5") (pinfunction "5_5") (pintype "passive"))
      (node (ref "J601") (pin "6") (pinfunction "6_6") (pintype "passive"))
      (node (ref "J701") (pin "2") (pinfunction "2_2") (pintype "passive"))
      (node (ref "J801") (pin "P$2") (pinfunction "P$2_P$2") (pintype "bidirectional"))
      (node (ref "J901") (pin "12") (pinfunction "S_12") (pintype "passive"))
      (node (ref "J901") (pin "15") (pinfunction "S_15") (pintype "passive"))
      (node (ref "J901") (pin "18") (pinfunction "S_18") (pintype "passive"))
      (node (ref "J901") (pin "21") (pinfunction "S_21") (pintype "passive"))
      (node (ref "J901") (pin "24") (pinfunction "S_24") (pintype "passive"))
      (node (ref "J901") (pin "27") (pinfunction "S_27") (pintype "passive"))
      (node (ref "J901") (pin "3") (pinfunction "S_3") (pintype "passive"))
      (node (ref "J901") (pin "30") (pinfunction "S_30") (pintype "passive"))
      (node (ref "J901") (pin "33") (pinfunction "S_33") (pintype "passive"))
      (node (ref "J901") (pin "36") (pinfunction "S_36") (pintype "passive"))
      (node (ref "J901") (pin "39") (pinfunction "S_39") (pintype "passive"))
      (node (ref "J901") (pin "42") (pinfunction "S_42") (pintype "passive"))
      (node (ref "J901") (pin "45") (pinfunction "S_45") (pintype "passive"))
      (node (ref "J901") (pin "48") (pinfunction "S_48") (pintype "passive"))
      (node (ref "J901") (pin "6") (pinfunction "S_6") (pintype "passive"))
      (node (ref "J901") (pin "9") (pinfunction "S_9") (pintype "passive"))
      (node (ref "JX301") (pin "3") (pinfunction "S_3") (pintype "passive"))
      (node (ref "JX301") (pin "5") (pinfunction "S_5") (pintype "passive"))
      (node (ref "JX301") (pin "9") (pinfunction "S_9") (pintype "passive"))
      (node (ref "JX801") (pin "3") (pinfunction "GND_3") (pintype "bidirectional"))
      (node (ref "JX802") (pin "3") (pinfunction "S_3") (pintype "passive"))
      (node (ref "JX802") (pin "5") (pinfunction "S_5") (pintype "passive"))
      (node (ref "JX802") (pin "9") (pinfunction "S_9") (pintype "passive"))
      (node (ref "L1101") (pin "P$3") (pinfunction "P$3_P$3") (pintype "bidirectional"))
      (node (ref "L1101") (pin "P$4") (pinfunction "P$3_P$4") (pintype "bidirectional"))
      (node (ref "L1101") (pin "P$5") (pinfunction "P$3_P$5") (pintype "bidirectional"))
      (node (ref "L1102") (pin "P$3") (pinfunction "P$3_P$3") (pintype "bidirectional"))
      (node (ref "L1102") (pin "P$4") (pinfunction "P$3_P$4") (pintype "bidirectional"))
      (node (ref "L1102") (pin "P$5") (pinfunction "P$3_P$5") (pintype "bidirectional"))
      (node (ref "L201") (pin "P$3") (pinfunction "P$3_P$3") (pintype "bidirectional"))
      (node (ref "L201") (pin "P$4") (pinfunction "P$3_P$4") (pintype "bidirectional"))
      (node (ref "L201") (pin "P$5") (pinfunction "P$3_P$5") (pintype "bidirectional"))
      (node (ref "L202") (pin "P$3") (pinfunction "P$3_P$3") (pintype "bidirectional"))
      (node (ref "L202") (pin "P$4") (pinfunction "P$3_P$4") (pintype "bidirectional"))
      (node (ref "L202") (pin "P$5") (pinfunction "P$3_P$5") (pintype "bidirectional"))
      (node (ref "L203") (pin "P$3") (pinfunction "P$3_P$3") (pintype "bidirectional"))
      (node (ref "L203") (pin "P$4") (pinfunction "P$3_P$4") (pintype "bidirectional"))
      (node (ref "L203") (pin "P$5") (pinfunction "P$3_P$5") (pintype "bidirectional"))
      (node (ref "L401") (pin "P$3") (pinfunction "P$3_P$3") (pintype "bidirectional"))
      (node (ref "L401") (pin "P$4") (pinfunction "P$3_P$4") (pintype "bidirectional"))
      (node (ref "L401") (pin "P$5") (pinfunction "P$3_P$5") (pintype "bidirectional"))
      (node (ref "L402") (pin "P$3") (pinfunction "P$3_P$3") (pintype "bidirectional"))
      (node (ref "L402") (pin "P$4") (pinfunction "P$3_P$4") (pintype "bidirectional"))
      (node (ref "L402") (pin "P$5") (pinfunction "P$3_P$5") (pintype "bidirectional"))
      (node (ref "L403") (pin "P$3") (pinfunction "P$3_P$3") (pintype "bidirectional"))
      (node (ref "L403") (pin "P$4") (pinfunction "P$3_P$4") (pintype "bidirectional"))
      (node (ref "L403") (pin "P$5") (pinfunction "P$3_P$5") (pintype "bidirectional"))
      (node (ref "L404") (pin "P$3") (pinfunction "P$3_P$3") (pintype "bidirectional"))
      (node (ref "L404") (pin "P$4") (pinfunction "P$3_P$4") (pintype "bidirectional"))
      (node (ref "L404") (pin "P$5") (pinfunction "P$3_P$5") (pintype "bidirectional"))
      (node (ref "L603") (pin "P$3") (pinfunction "P$3_P$3") (pintype "bidirectional"))
      (node (ref "L603") (pin "P$4") (pinfunction "P$3_P$4") (pintype "bidirectional"))
      (node (ref "L603") (pin "P$5") (pinfunction "P$3_P$5") (pintype "bidirectional"))
      (node (ref "L901") (pin "P$3") (pinfunction "P$3_P$3") (pintype "bidirectional"))
      (node (ref "L901") (pin "P$4") (pinfunction "P$3_P$4") (pintype "bidirectional"))
      (node (ref "L901") (pin "P$5") (pinfunction "P$3_P$5") (pintype "bidirectional"))
      (node (ref "R1001") (pin "P$1") (pinfunction "1_P$1") (pintype "passive"))
      (node (ref "R1002") (pin "P$1") (pinfunction "1_P$1") (pintype "passive"))
      (node (ref "R102") (pin "P$2") (pinfunction "2_P$2") (pintype "passive"))
      (node (ref "R1103") (pin "P$2") (pinfunction "2_P$2") (pintype "passive"))
      (node (ref "R1104") (pin "P$2") (pinfunction "2_P$2") (pintype "passive"))
      (node (ref "R1107") (pin "P$2") (pinfunction "2_P$2") (pintype "passive"))
      (node (ref "R1111") (pin "P$2") (pinfunction "2_P$2") (pintype "passive"))
      (node (ref "R1114") (pin "P$2") (pinfunction "2_P$2") (pintype "passive"))
      (node (ref "R1115") (pin "P$1") (pinfunction "1_P$1") (pintype "passive"))
      (node (ref "R403") (pin "P$1") (pinfunction "1_P$1") (pintype "passive"))
      (node (ref "R610") (pin "P$2") (pinfunction "2_P$2") (pintype "passive"))
      (node (ref "R611") (pin "P$1") (pinfunction "1_P$1") (pintype "passive"))
      (node (ref "R615") (pin "P$2") (pinfunction "2_P$2") (pintype "passive"))
      (node (ref "R616") (pin "P$2") (pinfunction "2_P$2") (pintype "passive"))
      (node (ref "R617") (pin "P$2") (pinfunction "2_P$2") (pintype "passive"))
      (node (ref "R621") (pin "1") (pinfunction "1_1") (pintype "passive"))
      (node (ref "R702") (pin "P$2") (pinfunction "2_P$2") (pintype "passive"))
      (node (ref "R704") (pin "P$1") (pinfunction "1_P$1") (pintype "passive"))
      (node (ref "R706") (pin "P$2") (pinfunction "2_P$2") (pintype "passive"))
      (node (ref "R708") (pin "P$1") (pinfunction "1_P$1") (pintype "passive"))
      (node (ref "R711") (pin "P$1") (pinfunction "1_P$1") (pintype "passive"))
      (node (ref "R713") (pin "P$2") (pinfunction "2_P$2") (pintype "passive"))
      (node (ref "R801") (pin "P$2") (pinfunction "2_P$2") (pintype "passive"))
      (node (ref "R802") (pin "P$2") (pinfunction "2_P$2") (pintype "passive"))
      (node (ref "R919") (pin "P$1") (pinfunction "1_P$1") (pintype "passive"))
      (node (ref "S601") (pin "B3") (pinfunction "2_B3") (pintype "passive"))
      (node (ref "S801") (pin "B3") (pinfunction "2_B3") (pintype "passive"))
      (node (ref "U1001") (pin "2") (pinfunction "VSS_2") (pintype "bidirectional"))
      (node (ref "U1001") (pin "5") (pinfunction "~{CE}_5") (pintype "bidirectional"))
      (node (ref "U1001") (pin "6") (pinfunction "VBAT_6") (pintype "bidirectional"))
      (node (ref "U1001") (pin "GND") (pinfunction "VSS_GND") (pintype "bidirectional"))
      (node (ref "U1001") (pin "P$2") (pinfunction "VSS_P$2") (pintype "bidirectional"))
      (node (ref "U1001") (pin "P$3") (pinfunction "VSS_P$3") (pintype "bidirectional"))
      (node (ref "U1002") (pin "2") (pinfunction "GND_2") (pintype "bidirectional"))
      (node (ref "U1002") (pin "GND") (pinfunction "GND_GND") (pintype "bidirectional"))
      (node (ref "U101") (pin "10") (pinfunction "VSS_10") (pintype "power_in"))
      (node (ref "U101") (pin "20") (pinfunction "VSSA_20") (pintype "power_in"))
      (node (ref "U101") (pin "27") (pinfunction "VSS_27") (pintype "power_in"))
      (node (ref "U101") (pin "74") (pinfunction "VSS_74") (pintype "power_in"))
      (node (ref "U101") (pin "99") (pinfunction "VSS_99") (pintype "power_in"))
      (node (ref "U102") (pin "4") (pinfunction "VSS_4") (pintype "bidirectional"))
      (node (ref "U1101") (pin "P$10") (pinfunction "GND_P$10") (pintype "bidirectional"))
      (node (ref "U1101") (pin "P$25") (pinfunction "GND_P$25") (pintype "bidirectional"))
      (node (ref "U201") (pin "11") (pinfunction "GND_11") (pintype "power_in"))
      (node (ref "U202") (pin "11") (pinfunction "GND_11") (pintype "power_in"))
      (node (ref "U301") (pin "6") (pinfunction "GND_6") (pintype "power_in"))
      (node (ref "U302") (pin "2") (pinfunction "GND_2") (pintype "bidirectional"))
      (node (ref "U401") (pin "2") (pinfunction "GND_2") (pintype "power_in"))
      (node (ref "U401") (pin "5") (pinfunction "SHDN_5") (pintype "input"))
      (node (ref "U401") (pin "8") (pinfunction "RS_8") (pintype "input"))
      (node (ref "U501") (pin "10") (pinfunction "RES_P10_GND_10") (pintype "bidirectional"))
      (node (ref "U501") (pin "11") (pinfunction "RES_P11_GND_11") (pintype "bidirectional"))
      (node (ref "U501") (pin "12") (pinfunction "RES_P12_GND_12") (pintype "bidirectional"))
      (node (ref "U501") (pin "13") (pinfunction "GND_13") (pintype "bidirectional"))
      (node (ref "U501") (pin "8") (pinfunction "RES_P8_GND_8") (pintype "bidirectional"))
      (node (ref "U501") (pin "9") (pinfunction "RES_P9_GND_9") (pintype "bidirectional"))
      (node (ref "U502") (pin "10") (pinfunction "GND_10") (pintype "bidirectional"))
      (node (ref "U502") (pin "11") (pinfunction "GND_11") (pintype "bidirectional"))
      (node (ref "U502") (pin "12") (pinfunction "GND_12") (pintype "bidirectional"))
      (node (ref "U502") (pin "13") (pinfunction "GND_13") (pintype "bidirectional"))
      (node (ref "U502") (pin "9") (pinfunction "GND_9") (pintype "bidirectional"))
      (node (ref "U504") (pin "10") (pinfunction "RSRV_10") (pintype "bidirectional"))
      (node (ref "U504") (pin "12") (pinfunction "GND_12") (pintype "bidirectional"))
      (node (ref "U504") (pin "13") (pinfunction "GND_13") (pintype "bidirectional"))
      (node (ref "U504") (pin "16") (pinfunction "GND_16") (pintype "bidirectional"))
      (node (ref "U504") (pin "5") (pinfunction "GND_5") (pintype "bidirectional"))
      (node (ref "U505") (pin "1") (pinfunction "CLKIN_1") (pintype "bidirectional"))
      (node (ref "U505") (pin "18") (pinfunction "GND_18") (pintype "bidirectional"))
      (node (ref "U506") (pin "2") (pinfunction "PS_2") (pintype "bidirectional"))
      (node (ref "U506") (pin "3") (pinfunction "GND_3") (pintype "bidirectional"))
      (node (ref "U601") (pin "2") (pinfunction "VSS_2") (pintype "bidirectional"))
      (node (ref "U601") (pin "6") (pinfunction "VBAT_6") (pintype "bidirectional"))
      (node (ref "U601") (pin "GND") (pinfunction "VSS_GND") (pintype "bidirectional"))
      (node (ref "U601") (pin "P$2") (pinfunction "VSS_P$2") (pintype "bidirectional"))
      (node (ref "U601") (pin "P$3") (pinfunction "VSS_P$3") (pintype "bidirectional"))
      (node (ref "U602") (pin "2") (pinfunction "VSS_2") (pintype "bidirectional"))
      (node (ref "U602") (pin "6") (pinfunction "VBAT_6") (pintype "bidirectional"))
      (node (ref "U602") (pin "GND") (pinfunction "VSS_GND") (pintype "bidirectional"))
      (node (ref "U602") (pin "P$2") (pinfunction "VSS_P$2") (pintype "bidirectional"))
      (node (ref "U602") (pin "P$3") (pinfunction "VSS_P$3") (pintype "bidirectional"))
      (node (ref "U603") (pin "2") (pinfunction "GND_2") (pintype "bidirectional"))
      (node (ref "U603") (pin "GND") (pinfunction "GND_GND") (pintype "bidirectional"))
      (node (ref "U701") (pin "5") (pinfunction "GND_5") (pintype "power_in"))
      (node (ref "U702") (pin "4") (pinfunction "GND_4") (pintype "power_in"))
      (node (ref "U801") (pin "23") (pinfunction "VSS_1_23") (pintype "power_in"))
      (node (ref "U801") (pin "35") (pinfunction "VSS_2_35") (pintype "power_in"))
      (node (ref "U801") (pin "47") (pinfunction "VSS_3_47") (pintype "power_in"))
      (node (ref "U801") (pin "8") (pinfunction "VSSA_8") (pintype "power_in"))
      (node (ref "U901") (pin "11") (pinfunction "GND_11") (pintype "power_in"))
      (node (ref "U902") (pin "11") (pinfunction "GND_11") (pintype "power_in"))
      (node (ref "U903") (pin "1") (pinfunction "~{1OE}_1") (pintype "input"))
      (node (ref "U903") (pin "4") (pinfunction "GND_4") (pintype "power_in"))
      (node (ref "X101") (pin "2") (pinfunction "NC_2_2") (pintype "power_in"))
      (node (ref "X101") (pin "4") (pinfunction "NC_4_4") (pintype "power_in"))
      (node (ref "X503") (pin "2") (pinfunction "S_2") (pintype "passive"))
      (node (ref "X801") (pin "2") (pinfunction "NC_2_2") (pintype "power_in"))
      (node (ref "X801") (pin "4") (pinfunction "NC_4_4") (pintype "power_in"))
    )
    (net (code "47") (name "GPIO_EXT_1") (class "Default")
      (node (ref "J403") (pin "6") (pinfunction "6_6") (pintype "passive"))
      (node (ref "U101") (pin "8") (pinfunction "PC14_8") (pintype "bidirectional"))
    )
    (net (code "48") (name "GYRO_DRDY") (class "Default")
      (node (ref "U101") (pin "35") (pinfunction "PB0_35") (pintype "bidirectional"))
      (node (ref "U501") (pin "6") (pinfunction "DRDY/INT2_6") (pintype "output"))
      (node (ref "U502") (pin "6") (pinfunction "DRDY/INT2_6") (pintype "bidirectional"))
      (node (ref "X503") (pin "5") (pinfunction "S_5") (pintype "passive"))
    )
    (net (code "49") (name "IO-BOOT0") (class "Default")
      (node (ref "IO-BOOT1101") (pin "P$1") (pinfunction "P$1_P$1") (pintype "passive"))
      (node (ref "R801") (pin "P$1") (pinfunction "1_P$1") (pintype "passive"))
      (node (ref "U801") (pin "44") (pinfunction "BOOT0_44") (pintype "input"))
    )
    (net (code "50") (name "IO-CH1") (class "Default")
      (node (ref "U801") (pin "10") (pinfunction "PA0_10") (pintype "bidirectional"))
      (node (ref "U902") (pin "9") (pinfunction "A8_9") (pintype "bidirectional"))
    )
    (net (code "51") (name "IO-CH2") (class "Default")
      (node (ref "U801") (pin "11") (pinfunction "PA1_11") (pintype "bidirectional"))
      (node (ref "U902") (pin "8") (pinfunction "A7_8") (pintype "bidirectional"))
    )
    (net (code "52") (name "IO-CH3") (class "Default")
      (node (ref "U801") (pin "45") (pinfunction "PB8_45") (pintype "bidirectional"))
      (node (ref "U902") (pin "7") (pinfunction "A6_7") (pintype "bidirectional"))
    )
    (net (code "53") (name "IO-CH4") (class "Default")
      (node (ref "U801") (pin "46") (pinfunction "PB9_46") (pintype "bidirectional"))
      (node (ref "U902") (pin "6") (pinfunction "A5_6") (pintype "bidirectional"))
    )
    (net (code "54") (name "IO-CH5") (class "Default")
      (node (ref "U801") (pin "16") (pinfunction "PA6_16") (pintype "bidirectional"))
      (node (ref "U902") (pin "5") (pinfunction "A4_5") (pintype "bidirectional"))
    )
    (net (code "55") (name "IO-CH6") (class "Default")
      (node (ref "U801") (pin "17") (pinfunction "PA7_17") (pintype "bidirectional"))
      (node (ref "U902") (pin "4") (pinfunction "A3_4") (pintype "bidirectional"))
    )
    (net (code "56") (name "IO-CH7") (class "Default")
      (node (ref "U801") (pin "18") (pinfunction "PB0_18") (pintype "bidirectional"))
      (node (ref "U902") (pin "3") (pinfunction "A2_3") (pintype "bidirectional"))
    )
    (net (code "57") (name "IO-CH8") (class "Default")
      (node (ref "U801") (pin "19") (pinfunction "PB1_19") (pintype "bidirectional"))
      (node (ref "U902") (pin "1") (pinfunction "A1_1") (pintype "bidirectional"))
    )
    (net (code "58") (name "IO-SWCLK") (class "Default")
      (node (ref "JX802") (pin "4") (pinfunction "S_4") (pintype "passive"))
      (node (ref "U801") (pin "37") (pinfunction "PA14_37") (pintype "bidirectional"))
    )
    (net (code "59") (name "IO-SWDIO") (class "Default")
      (node (ref "JX802") (pin "2") (pinfunction "S_2") (pintype "passive"))
      (node (ref "U801") (pin "34") (pinfunction "PA13_34") (pintype "bidirectional"))
    )
    (net (code "60") (name "IO-SWO") (class "Default")
      (node (ref "JX802") (pin "6") (pinfunction "S_6") (pintype "passive"))
      (node (ref "U801") (pin "39") (pinfunction "PB3_39") (pintype "bidirectional"))
    )
    (net (code "61") (name "IO-USART1_RX") (class "Default")
      (node (ref "J801") (pin "P$3") (pinfunction "P$3_P$3") (pintype "bidirectional"))
      (node (ref "JX801") (pin "2") (pinfunction "+5V_2") (pintype "bidirectional"))
      (node (ref "U801") (pin "31") (pinfunction "PA10_31") (pintype "bidirectional"))
    )
    (net (code "62") (name "IO-USART1_TX") (class "Default")
      (node (ref "JX801") (pin "1") (pinfunction "PPM_1") (pintype "bidirectional"))
      (node (ref "R101") (pin "P$2") (pinfunction "2_P$2") (pintype "passive"))
      (node (ref "U801") (pin "30") (pinfunction "PA9_30") (pintype "bidirectional"))
    )
    (net (code "63") (name "IO-VDD_3V3") (class "Default")
      (node (ref "C1003") (pin "P$1") (pinfunction "1_P$1") (pintype "passive"))
      (node (ref "C1004") (pin "P$1") (pinfunction "1_P$1") (pintype "passive"))
      (node (ref "C802") (pin "P$1") (pinfunction "1_P$1") (pintype "passive"))
      (node (ref "C803") (pin "P$1") (pinfunction "1_P$1") (pintype "passive"))
      (node (ref "C804") (pin "P$1") (pinfunction "1_P$1") (pintype "passive"))
      (node (ref "C901") (pin "P$1") (pinfunction "1_P$1") (pintype "passive"))
      (node (ref "C903") (pin "P$1") (pinfunction "1_P$1") (pintype "passive"))
      (node (ref "D701") (pin "C") (pinfunction "C_C") (pintype "passive"))
      (node (ref "J702") (pin "1") (pinfunction "1_1") (pintype "passive"))
      (node (ref "JX802") (pin "1") (pinfunction "S_1") (pintype "passive"))
      (node (ref "U1002") (pin "7") (pinfunction "VOUT2_7") (pintype "bidirectional"))
      (node (ref "U801") (pin "24") (pinfunction "VDD_1_24") (pintype "power_in"))
      (node (ref "U801") (pin "36") (pinfunction "VDD_2_36") (pintype "power_in"))
      (node (ref "U801") (pin "48") (pinfunction "VDD_3_48") (pintype "power_in"))
      (node (ref "U801") (pin "9") (pinfunction "VDDA_9") (pintype "power_in"))
      (node (ref "U902") (pin "10") (pinfunction "OE_10") (pintype "input"))
      (node (ref "U902") (pin "19") (pinfunction "VCCB_19") (pintype "input"))
      (node (ref "U902") (pin "2") (pinfunction "VCCA_2") (pintype "input"))
      (node (ref "U903") (pin "8") (pinfunction "VCC_8") (pintype "power_in"))
    )
    (net (code "64") (name "IO-VDD_5V5") (class "Default")
      (node (ref "C1001") (pin "P$1") (pinfunction "1_P$1") (pintype "passive"))
      (node (ref "C1005") (pin "P$1") (pinfunction "1_P$1") (pintype "passive"))
      (node (ref "D1001") (pin "3") (pinfunction "CC_3") (pintype "passive"))
      (node (ref "J901") (pin "2") (pinfunction "S_2") (pintype "passive"))
      (node (ref "LED702") (pin "A") (pinfunction "A_A") (pintype "passive"))
      (node (ref "LED703") (pin "A") (pinfunction "A_A") (pintype "passive"))
      (node (ref "LED705") (pin "A") (pinfunction "A_A") (pintype "passive"))
      (node (ref "U1002") (pin "1") (pinfunction "VIN_1") (pintype "bidirectional"))
      (node (ref "U1002") (pin "4") (pinfunction "EN2_4") (pintype "bidirectional"))
    )
    (net (code "65") (name "IO-~{RESET}") (class "Default")
      (node (ref "C801") (pin "P$2") (pinfunction "2_P$2") (pintype "passive"))
      (node (ref "S801") (pin "A1") (pinfunction "1_A1") (pintype "passive"))
      (node (ref "U1002") (pin "3") (pinfunction "POR2_3") (pintype "bidirectional"))
      (node (ref "U801") (pin "7") (pinfunction "NRST_7") (pintype "input"))
    )
    (net (code "66") (name "IO-~{VDD_SERVO_IN_FAULT}") (class "Default")
      (node (ref "U1001") (pin "4") (pinfunction "~{FAULT}_4") (pintype "bidirectional"))
      (node (ref "U801") (pin "38") (pinfunction "PA15_38") (pintype "bidirectional"))
    )
    (net (code "67") (name "MAG_DRDY") (class "Default")
      (node (ref "U101") (pin "36") (pinfunction "PB1_36") (pintype "bidirectional"))
      (node (ref "U504") (pin "9") (pinfunction "INT2_9") (pintype "bidirectional"))
      (node (ref "X503") (pin "4") (pinfunction "S_4") (pintype "passive"))
    )
    (net (code "68") (name "MPU_DRDY") (class "Default")
      (node (ref "U101") (pin "62") (pinfunction "PD15_62") (pintype "bidirectional"))
      (node (ref "U505") (pin "12") (pinfunction "INT_12") (pintype "bidirectional"))
    )
    (net (code "69") (name "Net-(C102-1)") (class "Default")
      (node (ref "C102") (pin "P$1") (pinfunction "1_P$1") (pintype "passive"))
      (node (ref "U101") (pin "12") (pinfunction "OSC_IN_12") (pintype "input"))
      (node (ref "X101") (pin "3") (pinfunction "3_3") (pintype "bidirectional"))
    )
    (net (code "70") (name "Net-(C103-2)") (class "Default")
      (node (ref "C103") (pin "P$2") (pinfunction "2_P$2") (pintype "passive"))
      (node (ref "U101") (pin "13") (pinfunction "OSC_OUT_13") (pintype "output"))
      (node (ref "X101") (pin "1") (pinfunction "1_1") (pintype "bidirectional"))
    )
    (net (code "71") (name "Net-(C504-1)") (class "Default")
      (node (ref "C504") (pin "P$1") (pinfunction "1_P$1") (pintype "passive"))
      (node (ref "U501") (pin "14") (pinfunction "PLLFILT_14") (pintype "bidirectional"))
    )
    (net (code "72") (name "Net-(C505-1)") (class "Default")
      (node (ref "C505") (pin "P$1") (pinfunction "1_P$1") (pintype "passive"))
      (node (ref "U502") (pin "14") (pinfunction "CAP_14") (pintype "bidirectional"))
    )
    (net (code "73") (name "Net-(C509-1)") (class "Default")
      (node (ref "C509") (pin "P$1") (pinfunction "1_P$1") (pintype "passive"))
      (node (ref "U504") (pin "15") (pinfunction "C1_15") (pintype "bidirectional"))
    )
    (net (code "74") (name "Net-(C510-1)") (class "Default")
      (node (ref "C510") (pin "P$1") (pinfunction "1_P$1") (pintype "passive"))
      (node (ref "U504") (pin "2") (pinfunction "SETC_2") (pintype "bidirectional"))
    )
    (net (code "75") (name "Net-(C510-2)") (class "Default")
      (node (ref "C510") (pin "P$2") (pinfunction "2_P$2") (pintype "passive"))
      (node (ref "U504") (pin "3") (pinfunction "SETP_3") (pintype "bidirectional"))
    )
    (net (code "76") (name "Net-(C512-1)") (class "Default")
      (node (ref "C512") (pin "P$1") (pinfunction "1_P$1") (pintype "passive"))
      (node (ref "U505") (pin "10") (pinfunction "REGOUT_10") (pintype "bidirectional"))
    )
    (net (code "77") (name "Net-(C515-1)") (class "Default")
      (node (ref "C515") (pin "P$1") (pinfunction "1_P$1") (pintype "passive"))
      (node (ref "U505") (pin "20") (pinfunction "CPOUT_20") (pintype "bidirectional"))
    )
    (net (code "78") (name "Net-(C601-1)") (class "Default")
      (node (ref "C601") (pin "P$1") (pinfunction "1_P$1") (pintype "passive"))
      (node (ref "C615") (pin "P$1") (pinfunction "1_P$1") (pintype "passive"))
      (node (ref "L603") (pin "P$2") (pinfunction "P$2_P$2") (pintype "bidirectional"))
      (node (ref "R603") (pin "P$1") (pinfunction "1_P$1") (pintype "passive"))
      (node (ref "U603") (pin "1") (pinfunction "VIN_1") (pintype "bidirectional"))
      (node (ref "U603") (pin "4") (pinfunction "EN2_4") (pintype "bidirectional"))
    )
    (net (code "79") (name "Net-(C602-2)") (class "Default")
      (node (ref "C602") (pin "P$2") (pinfunction "2_P$2") (pintype "passive"))
      (node (ref "U603") (pin "6") (pinfunction "CSET_6") (pintype "bidirectional"))
    )
    (net (code "80") (name "Net-(C611-1)") (class "Default")
      (node (ref "C611") (pin "P$1") (pinfunction "1_P$1") (pintype "passive"))
      (node (ref "U101") (pin "49") (pinfunction "VCAP_1_49") (pintype "power_in"))
    )
    (net (code "81") (name "Net-(C613-1)") (class "Default")
      (node (ref "C613") (pin "P$1") (pinfunction "1_P$1") (pintype "passive"))
      (node (ref "U101") (pin "73") (pinfunction "VCAP_2_73") (pintype "power_in"))
    )
    (net (code "82") (name "Net-(C703-1)") (class "Default")
      (node (ref "C703") (pin "P$1") (pinfunction "1_P$1") (pintype "passive"))
      (node (ref "J701") (pin "1") (pinfunction "1_1") (pintype "passive"))
      (node (ref "R703") (pin "P$1") (pinfunction "1_P$1") (pintype "passive"))
      (node (ref "U702") (pin "1") (pinfunction "OUT_1") (pintype "output"))
    )
    (net (code "83") (name "Net-(C704-1)") (class "Default")
      (node (ref "C704") (pin "P$1") (pinfunction "1_P$1") (pintype "passive"))
      (node (ref "R705") (pin "P$1") (pinfunction "1_P$1") (pintype "passive"))
      (node (ref "U702") (pin "6") (pinfunction "VCC_6") (pintype "bidirectional"))
    )
    (net (code "84") (name "Net-(C805-1)") (class "Default")
      (node (ref "C805") (pin "P$1") (pinfunction "1_P$1") (pintype "passive"))
      (node (ref "U801") (pin "5") (pinfunction "PD0/OSC<=_5") (pintype "bidirectional"))
      (node (ref "X801") (pin "3") (pinfunction "3_3") (pintype "bidirectional"))
    )
    (net (code "85") (name "Net-(C806-2)") (class "Default")
      (node (ref "C806") (pin "P$2") (pinfunction "2_P$2") (pintype "passive"))
      (node (ref "U801") (pin "6") (pinfunction "PD1/OSC=>_6") (pintype "bidirectional"))
      (node (ref "X801") (pin "1") (pinfunction "1_1") (pintype "bidirectional"))
    )
    (net (code "86") (name "Net-(C1002-1)") (class "Default")
      (node (ref "C1002") (pin "P$1") (pinfunction "1_P$1") (pintype "passive"))
      (node (ref "U1002") (pin "6") (pinfunction "CSET_6") (pintype "bidirectional"))
    )
    (net (code "87") (name "Net-(C1105-1)") (class "Default")
      (node (ref "C1105") (pin "P$1") (pinfunction "1_P$1") (pintype "passive"))
      (node (ref "U1101") (pin "P$18") (pinfunction "VS1_P$18") (pintype "bidirectional"))
      (node (ref "U1102") (pin "P$1") (pinfunction "S_P$1") (pintype "passive"))
      (node (ref "U1102") (pin "P$3") (pinfunction "S_P$3") (pintype "passive"))
    )
    (net (code "88") (name "Net-(C1106-1)") (class "Default")
      (node (ref "C1106") (pin "P$1") (pinfunction "1_P$1") (pintype "passive"))
      (node (ref "U1101") (pin "P$16") (pinfunction "VS2_P$16") (pintype "bidirectional"))
      (node (ref "U1103") (pin "P$1") (pinfunction "S_P$1") (pintype "passive"))
      (node (ref "U1103") (pin "P$3") (pinfunction "S_P$3") (pintype "passive"))
    )
    (net (code "89") (name "Net-(C1107-1)") (class "Default")
      (node (ref "C1107") (pin "P$1") (pinfunction "1_P$1") (pintype "passive"))
      (node (ref "U1101") (pin "P$14") (pinfunction "VS3_P$14") (pintype "bidirectional"))
      (node (ref "U1104") (pin "P$1") (pinfunction "S_P$1") (pintype "passive"))
      (node (ref "U1104") (pin "P$3") (pinfunction "S_P$3") (pintype "passive"))
    )
    (net (code "90") (name "Net-(C1108-1)") (class "Default")
      (node (ref "C1108") (pin "P$1") (pinfunction "1_P$1") (pintype "passive"))
      (node (ref "R1105") (pin "P$2") (pinfunction "2_P$2") (pintype "passive"))
      (node (ref "R1106") (pin "P$1") (pinfunction "1_P$1") (pintype "passive"))
      (node (ref "U1101") (pin "P$1") (pinfunction "UV1_P$1") (pintype "bidirectional"))
    )
    (net (code "91") (name "Net-(C1109-1)") (class "Default")
      (node (ref "C1109") (pin "P$1") (pinfunction "1_P$1") (pintype "passive"))
      (node (ref "R1109") (pin "P$2") (pinfunction "2_P$2") (pintype "passive"))
      (node (ref "R1110") (pin "P$1") (pinfunction "1_P$1") (pintype "passive"))
      (node (ref "U1101") (pin "P$3") (pinfunction "UV2_P$3") (pintype "bidirectional"))
    )
    (net (code "92") (name "Net-(C1110-1)") (class "Default")
      (node (ref "C1110") (pin "P$1") (pinfunction "1_P$1") (pintype "passive"))
      (node (ref "R1112") (pin "P$2") (pinfunction "2_P$2") (pintype "passive"))
      (node (ref "R1113") (pin "P$1") (pinfunction "1_P$1") (pintype "passive"))
      (node (ref "U1101") (pin "P$5") (pinfunction "UV3_P$5") (pintype "bidirectional"))
    )
    (net (code "93") (name "Net-(D201-PadC)") (class "Default")
      (node (ref "D201") (pin "C") (pinfunction "C_C") (pintype "passive"))
      (node (ref "J201") (pin "1") (pinfunction "1_1") (pintype "passive"))
      (node (ref "L201") (pin "P$2") (pinfunction "P$2_P$2") (pintype "bidirectional"))
    )
    (net (code "94") (name "Net-(D202-PadC)") (class "Default")
      (node (ref "D202") (pin "C") (pinfunction "C_C") (pintype "passive"))
      (node (ref "J202") (pin "1") (pinfunction "1_1") (pintype "passive"))
      (node (ref "L202") (pin "P$2") (pinfunction "P$2_P$2") (pintype "bidirectional"))
    )
    (net (code "95") (name "Net-(D203-PadC)") (class "Default")
      (node (ref "D203") (pin "C") (pinfunction "C_C") (pintype "passive"))
      (node (ref "J203") (pin "1") (pinfunction "1_1") (pintype "passive"))
      (node (ref "J204") (pin "1") (pinfunction "1_1") (pintype "passive"))
      (node (ref "L203") (pin "P$2") (pinfunction "P$2_P$2") (pintype "bidirectional"))
    )
    (net (code "96") (name "Net-(D401-PadC)") (class "Default")
      (node (ref "D401") (pin "C") (pinfunction "C_C") (pintype "passive"))
      (node (ref "J401") (pin "1") (pinfunction "1_1") (pintype "passive"))
      (node (ref "J402") (pin "1") (pinfunction "1_1") (pintype "passive"))
      (node (ref "L401") (pin "P$2") (pinfunction "P$2_P$2") (pintype "bidirectional"))
    )
    (net (code "97") (name "Net-(D402-PadC)") (class "Default")
      (node (ref "D402") (pin "C") (pinfunction "C_C") (pintype "passive"))
      (node (ref "J403") (pin "1") (pinfunction "1_1") (pintype "passive"))
      (node (ref "L402") (pin "P$2") (pinfunction "P$2_P$2") (pintype "bidirectional"))
    )
    (net (code "98") (name "Net-(D403-PadC)") (class "Default")
      (node (ref "D403") (pin "C") (pinfunction "C_C") (pintype "passive"))
      (node (ref "J404") (pin "1") (pinfunction "1_1") (pintype "passive"))
      (node (ref "L404") (pin "P$2") (pinfunction "P$2_P$2") (pintype "bidirectional"))
    )
    (net (code "99") (name "Net-(D404-PadC)") (class "Default")
      (node (ref "D404") (pin "C") (pinfunction "C_C") (pintype "passive"))
      (node (ref "J405") (pin "1") (pinfunction "1_1") (pintype "passive"))
      (node (ref "L403") (pin "P$2") (pinfunction "P$2_P$2") (pintype "bidirectional"))
    )
    (net (code "100") (name "Net-(D904-C)") (class "Default")
      (node (ref "D903") (pin "C") (pinfunction "C_C") (pintype "passive"))
      (node (ref "D904") (pin "CATHODE") (pinfunction "C_CATHODE") (pintype "passive"))
      (node (ref "L901") (pin "P$1") (pinfunction "P$1_P$1") (pintype "bidirectional"))
    )
    (net (code "101") (name "Net-(D1001-A1)") (class "Default")
      (node (ref "D1001") (pin "1") (pinfunction "A1_1") (pintype "passive"))
      (node (ref "F1001") (pin "2") (pinfunction "2_2") (pintype "bidirectional"))
    )
    (net (code "102") (name "Net-(D1001-A2)") (class "Default")
      (node (ref "D1001") (pin "2") (pinfunction "A2_2") (pintype "passive"))
      (node (ref "U1001") (pin "8") (pinfunction "OUT_8") (pintype "bidirectional"))
    )
    (net (code "103") (name "Net-(J301-2)") (class "Default")
      (node (ref "J301") (pin "D-") (pinfunction "2_D-") (pintype "bidirectional"))
      (node (ref "J302") (pin "3") (pinfunction "3_3") (pintype "passive"))
      (node (ref "U302") (pin "1") (pinfunction "D1I_1") (pintype "bidirectional"))
    )
    (net (code "104") (name "Net-(J301-3)") (class "Default")
      (node (ref "J301") (pin "D+") (pinfunction "3_D+") (pintype "bidirectional"))
      (node (ref "J302") (pin "2") (pinfunction "2_2") (pintype "passive"))
      (node (ref "U302") (pin "3") (pinfunction "D2I_3") (pintype "bidirectional"))
    )
    (net (code "105") (name "Net-(J901A-S)") (class "Default")
      (node (ref "J901") (pin "1") (pinfunction "S_1") (pintype "passive"))
      (node (ref "R909") (pin "P$2") (pinfunction "2_P$2") (pintype "passive"))
    )
    (net (code "106") (name "Net-(J901B-S)") (class "Default")
      (node (ref "J901") (pin "10") (pinfunction "S_10") (pintype "passive"))
      (node (ref "R914") (pin "P$2") (pinfunction "2_P$2") (pintype "passive"))
    )
    (net (code "107") (name "Net-(J901C-S)") (class "Default")
      (node (ref "J901") (pin "13") (pinfunction "S_13") (pintype "passive"))
      (node (ref "R906") (pin "P$2") (pinfunction "2_P$2") (pintype "passive"))
    )
    (net (code "108") (name "Net-(J901D-S)") (class "Default")
      (node (ref "J901") (pin "16") (pinfunction "S_16") (pintype "passive"))
      (node (ref "R915") (pin "P$2") (pinfunction "2_P$2") (pintype "passive"))
    )
    (net (code "109") (name "Net-(J901E-S)") (class "Default")
      (node (ref "J901") (pin "19") (pinfunction "S_19") (pintype "passive"))
      (node (ref "R907") (pin "P$2") (pinfunction "2_P$2") (pintype "passive"))
    )
    (net (code "110") (name "Net-(J901G-S)") (class "Default")
      (node (ref "J901") (pin "22") (pinfunction "S_22") (pintype "passive"))
      (node (ref "R916") (pin "P$2") (pinfunction "2_P$2") (pintype "passive"))
    )
    (net (code "111") (name "Net-(J901H-S)") (class "Default")
      (node (ref "J901") (pin "25") (pinfunction "S_25") (pintype "passive"))
      (node (ref "R908") (pin "P$2") (pinfunction "2_P$2") (pintype "passive"))
    )
    (net (code "112") (name "Net-(J901I-S)") (class "Default")
      (node (ref "J901") (pin "28") (pinfunction "S_28") (pintype "passive"))
      (node (ref "R917") (pin "P$2") (pinfunction "2_P$2") (pintype "passive"))
    )
    (net (code "113") (name "Net-(J901J-S)") (class "Default")
      (node (ref "J901") (pin "31") (pinfunction "S_31") (pintype "passive"))
      (node (ref "R902") (pin "P$2") (pinfunction "2_P$2") (pintype "passive"))
    )
    (net (code "114") (name "Net-(J901K-S)") (class "Default")
      (node (ref "J901") (pin "34") (pinfunction "S_34") (pintype "passive"))
      (node (ref "R911") (pin "P$2") (pinfunction "2_P$2") (pintype "passive"))
    )
    (net (code "115") (name "Net-(J901L-S)") (class "Default")
      (node (ref "J901") (pin "37") (pinfunction "S_37") (pintype "passive"))
      (node (ref "R903") (pin "P$2") (pinfunction "2_P$2") (pintype "passive"))
    )
    (net (code "116") (name "Net-(J901M-S)") (class "Default")
      (node (ref "J901") (pin "4") (pinfunction "S_4") (pintype "passive"))
      (node (ref "R910") (pin "P$2") (pinfunction "2_P$2") (pintype "passive"))
    )
    (net (code "117") (name "Net-(J901N-S)") (class "Default")
      (node (ref "J901") (pin "40") (pinfunction "S_40") (pintype "passive"))
      (node (ref "R912") (pin "P$2") (pinfunction "2_P$2") (pintype "passive"))
    )
    (net (code "118") (name "Net-(J901O-S)") (class "Default")
      (node (ref "J901") (pin "43") (pinfunction "S_43") (pintype "passive"))
      (node (ref "R904") (pin "P$2") (pinfunction "2_P$2") (pintype "passive"))
    )
    (net (code "119") (name "Net-(J901P-S)") (class "Default")
      (node (ref "J901") (pin "46") (pinfunction "S_46") (pintype "passive"))
      (node (ref "R913") (pin "P$2") (pinfunction "2_P$2") (pintype "passive"))
    )
    (net (code "120") (name "Net-(J901Q-S)") (class "Default")
      (node (ref "J901") (pin "7") (pinfunction "S_7") (pintype "passive"))
      (node (ref "R905") (pin "P$2") (pinfunction "2_P$2") (pintype "passive"))
    )
    (net (code "121") (name "Net-(L701-2)") (class "Default")
      (node (ref "L701") (pin "P$2") (pinfunction "2_P$2") (pintype "passive"))
      (node (ref "U702") (pin "5") (pinfunction "SW_5") (pintype "passive"))
    )
    (net (code "122") (name "Net-(Q601-PadC)") (class "Default")
      (node (ref "Q601") (pin "C") (pinfunction "C_C") (pintype "passive"))
      (node (ref "R621") (pin "2") (pinfunction "2_2") (pintype "passive"))
    )
    (net (code "123") (name "Net-(R101-1)") (class "Default")
      (node (ref "R101") (pin "P$1") (pinfunction "1_P$1") (pintype "passive"))
      (node (ref "U101") (pin "69") (pinfunction "PA10_69") (pintype "bidirectional"))
    )
    (net (code "124") (name "Net-(R102-1)") (class "Default")
      (node (ref "R102") (pin "P$1") (pinfunction "1_P$1") (pintype "passive"))
      (node (ref "U101") (pin "37") (pinfunction "PB2_37") (pintype "bidirectional"))
    )
    (net (code "125") (name "Net-(R201-1)") (class "Default")
      (node (ref "R201") (pin "P$1") (pinfunction "1_P$1") (pintype "passive"))
      (node (ref "U201") (pin "20") (pinfunction "B1_20") (pintype "bidirectional"))
    )
    (net (code "126") (name "Net-(R202-1)") (class "Default")
      (node (ref "R202") (pin "P$1") (pinfunction "1_P$1") (pintype "passive"))
      (node (ref "U201") (pin "17") (pinfunction "B3_17") (pintype "bidirectional"))
    )
    (net (code "127") (name "Net-(R203-1)") (class "Default")
      (node (ref "R203") (pin "P$1") (pinfunction "1_P$1") (pintype "passive"))
      (node (ref "U201") (pin "15") (pinfunction "B5_15") (pintype "bidirectional"))
    )
    (net (code "128") (name "Net-(R204-1)") (class "Default")
      (node (ref "R204") (pin "P$1") (pinfunction "1_P$1") (pintype "passive"))
      (node (ref "U201") (pin "13") (pinfunction "B7_13") (pintype "bidirectional"))
    )
    (net (code "129") (name "Net-(R205-1)") (class "Default")
      (node (ref "R205") (pin "P$1") (pinfunction "1_P$1") (pintype "passive"))
      (node (ref "U202") (pin "17") (pinfunction "B3_17") (pintype "bidirectional"))
    )
    (net (code "130") (name "Net-(R206-1)") (class "Default")
      (node (ref "R206") (pin "P$1") (pinfunction "1_P$1") (pintype "passive"))
      (node (ref "U202") (pin "15") (pinfunction "B5_15") (pintype "bidirectional"))
    )
    (net (code "131") (name "Net-(R207-1)") (class "Default")
      (node (ref "R207") (pin "P$1") (pinfunction "1_P$1") (pintype "passive"))
      (node (ref "U202") (pin "13") (pinfunction "B7_13") (pintype "bidirectional"))
    )
    (net (code "132") (name "Net-(R208-1)") (class "Default")
      (node (ref "R208") (pin "P$1") (pinfunction "1_P$1") (pintype "passive"))
      (node (ref "U201") (pin "18") (pinfunction "B2_18") (pintype "bidirectional"))
    )
    (net (code "133") (name "Net-(R209-1)") (class "Default")
      (node (ref "R209") (pin "P$1") (pinfunction "1_P$1") (pintype "passive"))
      (node (ref "U201") (pin "16") (pinfunction "B4_16") (pintype "bidirectional"))
    )
    (net (code "134") (name "Net-(R210-1)") (class "Default")
      (node (ref "R210") (pin "P$1") (pinfunction "1_P$1") (pintype "passive"))
      (node (ref "U201") (pin "14") (pinfunction "B6_14") (pintype "bidirectional"))
    )
    (net (code "135") (name "Net-(R211-1)") (class "Default")
      (node (ref "R211") (pin "P$1") (pinfunction "1_P$1") (pintype "passive"))
      (node (ref "U201") (pin "12") (pinfunction "B8_12") (pintype "bidirectional"))
    )
    (net (code "136") (name "Net-(R212-1)") (class "Default")
      (node (ref "R212") (pin "P$1") (pinfunction "1_P$1") (pintype "passive"))
      (node (ref "U202") (pin "16") (pinfunction "B4_16") (pintype "bidirectional"))
    )
    (net (code "137") (name "Net-(R213-1)") (class "Default")
      (node (ref "R213") (pin "P$1") (pinfunction "1_P$1") (pintype "passive"))
      (node (ref "U202") (pin "14") (pinfunction "B6_14") (pintype "bidirectional"))
    )
    (net (code "138") (name "Net-(R214-1)") (class "Default")
      (node (ref "R214") (pin "P$1") (pinfunction "1_P$1") (pintype "passive"))
      (node (ref "U202") (pin "12") (pinfunction "B8_12") (pintype "bidirectional"))
    )
    (net (code "139") (name "Net-(R215-2)") (class "Default")
      (node (ref "J203") (pin "4") (pinfunction "4_4") (pintype "passive"))
      (node (ref "R215") (pin "P$2") (pinfunction "2_P$2") (pintype "passive"))
    )
    (net (code "140") (name "Net-(R216-2)") (class "Default")
      (node (ref "J203") (pin "5") (pinfunction "5_5") (pintype "passive"))
      (node (ref "R216") (pin "P$2") (pinfunction "2_P$2") (pintype "passive"))
    )
    (net (code "141") (name "Net-(R404-2)") (class "Default")
      (node (ref "J401") (pin "2") (pinfunction "2_2") (pintype "passive"))
      (node (ref "R404") (pin "P$2") (pinfunction "2_P$2") (pintype "passive"))
    )
    (net (code "142") (name "Net-(R405-2)") (class "Default")
      (node (ref "J401") (pin "3") (pinfunction "3_3") (pintype "passive"))
      (node (ref "R405") (pin "P$2") (pinfunction "2_P$2") (pintype "passive"))
    )
    (net (code "143") (name "Net-(R407-2)") (class "Default")
      (node (ref "J404") (pin "2") (pinfunction "2_2") (pintype "passive"))
      (node (ref "R407") (pin "P$2") (pinfunction "2_P$2") (pintype "passive"))
    )
    (net (code "144") (name "Net-(R408-2)") (class "Default")
      (node (ref "J404") (pin "4") (pinfunction "4_4") (pintype "passive"))
      (node (ref "R408") (pin "P$2") (pinfunction "2_P$2") (pintype "passive"))
    )
    (net (code "145") (name "Net-(R608-2)") (class "Default")
      (node (ref "D602") (pin "C") (pinfunction "C_C") (pintype "passive"))
      (node (ref "R608") (pin "P$2") (pinfunction "2_P$2") (pintype "passive"))
    )
    (net (code "146") (name "Net-(R616-1)") (class "Default")
      (node (ref "R616") (pin "P$1") (pinfunction "1_P$1") (pintype "passive"))
      (node (ref "U602") (pin "7") (pinfunction "ILIM_7") (pintype "bidirectional"))
    )
    (net (code "147") (name "Net-(R617-1)") (class "Default")
      (node (ref "R617") (pin "P$1") (pinfunction "1_P$1") (pintype "passive"))
      (node (ref "U601") (pin "7") (pinfunction "ILIM_7") (pintype "bidirectional"))
    )
    (net (code "148") (name "Net-(R620-1)") (class "Default")
      (node (ref "Q601") (pin "B") (pinfunction "B_B") (pintype "passive"))
      (node (ref "R620") (pin "P$1") (pinfunction "1_P$1") (pintype "passive"))
    )
    (net (code "149") (name "Net-(R701-1)") (class "Default")
      (node (ref "R701") (pin "P$1") (pinfunction "1_P$1") (pintype "passive"))
      (node (ref "U702") (pin "7") (pinfunction "+IN_7") (pintype "input"))
    )
    (net (code "150") (name "Net-(R702-1)") (class "Default")
      (node (ref "R702") (pin "P$1") (pinfunction "1_P$1") (pintype "passive"))
      (node (ref "R703") (pin "P$2") (pinfunction "2_P$2") (pintype "passive"))
      (node (ref "U702") (pin "8") (pinfunction "-IN_8") (pintype "input"))
    )
    (net (code "151") (name "Net-(R704-2)") (class "Default")
      (node (ref "R704") (pin "P$2") (pinfunction "2_P$2") (pintype "passive"))
      (node (ref "U701") (pin "6") (pinfunction "REXT_6") (pintype "bidirectional"))
    )
    (net (code "152") (name "Net-(R705-2)") (class "Default")
      (node (ref "R705") (pin "P$2") (pinfunction "2_P$2") (pintype "passive"))
      (node (ref "R706") (pin "P$1") (pinfunction "1_P$1") (pintype "passive"))
      (node (ref "U702") (pin "2") (pinfunction "FB_2") (pintype "bidirectional"))
    )
    (net (code "153") (name "Net-(R707-2)") (class "Default")
      (node (ref "R707") (pin "P$2") (pinfunction "2_P$2") (pintype "passive"))
      (node (ref "R735") (pin "P$1") (pinfunction "1_P$1") (pintype "passive"))
    )
    (net (code "154") (name "Net-(R708-2)") (class "Default")
      (node (ref "LED702") (pin "C") (pinfunction "C_C") (pintype "passive"))
      (node (ref "R708") (pin "P$2") (pinfunction "2_P$2") (pintype "passive"))
    )
    (net (code "155") (name "Net-(R709-2)") (class "Default")
      (node (ref "R709") (pin "P$2") (pinfunction "2_P$2") (pintype "passive"))
      (node (ref "R736") (pin "P$1") (pinfunction "1_P$1") (pintype "passive"))
    )
    (net (code "156") (name "Net-(R710-1)") (class "Default")
      (node (ref "J702") (pin "2") (pinfunction "2_2") (pintype "passive"))
      (node (ref "R710") (pin "P$1") (pinfunction "1_P$1") (pintype "passive"))
    )
    (net (code "157") (name "Net-(R711-2)") (class "Default")
      (node (ref "LED704") (pin "C") (pinfunction "C_C") (pintype "passive"))
      (node (ref "R711") (pin "P$2") (pinfunction "2_P$2") (pintype "passive"))
    )
    (net (code "158") (name "Net-(R712-2)") (class "Default")
      (node (ref "LED705") (pin "C") (pinfunction "C_C") (pintype "passive"))
      (node (ref "R712") (pin "P$2") (pinfunction "2_P$2") (pintype "passive"))
    )
    (net (code "159") (name "Net-(R735-2)") (class "Default")
      (node (ref "LED701") (pin "C") (pinfunction "C_C") (pintype "passive"))
      (node (ref "R735") (pin "P$2") (pinfunction "2_P$2") (pintype "passive"))
    )
    (net (code "160") (name "Net-(R736-2)") (class "Default")
      (node (ref "LED703") (pin "C") (pinfunction "C_C") (pintype "passive"))
      (node (ref "R736") (pin "P$2") (pinfunction "2_P$2") (pintype "passive"))
    )
    (net (code "161") (name "Net-(R802-1)") (class "Default")
      (node (ref "R802") (pin "P$1") (pinfunction "1_P$1") (pintype "passive"))
      (node (ref "U801") (pin "20") (pinfunction "PB2_20") (pintype "bidirectional"))
    )
    (net (code "162") (name "Net-(R803-1)") (class "Default")
      (node (ref "R803") (pin "P$1") (pinfunction "1_P$1") (pintype "passive"))
      (node (ref "U801") (pin "12") (pinfunction "PA2_12") (pintype "bidirectional"))
    )
    (net (code "163") (name "Net-(R804-1)") (class "Default")
      (node (ref "R804") (pin "P$1") (pinfunction "1_P$1") (pintype "passive"))
      (node (ref "U801") (pin "13") (pinfunction "PA3_13") (pintype "bidirectional"))
    )
    (net (code "164") (name "Net-(R901-2)") (class "Default")
      (node (ref "D902") (pin "C") (pinfunction "C_C") (pintype "passive"))
      (node (ref "R901") (pin "P$2") (pinfunction "2_P$2") (pintype "passive"))
      (node (ref "R910") (pin "P$1") (pinfunction "1_P$1") (pintype "passive"))
      (node (ref "U903") (pin "3") (pinfunction "2Y_3") (pintype "bidirectional"))
    )
    (net (code "165") (name "Net-(R902-1)") (class "Default")
      (node (ref "R902") (pin "P$1") (pinfunction "1_P$1") (pintype "passive"))
      (node (ref "U901") (pin "20") (pinfunction "B1_20") (pintype "bidirectional"))
    )
    (net (code "166") (name "Net-(R903-1)") (class "Default")
      (node (ref "R903") (pin "P$1") (pinfunction "1_P$1") (pintype "passive"))
      (node (ref "U901") (pin "17") (pinfunction "B3_17") (pintype "bidirectional"))
    )
    (net (code "167") (name "Net-(R904-1)") (class "Default")
      (node (ref "R904") (pin "P$1") (pinfunction "1_P$1") (pintype "passive"))
      (node (ref "U901") (pin "15") (pinfunction "B5_15") (pintype "bidirectional"))
    )
    (net (code "168") (name "Net-(R905-1)") (class "Default")
      (node (ref "R905") (pin "P$1") (pinfunction "1_P$1") (pintype "passive"))
      (node (ref "U902") (pin "20") (pinfunction "B1_20") (pintype "bidirectional"))
    )
    (net (code "169") (name "Net-(R906-1)") (class "Default")
      (node (ref "R906") (pin "P$1") (pinfunction "1_P$1") (pintype "passive"))
      (node (ref "U902") (pin "17") (pinfunction "B3_17") (pintype "bidirectional"))
    )
    (net (code "170") (name "Net-(R907-1)") (class "Default")
      (node (ref "R907") (pin "P$1") (pinfunction "1_P$1") (pintype "passive"))
      (node (ref "U902") (pin "15") (pinfunction "B5_15") (pintype "bidirectional"))
    )
    (net (code "171") (name "Net-(R908-1)") (class "Default")
      (node (ref "R908") (pin "P$1") (pinfunction "1_P$1") (pintype "passive"))
      (node (ref "U902") (pin "13") (pinfunction "B7_13") (pintype "bidirectional"))
    )
    (net (code "172") (name "Net-(R911-1)") (class "Default")
      (node (ref "R911") (pin "P$1") (pinfunction "1_P$1") (pintype "passive"))
      (node (ref "U901") (pin "18") (pinfunction "B2_18") (pintype "bidirectional"))
    )
    (net (code "173") (name "Net-(R912-1)") (class "Default")
      (node (ref "R912") (pin "P$1") (pinfunction "1_P$1") (pintype "passive"))
      (node (ref "U901") (pin "16") (pinfunction "B4_16") (pintype "bidirectional"))
    )
    (net (code "174") (name "Net-(R913-1)") (class "Default")
      (node (ref "R913") (pin "P$1") (pinfunction "1_P$1") (pintype "passive"))
      (node (ref "U901") (pin "14") (pinfunction "B6_14") (pintype "bidirectional"))
    )
    (net (code "175") (name "Net-(R914-1)") (class "Default")
      (node (ref "R914") (pin "P$1") (pinfunction "1_P$1") (pintype "passive"))
      (node (ref "U902") (pin "18") (pinfunction "B2_18") (pintype "bidirectional"))
    )
    (net (code "176") (name "Net-(R915-1)") (class "Default")
      (node (ref "R915") (pin "P$1") (pinfunction "1_P$1") (pintype "passive"))
      (node (ref "U902") (pin "16") (pinfunction "B4_16") (pintype "bidirectional"))
    )
    (net (code "177") (name "Net-(R916-1)") (class "Default")
      (node (ref "R916") (pin "P$1") (pinfunction "1_P$1") (pintype "passive"))
      (node (ref "U902") (pin "14") (pinfunction "B6_14") (pintype "bidirectional"))
    )
    (net (code "178") (name "Net-(R917-1)") (class "Default")
      (node (ref "R917") (pin "P$1") (pinfunction "1_P$1") (pintype "passive"))
      (node (ref "U902") (pin "12") (pinfunction "B8_12") (pintype "bidirectional"))
    )
    (net (code "179") (name "Net-(R918-2)") (class "Default")
      (node (ref "R918") (pin "P$2") (pinfunction "2_P$2") (pintype "passive"))
      (node (ref "R922") (pin "P$1") (pinfunction "1_P$1") (pintype "passive"))
    )
    (net (code "180") (name "Net-(R1001-2)") (class "Default")
      (node (ref "R1001") (pin "P$2") (pinfunction "2_P$2") (pintype "passive"))
      (node (ref "U1001") (pin "7") (pinfunction "ILIM_7") (pintype "bidirectional"))
    )
    (net (code "181") (name "Net-(R1101-2)") (class "Default")
      (node (ref "L1101") (pin "P$2") (pinfunction "P$2_P$2") (pintype "bidirectional"))
      (node (ref "R1101") (pin "P$2") (pinfunction "2_P$2") (pintype "passive"))
    )
    (net (code "182") (name "Net-(R1102-2)") (class "Default")
      (node (ref "L1102") (pin "P$2") (pinfunction "P$2_P$2") (pintype "bidirectional"))
      (node (ref "R1102") (pin "P$2") (pinfunction "2_P$2") (pintype "passive"))
    )
    (net (code "183") (name "Net-(R1103-1)") (class "Default")
      (node (ref "J601") (pin "4") (pinfunction "4_4") (pintype "passive"))
      (node (ref "L1102") (pin "P$1") (pinfunction "P$1_P$1") (pintype "bidirectional"))
      (node (ref "R1103") (pin "P$1") (pinfunction "1_P$1") (pintype "passive"))
    )
    (net (code "184") (name "Net-(R1104-1)") (class "Default")
      (node (ref "J601") (pin "3") (pinfunction "3_3") (pintype "passive"))
      (node (ref "L1101") (pin "P$1") (pinfunction "P$1_P$1") (pintype "bidirectional"))
      (node (ref "R1104") (pin "P$1") (pinfunction "1_P$1") (pintype "passive"))
    )
    (net (code "185") (name "Net-(R1106-2)") (class "Default")
      (node (ref "R1106") (pin "P$2") (pinfunction "2_P$2") (pintype "passive"))
      (node (ref "R1107") (pin "P$1") (pinfunction "1_P$1") (pintype "passive"))
      (node (ref "U1101") (pin "P$2") (pinfunction "OV1_P$2") (pintype "bidirectional"))
    )
    (net (code "186") (name "Net-(R1110-2)") (class "Default")
      (node (ref "R1110") (pin "P$2") (pinfunction "2_P$2") (pintype "passive"))
      (node (ref "R1111") (pin "P$1") (pinfunction "1_P$1") (pintype "passive"))
      (node (ref "U1101") (pin "P$4") (pinfunction "OV2_P$4") (pintype "bidirectional"))
    )
    (net (code "187") (name "Net-(R1113-2)") (class "Default")
      (node (ref "R1113") (pin "P$2") (pinfunction "2_P$2") (pintype "passive"))
      (node (ref "R1114") (pin "P$1") (pinfunction "1_P$1") (pintype "passive"))
      (node (ref "U1101") (pin "P$6") (pinfunction "OV3_P$6") (pintype "bidirectional"))
    )
    (net (code "188") (name "Net-(R1115-2)") (class "Default")
      (node (ref "R1115") (pin "P$2") (pinfunction "2_P$2") (pintype "passive"))
      (node (ref "U1101") (pin "P$24") (pinfunction "HYS_P$24") (pintype "bidirectional"))
    )
    (net (code "189") (name "Net-(U701-OUT0)") (class "Default")
      (node (ref "U701") (pin "9") (pinfunction "OUT0_9") (pintype "open_collector"))
      (node (ref "U703") (pin "C1") (pinfunction "C_C1") (pintype "passive"))
    )
    (net (code "190") (name "Net-(U701-OUT1)") (class "Default")
      (node (ref "U701") (pin "8") (pinfunction "OUT1_8") (pintype "open_collector"))
      (node (ref "U703") (pin "C2") (pinfunction "C_C2") (pintype "passive"))
    )
    (net (code "191") (name "Net-(U701-OUT2)") (class "Default")
      (node (ref "U701") (pin "7") (pinfunction "OUT2_7") (pintype "open_collector"))
      (node (ref "U703") (pin "C3") (pinfunction "C_C3") (pintype "passive"))
    )
    (net (code "192") (name "Net-(U1101-G1)") (class "Default")
      (node (ref "U1101") (pin "P$17") (pinfunction "G1_P$17") (pintype "bidirectional"))
      (node (ref "U1102") (pin "P$2") (pinfunction "G_P$2") (pintype "passive"))
      (node (ref "U1102") (pin "P$4") (pinfunction "G_P$4") (pintype "passive"))
    )
    (net (code "193") (name "Net-(U1101-G2)") (class "Default")
      (node (ref "U1101") (pin "P$15") (pinfunction "G2_P$15") (pintype "bidirectional"))
      (node (ref "U1103") (pin "P$2") (pinfunction "G_P$2") (pintype "passive"))
      (node (ref "U1103") (pin "P$4") (pinfunction "G_P$4") (pintype "passive"))
    )
    (net (code "194") (name "Net-(U1101-G3)") (class "Default")
      (node (ref "U1101") (pin "P$13") (pinfunction "G3_P$13") (pintype "bidirectional"))
      (node (ref "U1104") (pin "P$2") (pinfunction "G_P$2") (pintype "passive"))
      (node (ref "U1104") (pin "P$4") (pinfunction "G_P$4") (pintype "passive"))
    )
    (net (code "195") (name "OTG_FS_DM") (class "Default")
      (node (ref "U101") (pin "70") (pinfunction "PA11_70") (pintype "bidirectional"))
      (node (ref "U302") (pin "6") (pinfunction "D1O_6") (pintype "bidirectional"))
    )
    (net (code "196") (name "OTG_FS_DP") (class "Default")
      (node (ref "U101") (pin "71") (pinfunction "PA12_71") (pintype "bidirectional"))
      (node (ref "U302") (pin "4") (pinfunction "D2O_4") (pintype "bidirectional"))
    )
    (net (code "197") (name "PPM_INPUT") (class "Default")
      (node (ref "D901") (pin "C") (pinfunction "C_C") (pintype "passive"))
      (node (ref "R909") (pin "P$1") (pinfunction "1_P$1") (pintype "passive"))
      (node (ref "U801") (pin "29") (pinfunction "PA8_29") (pintype "bidirectional"))
      (node (ref "U903") (pin "2") (pinfunction "1A_2") (pintype "bidirectional"))
    )
    (net (code "198") (name "PRESSURE_SENS") (class "Default")
      (node (ref "C401") (pin "P$1") (pinfunction "1_P$1") (pintype "passive"))
      (node (ref "R403") (pin "P$2") (pinfunction "2_P$2") (pintype "passive"))
      (node (ref "R406") (pin "P$1") (pinfunction "1_P$1") (pintype "passive"))
      (node (ref "U101") (pin "34") (pinfunction "PC5_34") (pintype "bidirectional"))
    )
    (net (code "199") (name "PRESSURE_SENS_IN") (class "Default")
      (node (ref "ADC_PR") (pin "P$1") (pinfunction "P$1_P$1") (pintype "passive"))
      (node (ref "J402") (pin "2") (pinfunction "2_2") (pintype "passive"))
      (node (ref "R406") (pin "P$2") (pinfunction "2_P$2") (pintype "passive"))
    )
    (net (code "200") (name "RSSI_IN") (class "Default")
      (node (ref "R901") (pin "P$1") (pinfunction "1_P$1") (pintype "passive"))
      (node (ref "U801") (pin "15") (pinfunction "PA5_15") (pintype "bidirectional"))
      (node (ref "U801") (pin "33") (pinfunction "PA12_33") (pintype "bidirectional"))
    )
    (net (code "201") (name "SAFETY") (class "Default")
      (node (ref "J702") (pin "3") (pinfunction "3_3") (pintype "passive"))
      (node (ref "R713") (pin "P$1") (pinfunction "1_P$1") (pintype "passive"))
      (node (ref "U801") (pin "41") (pinfunction "PB5_41") (pintype "bidirectional"))
    )
    (net (code "202") (name "SBUS_INPUT") (class "Default")
      (node (ref "U801") (pin "22") (pinfunction "PB11_22") (pintype "bidirectional"))
      (node (ref "U903") (pin "6") (pinfunction "1Y_6") (pintype "bidirectional"))
    )
    (net (code "203") (name "SBUS_OUTPUT") (class "Default")
      (node (ref "U801") (pin "21") (pinfunction "PB10_21") (pintype "bidirectional"))
      (node (ref "U903") (pin "5") (pinfunction "2A_5") (pintype "bidirectional"))
    )
    (net (code "204") (name "SDIO_CK") (class "Default")
      (node (ref "U101") (pin "80") (pinfunction "PC12_80") (pintype "bidirectional"))
      (node (ref "U301") (pin "5") (pinfunction "CLK_5") (pintype "bidirectional"))
    )
    (net (code "205") (name "SDIO_CMD") (class "Default")
      (node (ref "R303") (pin "P$1") (pinfunction "1_P$1") (pintype "passive"))
      (node (ref "U101") (pin "83") (pinfunction "PD2_83") (pintype "bidirectional"))
      (node (ref "U301") (pin "3") (pinfunction "CMD_3") (pintype "bidirectional"))
    )
    (net (code "206") (name "SDIO_D0") (class "Default")
      (node (ref "R304") (pin "P$1") (pinfunction "1_P$1") (pintype "passive"))
      (node (ref "U101") (pin "65") (pinfunction "PC8_65") (pintype "bidirectional"))
      (node (ref "U301") (pin "7") (pinfunction "D0_7") (pintype "bidirectional"))
    )
    (net (code "207") (name "SDIO_D1") (class "Default")
      (node (ref "R305") (pin "P$1") (pinfunction "1_P$1") (pintype "passive"))
      (node (ref "U101") (pin "66") (pinfunction "PC9_66") (pintype "bidirectional"))
      (node (ref "U301") (pin "8") (pinfunction "D1_8") (pintype "bidirectional"))
    )
    (net (code "208") (name "SDIO_D2") (class "Default")
      (node (ref "R301") (pin "P$1") (pinfunction "1_P$1") (pintype "passive"))
      (node (ref "U101") (pin "78") (pinfunction "PC10_78") (pintype "bidirectional"))
      (node (ref "U301") (pin "1") (pinfunction "D2_1") (pintype "bidirectional"))
    )
    (net (code "209") (name "SDIO_D3") (class "Default")
      (node (ref "R302") (pin "P$1") (pinfunction "1_P$1") (pintype "passive"))
      (node (ref "U101") (pin "79") (pinfunction "PC11_79") (pintype "bidirectional"))
      (node (ref "U301") (pin "2") (pinfunction "D3_2") (pintype "bidirectional"))
    )
    (net (code "210") (name "SERIAL1_CTS") (class "Default")
      (node (ref "J201") (pin "4") (pinfunction "4_4") (pintype "passive"))
      (node (ref "R211") (pin "P$2") (pinfunction "2_P$2") (pintype "passive"))
    )
    (net (code "211") (name "SERIAL1_RTS") (class "Default")
      (node (ref "J201") (pin "5") (pinfunction "5_5") (pintype "passive"))
      (node (ref "R204") (pin "P$2") (pinfunction "2_P$2") (pintype "passive"))
    )
    (net (code "212") (name "SERIAL1_RX") (class "Default")
      (node (ref "J201") (pin "3") (pinfunction "3_3") (pintype "passive"))
      (node (ref "R203") (pin "P$2") (pinfunction "2_P$2") (pintype "passive"))
      (node (ref "S1RX") (pin "P$1") (pinfunction "P$1_P$1") (pintype "passive"))
    )
    (net (code "213") (name "SERIAL1_TX") (class "Default")
      (node (ref "J201") (pin "2") (pinfunction "2_2") (pintype "passive"))
      (node (ref "R210") (pin "P$2") (pinfunction "2_P$2") (pintype "passive"))
      (node (ref "S1TX") (pin "P$1") (pinfunction "P$1_P$1") (pintype "passive"))
    )
    (net (code "214") (name "SERIAL2_CTS") (class "Default")
      (node (ref "J202") (pin "4") (pinfunction "4_4") (pintype "passive"))
      (node (ref "R208") (pin "P$2") (pinfunction "2_P$2") (pintype "passive"))
    )
    (net (code "215") (name "SERIAL2_RTS") (class "Default")
      (node (ref "J202") (pin "5") (pinfunction "5_5") (pintype "passive"))
      (node (ref "R201") (pin "P$2") (pinfunction "2_P$2") (pintype "passive"))
    )
    (net (code "216") (name "SERIAL2_RX") (class "Default")
      (node (ref "J202") (pin "3") (pinfunction "3_3") (pintype "passive"))
      (node (ref "R202") (pin "P$2") (pinfunction "2_P$2") (pintype "passive"))
      (node (ref "S2RX") (pin "P$1") (pinfunction "P$1_P$1") (pintype "passive"))
    )
    (net (code "217") (name "SERIAL2_TX") (class "Default")
      (node (ref "J202") (pin "2") (pinfunction "2_2") (pintype "passive"))
      (node (ref "R209") (pin "P$2") (pinfunction "2_P$2") (pintype "passive"))
      (node (ref "S2TX") (pin "P$1") (pinfunction "P$1_P$1") (pintype "passive"))
    )
    (net (code "218") (name "SERIAL3_RX") (class "Default")
      (node (ref "J203") (pin "3") (pinfunction "3_3") (pintype "passive"))
      (node (ref "R207") (pin "P$2") (pinfunction "2_P$2") (pintype "passive"))
      (node (ref "S3RX") (pin "P$1") (pinfunction "P$1_P$1") (pintype "passive"))
    )
    (net (code "219") (name "SERIAL3_TX") (class "Default")
      (node (ref "J203") (pin "2") (pinfunction "2_2") (pintype "passive"))
      (node (ref "R214") (pin "P$2") (pinfunction "2_P$2") (pintype "passive"))
      (node (ref "S3TX") (pin "P$1") (pinfunction "P$1_P$1") (pintype "passive"))
    )
    (net (code "220") (name "SERIAL4_RX") (class "Default")
      (node (ref "J204") (pin "3") (pinfunction "3_3") (pintype "passive"))
      (node (ref "R206") (pin "P$2") (pinfunction "2_P$2") (pintype "passive"))
      (node (ref "S4RX") (pin "P$1") (pinfunction "P$1_P$1") (pintype "passive"))
    )
    (net (code "221") (name "SERIAL4_TX") (class "Default")
      (node (ref "J204") (pin "2") (pinfunction "2_2") (pintype "passive"))
      (node (ref "R213") (pin "P$2") (pinfunction "2_P$2") (pintype "passive"))
      (node (ref "S4TX") (pin "P$1") (pinfunction "P$1_P$1") (pintype "passive"))
    )
    (net (code "222") (name "SERIAL5_RX") (class "Default")
      (node (ref "J204") (pin "5") (pinfunction "5_5") (pintype "passive"))
      (node (ref "R205") (pin "P$2") (pinfunction "2_P$2") (pintype "passive"))
      (node (ref "S5_RX") (pin "P$1") (pinfunction "P$1_P$1") (pintype "passive"))
    )
    (net (code "223") (name "SERIAL5_TX") (class "Default")
      (node (ref "J204") (pin "4") (pinfunction "4_4") (pintype "passive"))
      (node (ref "R212") (pin "P$2") (pinfunction "2_P$2") (pintype "passive"))
      (node (ref "S5_TX") (pin "P$1") (pinfunction "P$1_P$1") (pintype "passive"))
    )
    (net (code "224") (name "SERIAL_FMU_TO_IO") (class "Default")
      (node (ref "R804") (pin "P$2") (pinfunction "2_P$2") (pintype "passive"))
      (node (ref "U101") (pin "63") (pinfunction "PC6_63") (pintype "bidirectional"))
    )
    (net (code "225") (name "SERIAL_IO_TO_FMU") (class "Default")
      (node (ref "R803") (pin "P$2") (pinfunction "2_P$2") (pintype "passive"))
      (node (ref "U101") (pin "64") (pinfunction "PC7_64") (pintype "bidirectional"))
    )
    (net (code "226") (name "SPI_EXT_MISO") (class "Default")
      (node (ref "J403") (pin "3") (pinfunction "3_3") (pintype "passive"))
      (node (ref "U101") (pin "4") (pinfunction "PE5_4") (pintype "bidirectional"))
    )
    (net (code "227") (name "SPI_EXT_MOSI") (class "Default")
      (node (ref "J403") (pin "4") (pinfunction "4_4") (pintype "passive"))
      (node (ref "U101") (pin "5") (pinfunction "PE6_5") (pintype "bidirectional"))
    )
    (net (code "228") (name "SPI_EXT_SCK") (class "Default")
      (node (ref "J403") (pin "2") (pinfunction "2_2") (pintype "passive"))
      (node (ref "U101") (pin "1") (pinfunction "PE2_1") (pintype "bidirectional"))
    )
    (net (code "229") (name "SPI_INT_MISO") (class "Default")
      (node (ref "U101") (pin "31") (pinfunction "PA6_31") (pintype "bidirectional"))
      (node (ref "U501") (pin "4") (pinfunction "SDO/SA0_4") (pintype "bidirectional"))
      (node (ref "U502") (pin "4") (pinfunction "SDO/SA0_4") (pintype "bidirectional"))
      (node (ref "U504") (pin "7") (pinfunction "SDO/SA0_7") (pintype "bidirectional"))
      (node (ref "U505") (pin "9") (pinfunction "AD0/SDO_9") (pintype "bidirectional"))
      (node (ref "U506") (pin "6") (pinfunction "SDO_6") (pintype "bidirectional"))
      (node (ref "X503") (pin "9") (pinfunction "S_9") (pintype "passive"))
    )
    (net (code "230") (name "SPI_INT_MOSI") (class "Default")
      (node (ref "U101") (pin "32") (pinfunction "PA7_32") (pintype "bidirectional"))
      (node (ref "U501") (pin "3") (pinfunction "SDA/SDI/SDO_3") (pintype "bidirectional"))
      (node (ref "U502") (pin "3") (pinfunction "SDA/SDI/SDO_3") (pintype "bidirectional"))
      (node (ref "U504") (pin "6") (pinfunction "SDA/SDI/SDO_6") (pintype "bidirectional"))
      (node (ref "U505") (pin "24") (pinfunction "SDA/SDI_24") (pintype "bidirectional"))
      (node (ref "U506") (pin "7") (pinfunction "SDI/SDA_7") (pintype "bidirectional"))
      (node (ref "X503") (pin "8") (pinfunction "S_8") (pintype "passive"))
    )
    (net (code "231") (name "SPI_INT_SCK") (class "Default")
      (node (ref "U101") (pin "30") (pinfunction "PA5_30") (pintype "bidirectional"))
      (node (ref "U501") (pin "2") (pinfunction "SCL/SPC_2") (pintype "input"))
      (node (ref "U502") (pin "2") (pinfunction "SCL/SPC_2") (pintype "bidirectional"))
      (node (ref "U504") (pin "4") (pinfunction "SCL/SPC_4") (pintype "bidirectional"))
      (node (ref "U505") (pin "23") (pinfunction "SCL/SCLK_23") (pintype "bidirectional"))
      (node (ref "U506") (pin "8") (pinfunction "SCLK_8") (pintype "bidirectional"))
      (node (ref "X503") (pin "10") (pinfunction "S_10") (pintype "passive"))
    )
    (net (code "232") (name "VBAT") (class "Default")
      (node (ref "B601") (pin "1") (pinfunction "POS_1") (pintype "bidirectional"))
      (node (ref "R608") (pin "P$1") (pinfunction "1_P$1") (pintype "passive"))
      (node (ref "U101") (pin "6") (pinfunction "VBAT_6") (pintype "power_in"))
      (node (ref "U801") (pin "1") (pinfunction "VBAT_1") (pintype "power_in"))
    )
    (net (code "233") (name "VBUS") (class "Default")
      (node (ref "C1103") (pin "P$1") (pinfunction "1_P$1") (pintype "passive"))
      (node (ref "J301") (pin "VBUS") (pinfunction "1_VBUS") (pintype "power_in"))
      (node (ref "J302") (pin "1") (pinfunction "1_1") (pintype "passive"))
      (node (ref "R1112") (pin "P$1") (pinfunction "1_P$1") (pintype "passive"))
      (node (ref "U101") (pin "68") (pinfunction "PA9_68") (pintype "bidirectional"))
      (node (ref "U1101") (pin "P$19") (pinfunction "V3_P$19") (pintype "bidirectional"))
      (node (ref "U1104") (pin "P$7") (pinfunction "D_P$7") (pintype "passive"))
      (node (ref "U1104") (pin "P$8") (pinfunction "D_P$8") (pintype "passive"))
      (node (ref "U302") (pin "5") (pinfunction "VBUS_5") (pintype "bidirectional"))
      (node (ref "VBUS") (pin "P$1") (pinfunction "P$1_P$1") (pintype "passive"))
    )
    (net (code "234") (name "VDD_3V3_SENSORS") (class "Default")
      (node (ref "C501") (pin "P$1") (pinfunction "1_P$1") (pintype "passive"))
      (node (ref "C502") (pin "P$1") (pinfunction "1_P$1") (pintype "passive"))
      (node (ref "C503") (pin "P$1") (pinfunction "1_P$1") (pintype "passive"))
      (node (ref "C506") (pin "P$1") (pinfunction "1_P$1") (pintype "passive"))
      (node (ref "C507") (pin "P$1") (pinfunction "1_P$1") (pintype "passive"))
      (node (ref "C508") (pin "P$1") (pinfunction "1_P$1") (pintype "passive"))
      (node (ref "C511") (pin "P$1") (pinfunction "1_P$1") (pintype "passive"))
      (node (ref "C513") (pin "P$1") (pinfunction "1_P$1") (pintype "passive"))
      (node (ref "C514") (pin "P$1") (pinfunction "1_P$1") (pintype "passive"))
      (node (ref "C605") (pin "P$1") (pinfunction "1_P$1") (pintype "passive"))
      (node (ref "C617") (pin "P$1") (pinfunction "1_P$1") (pintype "passive"))
      (node (ref "Q601") (pin "E") (pinfunction "E_E") (pintype "passive"))
      (node (ref "U501") (pin "1") (pinfunction "VDD_IO_1") (pintype "bidirectional"))
      (node (ref "U501") (pin "15") (pinfunction "RES_P15_VDD_15") (pintype "bidirectional"))
      (node (ref "U501") (pin "16") (pinfunction "VDD_16") (pintype "bidirectional"))
      (node (ref "U502") (pin "1") (pinfunction "VDD_IO_1") (pintype "bidirectional"))
      (node (ref "U502") (pin "15") (pinfunction "VDD_15") (pintype "bidirectional"))
      (node (ref "U502") (pin "16") (pinfunction "VDD_16") (pintype "bidirectional"))
      (node (ref "U504") (pin "1") (pinfunction "VDD_IO_1") (pintype "bidirectional"))
      (node (ref "U504") (pin "14") (pinfunction "VDD_14") (pintype "bidirectional"))
      (node (ref "U505") (pin "13") (pinfunction "VDD_13") (pintype "bidirectional"))
      (node (ref "U506") (pin "1") (pinfunction "VDD_1") (pintype "bidirectional"))
      (node (ref "U603") (pin "8") (pinfunction "VOUT1_8") (pintype "bidirectional"))
      (node (ref "VDDA_3V1101") (pin "P$1") (pinfunction "P$1_P$1") (pintype "passive"))
      (node (ref "X503") (pin "1") (pinfunction "S_1") (pintype "passive"))
    )
    (net (code "235") (name "VDD_3V3_SENSORS_EN") (class "Default")
      (node (ref "R603") (pin "P$2") (pinfunction "2_P$2") (pintype "passive"))
      (node (ref "R620") (pin "P$2") (pinfunction "2_P$2") (pintype "passive"))
      (node (ref "R635") (pin "P$2") (pinfunction "2_P$2") (pintype "passive"))
      (node (ref "U101") (pin "2") (pinfunction "PE3_2") (pintype "bidirectional"))
      (node (ref "U603") (pin "5") (pinfunction "EN1_5") (pintype "bidirectional"))
    )
    (net (code "236") (name "VDD_3V3_SPEKTRUM") (class "Default")
      (node (ref "C1008") (pin "P$1") (pinfunction "1_P$1") (pintype "passive"))
      (node (ref "D801") (pin "C") (pinfunction "C_C") (pintype "passive"))
      (node (ref "J801") (pin "P$1") (pinfunction "P$1_P$1") (pintype "bidirectional"))
      (node (ref "U1002") (pin "8") (pinfunction "VOUT1_8") (pintype "bidirectional"))
    )
    (net (code "237") (name "VDD_3V3_SPEKTRUM_EN") (class "Default")
      (node (ref "R1002") (pin "P$2") (pinfunction "2_P$2") (pintype "passive"))
      (node (ref "U1002") (pin "5") (pinfunction "EN1_5") (pintype "bidirectional"))
      (node (ref "U801") (pin "2") (pinfunction "PC13_2") (pintype "bidirectional"))
    )
    (net (code "238") (name "VDD_5V_BRICK") (class "Default")
      (node (ref "C1101") (pin "P$1") (pinfunction "1_P$1") (pintype "passive"))
      (node (ref "J601") (pin "1") (pinfunction "1_1") (pintype "passive"))
      (node (ref "J601") (pin "2") (pinfunction "2_2") (pintype "passive"))
      (node (ref "R1105") (pin "P$1") (pinfunction "1_P$1") (pintype "passive"))
      (node (ref "U1101") (pin "P$21") (pinfunction "V1_P$21") (pintype "bidirectional"))
      (node (ref "U1102") (pin "P$7") (pinfunction "D_P$7") (pintype "passive"))
      (node (ref "U1102") (pin "P$8") (pinfunction "D_P$8") (pintype "passive"))
      (node (ref "VDD_5V_BRICK") (pin "P$1") (pinfunction "P$1_P$1") (pintype "passive"))
    )
    (net (code "239") (name "VDD_5V_HIPOWER") (class "Default")
      (node (ref "C614") (pin "P$1") (pinfunction "1_P$1") (pintype "passive"))
      (node (ref "L201") (pin "P$1") (pinfunction "P$1_P$1") (pintype "bidirectional"))
      (node (ref "U601") (pin "8") (pinfunction "OUT_8") (pintype "bidirectional"))
    )
    (net (code "240") (name "VDD_5V_IN") (class "Default")
      (node (ref "C1104") (pin "P$1") (pinfunction "1_P$1") (pintype "passive"))
      (node (ref "C702") (pin "P$1") (pinfunction "1_P$1") (pintype "passive"))
      (node (ref "F1001") (pin "1") (pinfunction "1_1") (pintype "bidirectional"))
      (node (ref "L603") (pin "P$1") (pinfunction "P$1_P$1") (pintype "bidirectional"))
      (node (ref "L701") (pin "P$1") (pinfunction "1_P$1") (pintype "passive"))
      (node (ref "LED701") (pin "A") (pinfunction "A_A") (pintype "passive"))
      (node (ref "LED704") (pin "A") (pinfunction "A_A") (pintype "passive"))
      (node (ref "R609") (pin "P$2") (pinfunction "2_P$2") (pintype "passive"))
      (node (ref "RN1101") (pin "5") (pinfunction "2_5") (pintype "passive"))
      (node (ref "RN1101") (pin "6") (pinfunction "2_6") (pintype "passive"))
      (node (ref "RN1101") (pin "7") (pinfunction "2_7") (pintype "passive"))
      (node (ref "U1101") (pin "P$12") (pinfunction "VOUT_P$12") (pintype "bidirectional"))
      (node (ref "U1102") (pin "P$5") (pinfunction "D_P$5") (pintype "passive"))
      (node (ref "U1102") (pin "P$6") (pinfunction "D_P$6") (pintype "passive"))
      (node (ref "U1103") (pin "P$5") (pinfunction "D_P$5") (pintype "passive"))
      (node (ref "U1103") (pin "P$6") (pinfunction "D_P$6") (pintype "passive"))
      (node (ref "U1104") (pin "P$5") (pinfunction "D_P$5") (pintype "passive"))
      (node (ref "U1104") (pin "P$6") (pinfunction "D_P$6") (pintype "passive"))
      (node (ref "U601") (pin "1") (pinfunction "IN_1") (pintype "bidirectional"))
      (node (ref "U602") (pin "1") (pinfunction "IN_1") (pintype "bidirectional"))
      (node (ref "U702") (pin "3") (pinfunction "VIN_3") (pintype "power_in"))
      (node (ref "U703") (pin "A1") (pinfunction "A_A1") (pintype "passive"))
      (node (ref "U703") (pin "A2") (pinfunction "A_A2") (pintype "passive"))
      (node (ref "U703") (pin "A3") (pinfunction "A_A3") (pintype "passive"))
      (node (ref "VDD_5V_IN") (pin "P$1") (pinfunction "P$1_P$1") (pintype "passive"))
    )
    (net (code "241") (name "VDD_5V_PERIPH") (class "Default")
      (node (ref "C618") (pin "P$1") (pinfunction "1_P$1") (pintype "passive"))
      (node (ref "L202") (pin "P$1") (pinfunction "P$1_P$1") (pintype "bidirectional"))
      (node (ref "L203") (pin "P$1") (pinfunction "P$1_P$1") (pintype "bidirectional"))
      (node (ref "L401") (pin "P$1") (pinfunction "P$1_P$1") (pintype "bidirectional"))
      (node (ref "L402") (pin "P$1") (pinfunction "P$1_P$1") (pintype "bidirectional"))
      (node (ref "L403") (pin "P$1") (pinfunction "P$1_P$1") (pintype "bidirectional"))
      (node (ref "L404") (pin "P$1") (pinfunction "P$1_P$1") (pintype "bidirectional"))
      (node (ref "U602") (pin "8") (pinfunction "OUT_8") (pintype "bidirectional"))
    )
    (net (code "242") (name "VDD_5V_SENS") (class "Default")
      (node (ref "R609") (pin "P$1") (pinfunction "1_P$1") (pintype "passive"))
      (node (ref "R610") (pin "P$1") (pinfunction "1_P$1") (pintype "passive"))
      (node (ref "U101") (pin "29") (pinfunction "PA4_29") (pintype "bidirectional"))
    )
    (net (code "243") (name "VDD_SERVO") (class "Default")
      (node (ref "C1102") (pin "P$1") (pinfunction "1_P$1") (pintype "passive"))
      (node (ref "D904") (pin "ANODE") (pinfunction "A_ANODE") (pintype "passive"))
      (node (ref "J901") (pin "11") (pinfunction "S_11") (pintype "passive"))
      (node (ref "J901") (pin "14") (pinfunction "S_14") (pintype "passive"))
      (node (ref "J901") (pin "17") (pinfunction "S_17") (pintype "passive"))
      (node (ref "J901") (pin "20") (pinfunction "S_20") (pintype "passive"))
      (node (ref "J901") (pin "23") (pinfunction "S_23") (pintype "passive"))
      (node (ref "J901") (pin "26") (pinfunction "S_26") (pintype "passive"))
      (node (ref "J901") (pin "29") (pinfunction "S_29") (pintype "passive"))
      (node (ref "J901") (pin "32") (pinfunction "S_32") (pintype "passive"))
      (node (ref "J901") (pin "35") (pinfunction "S_35") (pintype "passive"))
      (node (ref "J901") (pin "38") (pinfunction "S_38") (pintype "passive"))
      (node (ref "J901") (pin "41") (pinfunction "S_41") (pintype "passive"))
      (node (ref "J901") (pin "44") (pinfunction "S_44") (pintype "passive"))
      (node (ref "J901") (pin "47") (pinfunction "S_47") (pintype "passive"))
      (node (ref "J901") (pin "5") (pinfunction "S_5") (pintype "passive"))
      (node (ref "J901") (pin "8") (pinfunction "S_8") (pintype "passive"))
      (node (ref "R1109") (pin "P$1") (pinfunction "1_P$1") (pintype "passive"))
      (node (ref "R922") (pin "P$2") (pinfunction "2_P$2") (pintype "passive"))
      (node (ref "U1101") (pin "P$20") (pinfunction "V2_P$20") (pintype "bidirectional"))
      (node (ref "U1103") (pin "P$7") (pinfunction "D_P$7") (pintype "passive"))
      (node (ref "U1103") (pin "P$8") (pinfunction "D_P$8") (pintype "passive"))
      (node (ref "VDD_SERVO") (pin "P$1") (pinfunction "P$1_P$1") (pintype "passive"))
    )
    (net (code "244") (name "VDD_SERVO_IN") (class "Default")
      (node (ref "L901") (pin "P$2") (pinfunction "P$2_P$2") (pintype "bidirectional"))
      (node (ref "U1001") (pin "1") (pinfunction "IN_1") (pintype "bidirectional"))
    )
    (net (code "245") (name "VDD_SERVO_SENS") (class "Default")
      (node (ref "R918") (pin "P$1") (pinfunction "1_P$1") (pintype "passive"))
      (node (ref "R919") (pin "P$2") (pinfunction "2_P$2") (pintype "passive"))
      (node (ref "U801") (pin "14") (pinfunction "PA4_14") (pintype "bidirectional"))
    )
    (net (code "246") (name "unconnected-(J301-4-PadID)") (class "Default")
      (node (ref "J301") (pin "ID") (pinfunction "4_ID") (pintype "passive"))
    )
    (net (code "247") (name "unconnected-(JX301A-S-Pad10)") (class "Default")
      (node (ref "JX301") (pin "10") (pinfunction "S_10") (pintype "passive"))
    )
    (net (code "248") (name "unconnected-(JX301F-S-Pad8)") (class "Default")
      (node (ref "JX301") (pin "8") (pinfunction "S_8") (pintype "passive"))
    )
    (net (code "249") (name "unconnected-(JX802A-S-Pad10)") (class "Default")
      (node (ref "JX802") (pin "10") (pinfunction "S_10") (pintype "passive"))
    )
    (net (code "250") (name "unconnected-(JX802F-S-Pad8)") (class "Default")
      (node (ref "JX802") (pin "8") (pinfunction "S_8") (pintype "passive"))
    )
    (net (code "251") (name "unconnected-(U101I-PC1-Pad16)") (class "Default")
      (node (ref "U101") (pin "16") (pinfunction "PC1_16") (pintype "bidirectional"))
    )
    (net (code "252") (name "unconnected-(U202-A1-Pad1)") (class "Default")
      (node (ref "U202") (pin "1") (pinfunction "A1_1") (pintype "bidirectional"))
    )
    (net (code "253") (name "unconnected-(U202-A2-Pad3)") (class "Default")
      (node (ref "U202") (pin "3") (pinfunction "A2_3") (pintype "bidirectional"))
    )
    (net (code "254") (name "unconnected-(U202-B1-Pad20)") (class "Default")
      (node (ref "U202") (pin "20") (pinfunction "B1_20") (pintype "bidirectional"))
    )
    (net (code "255") (name "unconnected-(U202-B2-Pad18)") (class "Default")
      (node (ref "U202") (pin "18") (pinfunction "B2_18") (pintype "bidirectional"))
    )
    (net (code "256") (name "unconnected-(U501-INT1-Pad7)") (class "Default")
      (node (ref "U501") (pin "7") (pinfunction "INT1_7") (pintype "output"))
    )
    (net (code "257") (name "unconnected-(U502-DEN-Pad8)") (class "Default")
      (node (ref "U502") (pin "8") (pinfunction "DEN_8") (pintype "bidirectional"))
    )
    (net (code "258") (name "unconnected-(U502-INT1-Pad7)") (class "Default")
      (node (ref "U502") (pin "7") (pinfunction "INT1_7") (pintype "bidirectional"))
    )
    (net (code "259") (name "unconnected-(U505-AUX_CL-Pad7)") (class "Default")
      (node (ref "U505") (pin "7") (pinfunction "AUX_CL_7") (pintype "bidirectional"))
    )
    (net (code "260") (name "unconnected-(U505-AUX_DA-Pad6)") (class "Default")
      (node (ref "U505") (pin "6") (pinfunction "AUX_DA_6") (pintype "bidirectional"))
    )
    (net (code "261") (name "unconnected-(U505-CLKOUT-Pad22)") (class "Default")
      (node (ref "U505") (pin "22") (pinfunction "CLKOUT_22") (pintype "bidirectional"))
    )
    (net (code "262") (name "unconnected-(U505-FSYNC-Pad11)") (class "Default")
      (node (ref "U505") (pin "11") (pinfunction "FSYNC_11") (pintype "bidirectional"))
    )
    (net (code "263") (name "unconnected-(U505-NC1-Pad2)") (class "Default")
      (node (ref "U505") (pin "2") (pinfunction "NC1_2") (pintype "bidirectional"))
    )
    (net (code "264") (name "unconnected-(U505-NC2-Pad3)") (class "Default")
      (node (ref "U505") (pin "3") (pinfunction "NC2_3") (pintype "bidirectional"))
    )
    (net (code "265") (name "unconnected-(U505-NC3-Pad4)") (class "Default")
      (node (ref "U505") (pin "4") (pinfunction "NC3_4") (pintype "bidirectional"))
    )
    (net (code "266") (name "unconnected-(U505-NC4-Pad5)") (class "Default")
      (node (ref "U505") (pin "5") (pinfunction "NC4_5") (pintype "bidirectional"))
    )
    (net (code "267") (name "unconnected-(U505-NC5-Pad14)") (class "Default")
      (node (ref "U505") (pin "14") (pinfunction "NC5_14") (pintype "bidirectional"))
    )
    (net (code "268") (name "unconnected-(U505-NC6-Pad15)") (class "Default")
      (node (ref "U505") (pin "15") (pinfunction "NC6_15") (pintype "bidirectional"))
    )
    (net (code "269") (name "unconnected-(U505-NC7-Pad16)") (class "Default")
      (node (ref "U505") (pin "16") (pinfunction "NC7_16") (pintype "bidirectional"))
    )
    (net (code "270") (name "unconnected-(U505-NC8-Pad17)") (class "Default")
      (node (ref "U505") (pin "17") (pinfunction "NC8_17") (pintype "bidirectional"))
    )
    (net (code "271") (name "unconnected-(U505-RESV1-Pad19)") (class "Default")
      (node (ref "U505") (pin "19") (pinfunction "RESV1_19") (pintype "bidirectional"))
    )
    (net (code "272") (name "unconnected-(U505-RESV2-Pad21)") (class "Default")
      (node (ref "U505") (pin "21") (pinfunction "RESV2_21") (pintype "bidirectional"))
    )
    (net (code "273") (name "unconnected-(U506-CSB1-Pad4)") (class "Default")
      (node (ref "U506") (pin "4") (pinfunction "CSB1_4") (pintype "bidirectional"))
    )
    (net (code "274") (name "unconnected-(U801B-PA11-Pad32)") (class "Default")
      (node (ref "U801") (pin "32") (pinfunction "PA11_32") (pintype "bidirectional"))
    )
    (net (code "275") (name "unconnected-(U801D-PB12-Pad25)") (class "Default")
      (node (ref "U801") (pin "25") (pinfunction "PB12_25") (pintype "bidirectional"))
    )
    (net (code "276") (name "unconnected-(U801E-PB6-Pad42)") (class "Default")
      (node (ref "U801") (pin "42") (pinfunction "PB6_42") (pintype "bidirectional"))
    )
    (net (code "277") (name "unconnected-(U801E-PB7-Pad43)") (class "Default")
      (node (ref "U801") (pin "43") (pinfunction "PB7_43") (pintype "bidirectional"))
    )
    (net (code "278") (name "unconnected-(U801F-PC14-Pad3)") (class "Default")
      (node (ref "U801") (pin "3") (pinfunction "PC14_3") (pintype "bidirectional"))
    )
    (net (code "279") (name "unconnected-(U801F-PC15-Pad4)") (class "Default")
      (node (ref "U801") (pin "4") (pinfunction "PC15_4") (pintype "bidirectional"))
    )
    (net (code "280") (name "unconnected-(U901-A7-Pad8)") (class "Default")
      (node (ref "U901") (pin "8") (pinfunction "A7_8") (pintype "bidirectional"))
    )
    (net (code "281") (name "unconnected-(U901-A8-Pad9)") (class "Default")
      (node (ref "U901") (pin "9") (pinfunction "A8_9") (pintype "bidirectional"))
    )
    (net (code "282") (name "unconnected-(U901-B7-Pad13)") (class "Default")
      (node (ref "U901") (pin "13") (pinfunction "B7_13") (pintype "bidirectional"))
    )
    (net (code "283") (name "unconnected-(U901-B8-Pad12)") (class "Default")
      (node (ref "U901") (pin "12") (pinfunction "B8_12") (pintype "bidirectional"))
    )
    (net (code "284") (name "unconnected-(U1101-CAS-PadP$11)") (class "Default")
      (node (ref "U1101") (pin "P$11") (pinfunction "CAS_P$11") (pintype "bidirectional"))
    )
    (net (code "285") (name "unconnected-(U1101-EN-PadP$22)") (class "Default")
      (node (ref "U1101") (pin "P$22") (pinfunction "EN_P$22") (pintype "bidirectional"))
    )
    (net (code "286") (name "unconnected-(U1101-~{SHDN}-PadP$23)") (class "Default")
      (node (ref "U1101") (pin "P$23") (pinfunction "~{SHDN}_P$23") (pintype "bidirectional"))
    )
    (net (code "287") (name "~{ACCEL_MAG_CS}") (class "Default")
      (node (ref "U101") (pin "9") (pinfunction "PC15_9") (pintype "bidirectional"))
      (node (ref "U504") (pin "8") (pinfunction "CS_8") (pintype "bidirectional"))
      (node (ref "X503") (pin "6") (pinfunction "S_6") (pintype "passive"))
    )
    (net (code "288") (name "~{BARO_CS}") (class "Default")
      (node (ref "U101") (pin "88") (pinfunction "PD7_88") (pintype "bidirectional"))
      (node (ref "U506") (pin "5") (pinfunction "CSB2_5") (pintype "bidirectional"))
    )
    (net (code "289") (name "~{FMU-LED_AMBER}") (class "Default")
      (node (ref "R707") (pin "P$1") (pinfunction "1_P$1") (pintype "passive"))
      (node (ref "U101") (pin "43") (pinfunction "PE12_43") (pintype "bidirectional"))
    )
    (net (code "290") (name "~{FRAM_CS}") (class "Default")
      (node (ref "U101") (pin "57") (pinfunction "PD10_57") (pintype "bidirectional"))
      (node (ref "U102") (pin "1") (pinfunction "~{S}_1") (pintype "bidirectional"))
    )
    (net (code "291") (name "~{GYRO_CS}") (class "Default")
      (node (ref "U101") (pin "7") (pinfunction "PC13_7") (pintype "bidirectional"))
      (node (ref "U501") (pin "5") (pinfunction "CS_5") (pintype "input"))
      (node (ref "U502") (pin "5") (pinfunction "CS_5") (pintype "bidirectional"))
      (node (ref "X503") (pin "7") (pinfunction "S_7") (pintype "passive"))
    )
    (net (code "292") (name "~{IO-LED_AMBER}") (class "Default")
      (node (ref "R709") (pin "P$1") (pinfunction "1_P$1") (pintype "passive"))
      (node (ref "U801") (pin "28") (pinfunction "PB15_28") (pintype "bidirectional"))
    )
    (net (code "293") (name "~{IO-LED_BLUE}") (class "Default")
      (node (ref "R712") (pin "P$1") (pinfunction "1_P$1") (pintype "passive"))
      (node (ref "U801") (pin "27") (pinfunction "PB14_27") (pintype "bidirectional"))
    )
    (net (code "294") (name "~{IO-LED_SAFETY}") (class "Default")
      (node (ref "R710") (pin "P$2") (pinfunction "2_P$2") (pintype "passive"))
      (node (ref "U801") (pin "26") (pinfunction "PB13_26") (pintype "bidirectional"))
    )
    (net (code "295") (name "~{MPU_CS}") (class "Default")
      (node (ref "U101") (pin "17") (pinfunction "PC2_17") (pintype "bidirectional"))
      (node (ref "U505") (pin "8") (pinfunction "/CS_8") (pintype "bidirectional"))
    )
    (net (code "296") (name "~{SBUS_OUTPUT_EN}") (class "Default")
      (node (ref "U801") (pin "40") (pinfunction "PB4_40") (pintype "bidirectional"))
      (node (ref "U903") (pin "7") (pinfunction "~{2OE}_7") (pintype "input"))
    )
    (net (code "297") (name "~{SPI_EXT_NSS}") (class "Default")
      (node (ref "J403") (pin "5") (pinfunction "5_5") (pintype "passive"))
      (node (ref "U101") (pin "3") (pinfunction "PE4_3") (pintype "bidirectional"))
    )
    (net (code "298") (name "~{VBUS_VALID}") (class "Default")
      (node (ref "!VBUS_VALID") (pin "P$1") (pinfunction "P$1_P$1") (pintype "passive"))
      (node (ref "RN1101") (pin "2") (pinfunction "1_2") (pintype "passive"))
      (node (ref "U101") (pin "15") (pinfunction "PC0_15") (pintype "bidirectional"))
      (node (ref "U1101") (pin "P$9") (pinfunction "~{VALID3}_P$9") (pintype "bidirectional"))
    )
    (net (code "299") (name "~{VDD_5V_HIPOWER_OC}") (class "Default")
      (node (ref "R602") (pin "P$1") (pinfunction "1_P$1") (pintype "passive"))
      (node (ref "U101") (pin "41") (pinfunction "PE10_41") (pintype "bidirectional"))
      (node (ref "U601") (pin "4") (pinfunction "~{FAULT}_4") (pintype "bidirectional"))
    )
    (net (code "300") (name "~{VDD_5V_PERIPH_EN}") (class "Default")
      (node (ref "R615") (pin "P$1") (pinfunction "1_P$1") (pintype "passive"))
      (node (ref "U101") (pin "67") (pinfunction "PA8_67") (pintype "bidirectional"))
      (node (ref "U601") (pin "5") (pinfunction "~{CE}_5") (pintype "bidirectional"))
      (node (ref "U602") (pin "5") (pinfunction "~{CE}_5") (pintype "bidirectional"))
    )
    (net (code "301") (name "~{VDD_5V_PERIPH_OC}") (class "Default")
      (node (ref "R604") (pin "P$1") (pinfunction "1_P$1") (pintype "passive"))
      (node (ref "U101") (pin "46") (pinfunction "PE15_46") (pintype "bidirectional"))
      (node (ref "U602") (pin "4") (pinfunction "~{FAULT}_4") (pintype "bidirectional"))
    )
    (net (code "302") (name "~{VDD_BRICK_VALID}") (class "Default")
      (node (ref "!VDD_BRICK_VALID") (pin "P$1") (pinfunction "P$1_P$1") (pintype "passive"))
      (node (ref "RN1101") (pin "4") (pinfunction "1_4") (pintype "passive"))
      (node (ref "U101") (pin "91") (pinfunction "PB5_91") (pintype "bidirectional"))
      (node (ref "U1101") (pin "P$7") (pinfunction "~{VALID1}_P$7") (pintype "bidirectional"))
    )
    (net (code "303") (name "~{VDD_SERVO_VALID}") (class "Default")
      (node (ref "!VDD_SERVO_VALID") (pin "P$1") (pinfunction "P$1_P$1") (pintype "passive"))
      (node (ref "RN1101") (pin "3") (pinfunction "1_3") (pintype "passive"))
      (node (ref "U101") (pin "93") (pinfunction "PB7_93") (pintype "bidirectional"))
      (node (ref "U1101") (pin "P$8") (pinfunction "~{VALID2}_P$8") (pintype "bidirectional"))
    )
  )
)
